# clock.net
KiCad netlist of a schematic drawn in EAGLE
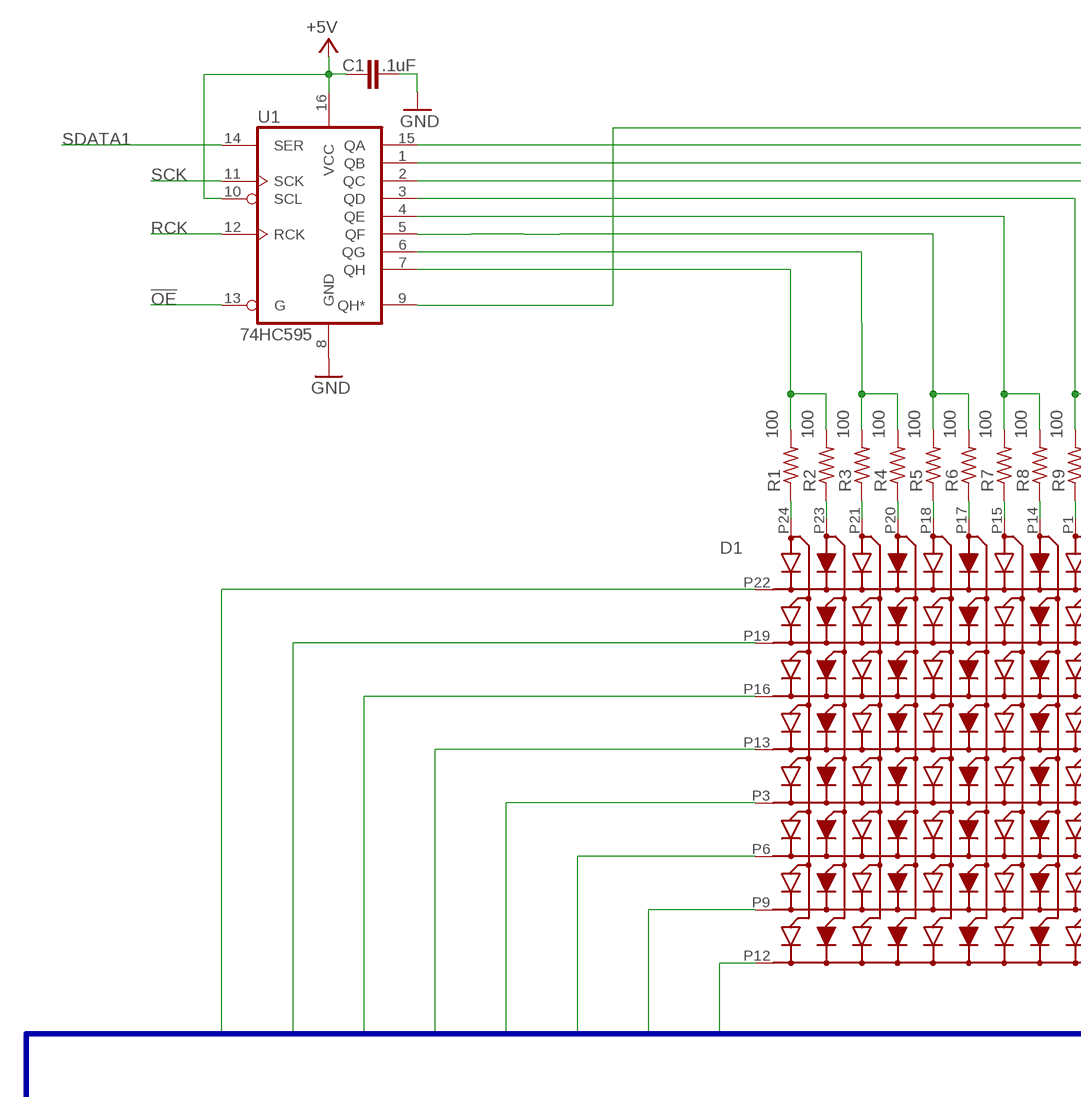
[diagram p0: schematic, sheet 1, part 1 of 3]
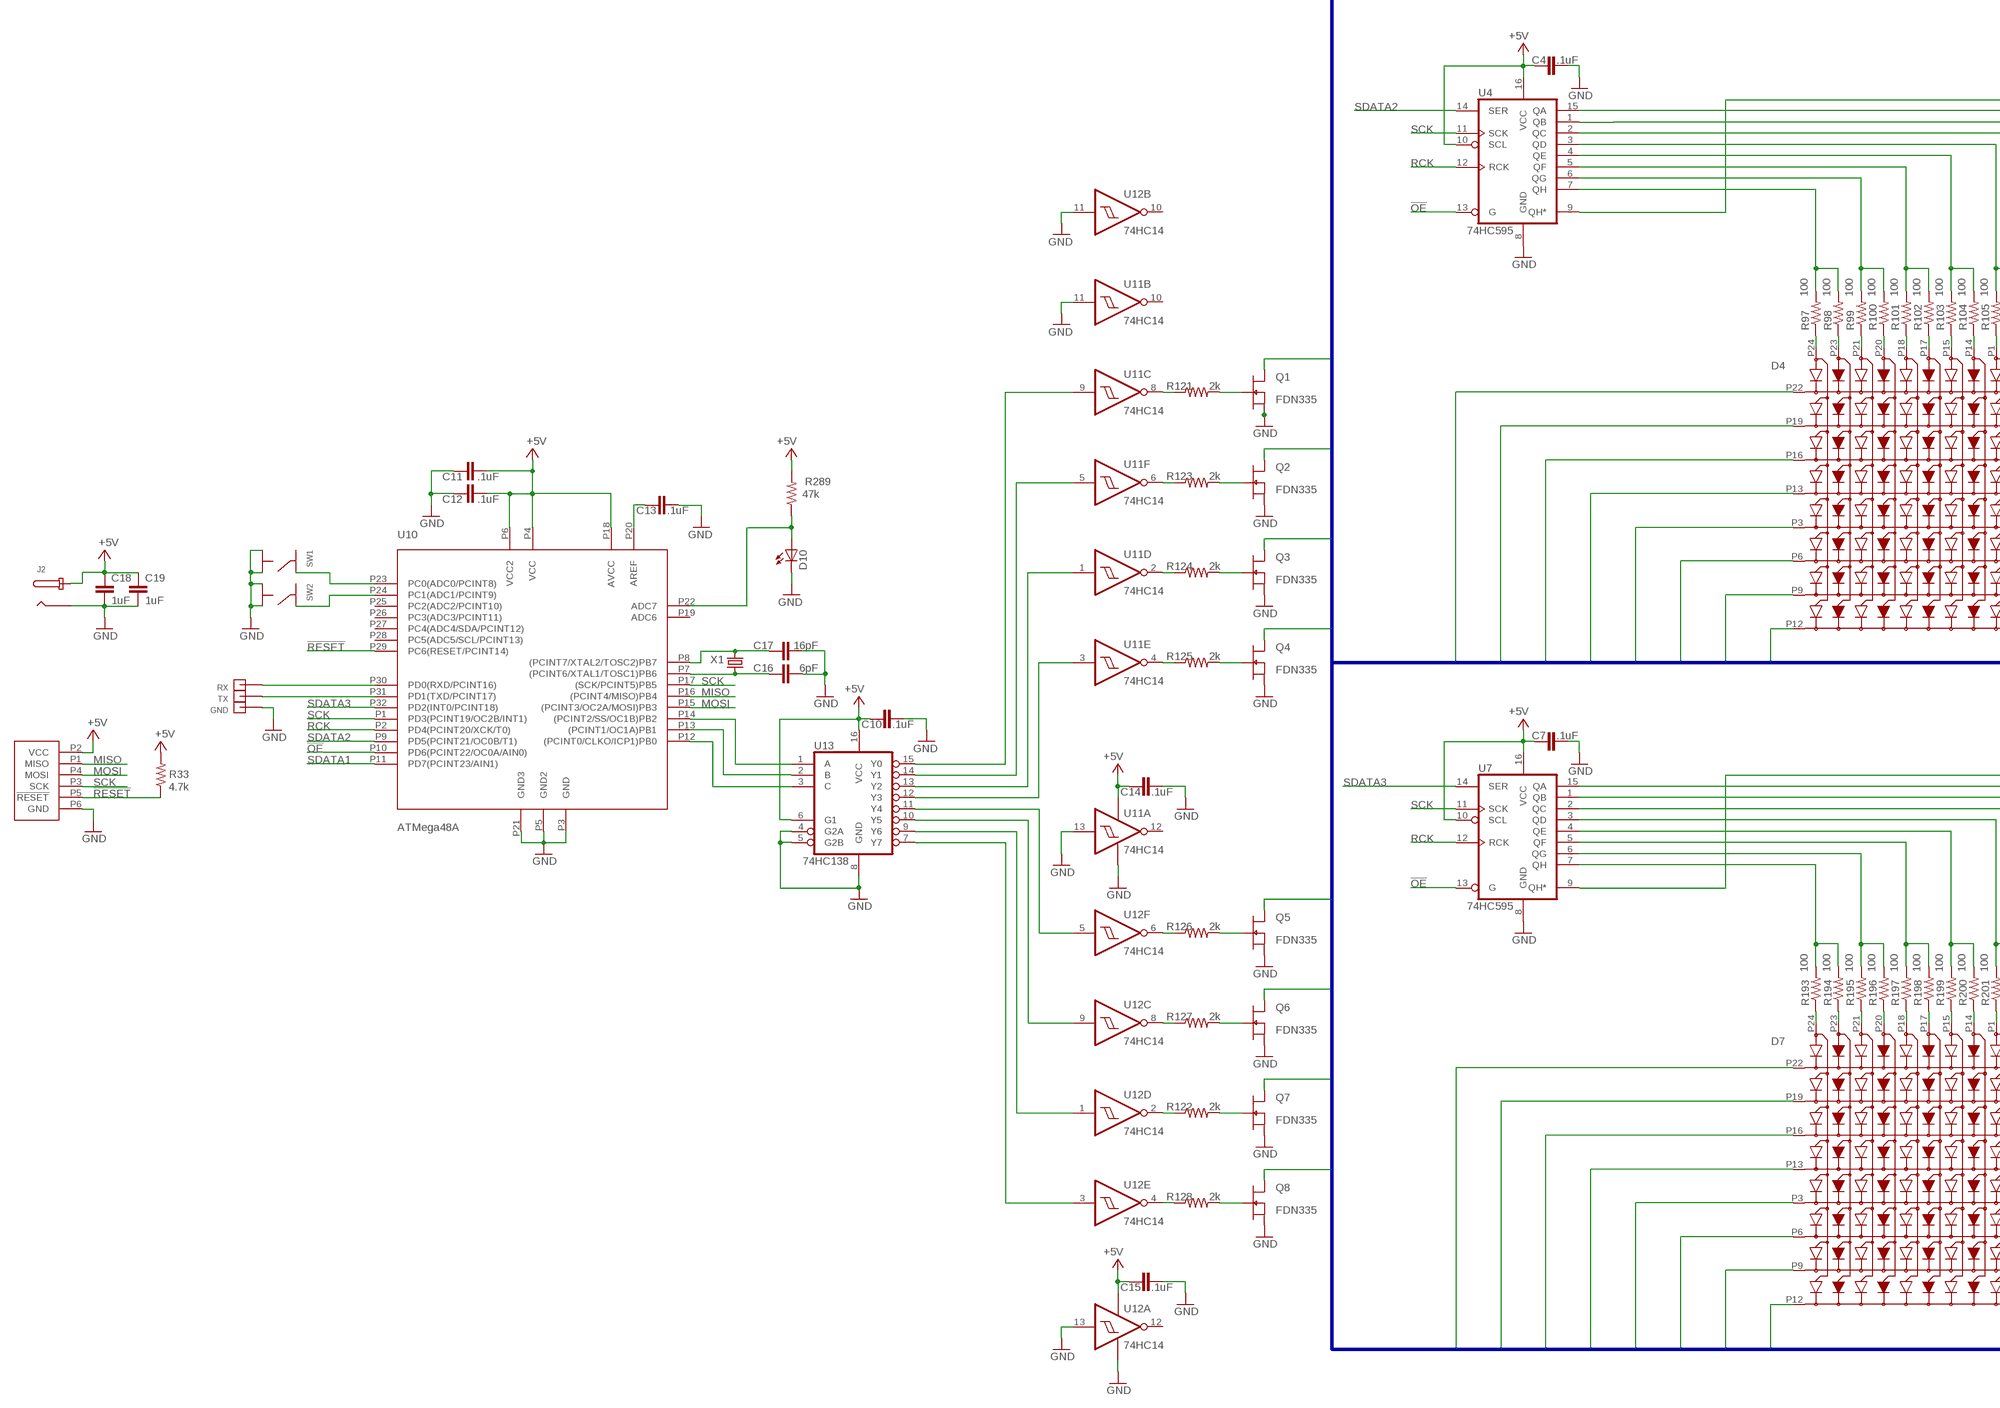
[diagram p1: schematic, sheet 1, part 2 of 3]
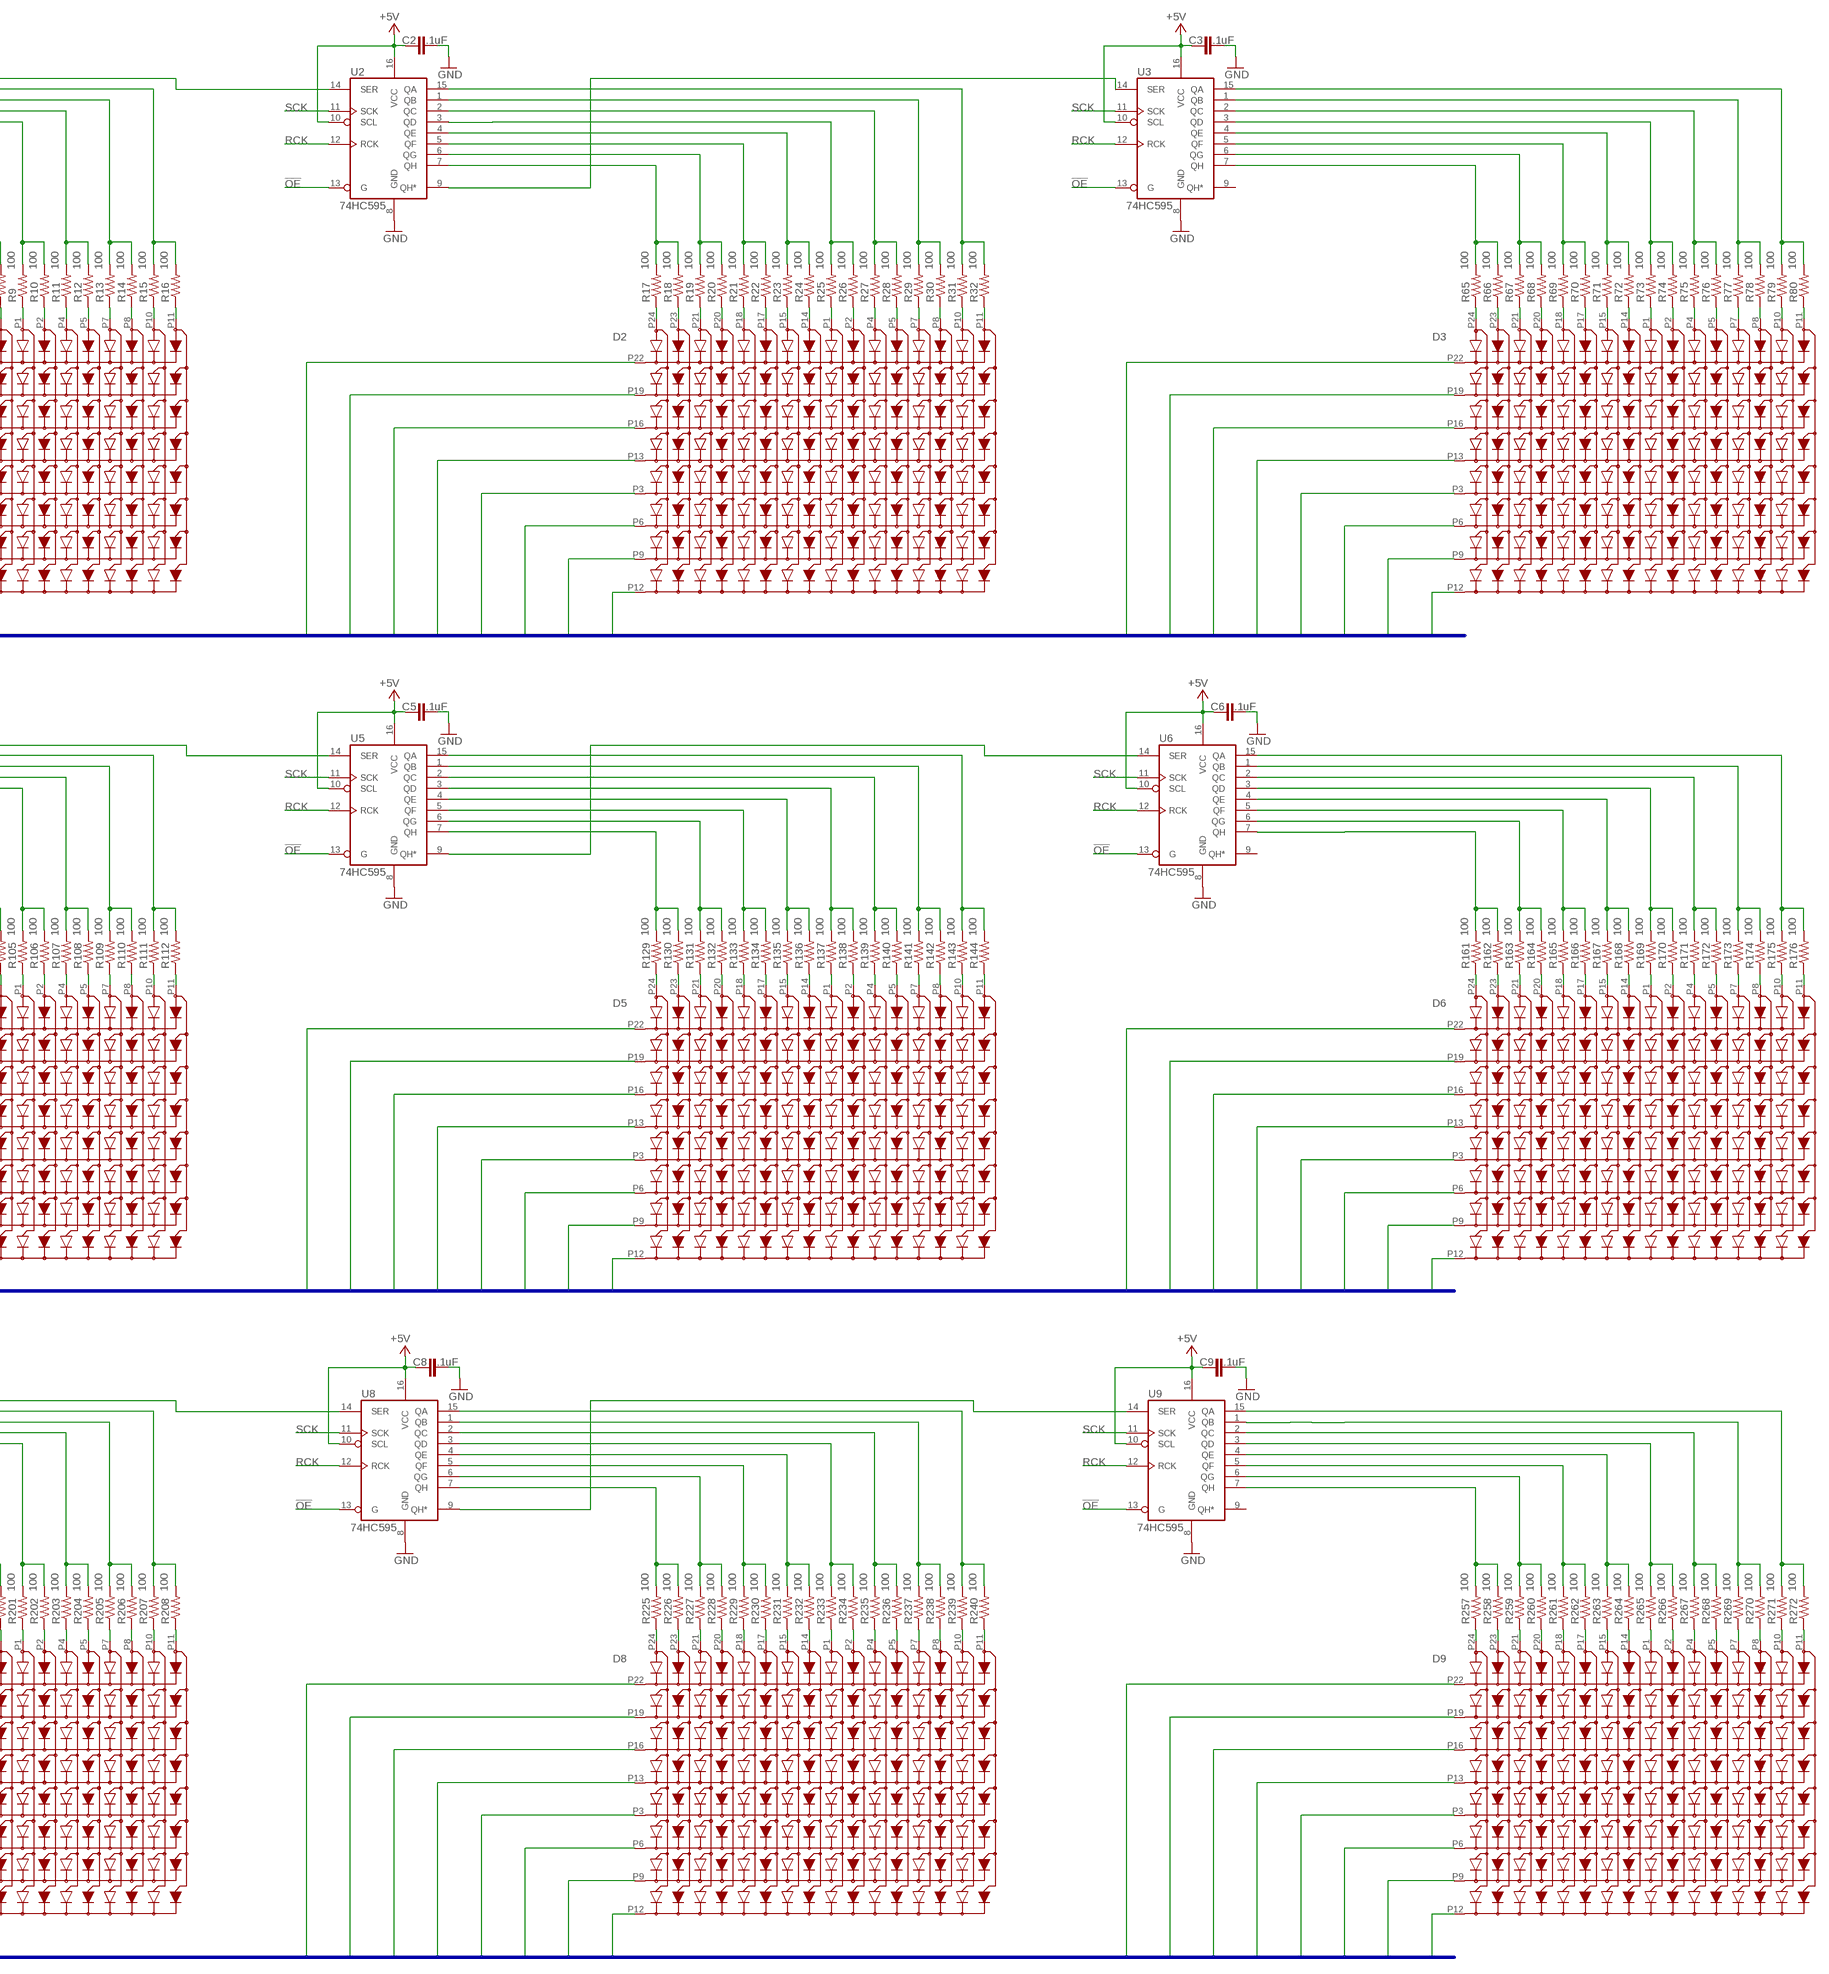
[diagram p2: schematic, sheet 1, part 3 of 3]

(export (version "E")
  (design (tool "Eeschema 10.0.6"))
  (components
    (comp (ref "C1")
      (value ".1uF")
      (footprint "eagle-import:0603_1608METRIC")
      (fields
        (field (name "DISTRIBUTORPARTNO") "478-1239-1-ND")
        (field (name "MANUFACTURER") "AVX Corporation")
        (field (name "TOLERANCE") "10%")
        (field (name "MNT-TYPE") "SM")
      )
      (libsource (lib "eagle-import") (part "CAPACITOR-.1UF"))
    )
    (comp (ref "C2")
      (value ".1uF")
      (footprint "eagle-import:0603_1608METRIC")
      (fields
        (field (name "DISTRIBUTORPARTNO") "478-1239-1-ND")
        (field (name "MANUFACTURER") "AVX Corporation")
        (field (name "TOLERANCE") "10%")
        (field (name "MNT-TYPE") "SM")
      )
      (libsource (lib "eagle-import") (part "CAPACITOR-.1UF"))
    )
    (comp (ref "C3")
      (value ".1uF")
      (footprint "eagle-import:0603_1608METRIC")
      (fields
        (field (name "DISTRIBUTORPARTNO") "478-1239-1-ND")
        (field (name "MANUFACTURER") "AVX Corporation")
        (field (name "TOLERANCE") "10%")
        (field (name "MNT-TYPE") "SM")
      )
      (libsource (lib "eagle-import") (part "CAPACITOR-.1UF"))
    )
    (comp (ref "C4")
      (value ".1uF")
      (footprint "eagle-import:0603_1608METRIC")
      (fields
        (field (name "DISTRIBUTORPARTNO") "478-1239-1-ND")
        (field (name "MANUFACTURER") "AVX Corporation")
        (field (name "TOLERANCE") "10%")
        (field (name "MNT-TYPE") "SM")
      )
      (libsource (lib "eagle-import") (part "CAPACITOR-.1UF"))
    )
    (comp (ref "C5")
      (value ".1uF")
      (footprint "eagle-import:0603_1608METRIC")
      (fields
        (field (name "DISTRIBUTORPARTNO") "478-1239-1-ND")
        (field (name "MANUFACTURER") "AVX Corporation")
        (field (name "TOLERANCE") "10%")
        (field (name "MNT-TYPE") "SM")
      )
      (libsource (lib "eagle-import") (part "CAPACITOR-.1UF"))
    )
    (comp (ref "C6")
      (value ".1uF")
      (footprint "eagle-import:0603_1608METRIC")
      (fields
        (field (name "DISTRIBUTORPARTNO") "478-1239-1-ND")
        (field (name "MANUFACTURER") "AVX Corporation")
        (field (name "TOLERANCE") "10%")
        (field (name "MNT-TYPE") "SM")
      )
      (libsource (lib "eagle-import") (part "CAPACITOR-.1UF"))
    )
    (comp (ref "C7")
      (value ".1uF")
      (footprint "eagle-import:0603_1608METRIC")
      (fields
        (field (name "DISTRIBUTORPARTNO") "478-1239-1-ND")
        (field (name "MANUFACTURER") "AVX Corporation")
        (field (name "TOLERANCE") "10%")
        (field (name "MNT-TYPE") "SM")
      )
      (libsource (lib "eagle-import") (part "CAPACITOR-.1UF"))
    )
    (comp (ref "C8")
      (value ".1uF")
      (footprint "eagle-import:0603_1608METRIC")
      (fields
        (field (name "DISTRIBUTORPARTNO") "478-1239-1-ND")
        (field (name "MANUFACTURER") "AVX Corporation")
        (field (name "TOLERANCE") "10%")
        (field (name "MNT-TYPE") "SM")
      )
      (libsource (lib "eagle-import") (part "CAPACITOR-.1UF"))
    )
    (comp (ref "C9")
      (value ".1uF")
      (footprint "eagle-import:0603_1608METRIC")
      (fields
        (field (name "DISTRIBUTORPARTNO") "478-1239-1-ND")
        (field (name "MANUFACTURER") "AVX Corporation")
        (field (name "TOLERANCE") "10%")
        (field (name "MNT-TYPE") "SM")
      )
      (libsource (lib "eagle-import") (part "CAPACITOR-.1UF"))
    )
    (comp (ref "C10")
      (value ".1uF")
      (footprint "eagle-import:0603_1608METRIC")
      (fields
        (field (name "DISTRIBUTORPARTNO") "478-1239-1-ND")
        (field (name "MANUFACTURER") "AVX Corporation")
        (field (name "TOLERANCE") "10%")
        (field (name "MNT-TYPE") "SM")
      )
      (libsource (lib "eagle-import") (part "CAPACITOR-.1UF"))
    )
    (comp (ref "C11")
      (value ".1uF")
      (footprint "eagle-import:0603_1608METRIC")
      (fields
        (field (name "DISTRIBUTORPARTNO") "478-1239-1-ND")
        (field (name "MANUFACTURER") "AVX Corporation")
        (field (name "TOLERANCE") "10%")
        (field (name "MNT-TYPE") "SM")
      )
      (libsource (lib "eagle-import") (part "CAPACITOR-.1UF"))
    )
    (comp (ref "C12")
      (value ".1uF")
      (footprint "eagle-import:0603_1608METRIC")
      (fields
        (field (name "DISTRIBUTORPARTNO") "478-1239-1-ND")
        (field (name "MANUFACTURER") "AVX Corporation")
        (field (name "TOLERANCE") "10%")
        (field (name "MNT-TYPE") "SM")
      )
      (libsource (lib "eagle-import") (part "CAPACITOR-.1UF"))
    )
    (comp (ref "C13")
      (value ".1uF")
      (footprint "eagle-import:0603_1608METRIC")
      (fields
        (field (name "DISTRIBUTORPARTNO") "478-1239-1-ND")
        (field (name "MANUFACTURER") "AVX Corporation")
        (field (name "TOLERANCE") "10%")
        (field (name "MNT-TYPE") "SM")
      )
      (libsource (lib "eagle-import") (part "CAPACITOR-.1UF"))
    )
    (comp (ref "C14")
      (value ".1uF")
      (footprint "eagle-import:0603_1608METRIC")
      (fields
        (field (name "DISTRIBUTORPARTNO") "478-1239-1-ND")
        (field (name "MANUFACTURER") "AVX Corporation")
        (field (name "TOLERANCE") "10%")
        (field (name "MNT-TYPE") "SM")
      )
      (libsource (lib "eagle-import") (part "CAPACITOR-.1UF"))
    )
    (comp (ref "C15")
      (value ".1uF")
      (footprint "eagle-import:0603_1608METRIC")
      (fields
        (field (name "DISTRIBUTORPARTNO") "478-1239-1-ND")
        (field (name "MANUFACTURER") "AVX Corporation")
        (field (name "TOLERANCE") "10%")
        (field (name "MNT-TYPE") "SM")
      )
      (libsource (lib "eagle-import") (part "CAPACITOR-.1UF"))
    )
    (comp (ref "C16")
      (value "6pF")
      (footprint "eagle-import:0603_1608METRIC")
      (fields
        (field (name "DISTRIBUTORPARTNO") "445-5036-1-ND")
        (field (name "MANUFACTURER") "TDK Corporation")
        (field (name "TOLERANCE") "5%")
      )
      (libsource (lib "eagle-import") (part "CAPACITOR-6PF"))
    )
    (comp (ref "C17")
      (value "16pF")
      (footprint "eagle-import:0603_1608METRIC")
      (fields
        (field (name "DISTRIBUTORPARTNO") "445-5051-1-ND")
        (field (name "MANUFACTURER") "TDK Corporation")
        (field (name "TOLERANCE") "5%")
      )
      (libsource (lib "eagle-import") (part "CAPACITOR-16PF"))
    )
    (comp (ref "C18")
      (value "1uF")
      (footprint "eagle-import:0603_1608METRIC")
      (fields
        (field (name "DISTRIBUTORPARTNO") "445-1328-1-ND")
        (field (name "MANUFACTURER") "TDK CORPORATION")
        (field (name "TOLERANCE") "20%")
      )
      (libsource (lib "eagle-import") (part "CAPACITOR-1UF"))
    )
    (comp (ref "C19")
      (value "1uF")
      (footprint "eagle-import:0603_1608METRIC")
      (fields
        (field (name "DISTRIBUTORPARTNO") "445-1328-1-ND")
        (field (name "MANUFACTURER") "TDK CORPORATION")
        (field (name "TOLERANCE") "20%")
      )
      (libsource (lib "eagle-import") (part "CAPACITOR-1UF"))
    )
    (comp (ref "D1")
      (value "BL-M12A883DUG-11\"")
      (footprint "eagle-import:BL-M12A883DUG-11")
      (fields
        (field (name "DISTRIBUTORPARTNO") "458")
        (field (name "MANPARTNO") "BL-M12A883DUG-11")
        (field (name "MANUFACTURER") "BETLUX")
      )
      (libsource (lib "eagle-import") (part "BL-M12A883DUG-11{dblquote}"))
    )
    (comp (ref "D2")
      (value "BL-M12A883DUG-11\"")
      (footprint "eagle-import:BL-M12A883DUG-11")
      (fields
        (field (name "DISTRIBUTORPARTNO") "458")
        (field (name "MANPARTNO") "BL-M12A883DUG-11")
        (field (name "MANUFACTURER") "BETLUX")
      )
      (libsource (lib "eagle-import") (part "BL-M12A883DUG-11{dblquote}"))
    )
    (comp (ref "D3")
      (value "BL-M12A883DUG-11\"")
      (footprint "eagle-import:BL-M12A883DUG-11")
      (fields
        (field (name "DISTRIBUTORPARTNO") "458")
        (field (name "MANPARTNO") "BL-M12A883DUG-11")
        (field (name "MANUFACTURER") "BETLUX")
      )
      (libsource (lib "eagle-import") (part "BL-M12A883DUG-11{dblquote}"))
    )
    (comp (ref "D4")
      (value "BL-M12A883DUG-11\"")
      (footprint "eagle-import:BL-M12A883DUG-11")
      (fields
        (field (name "DISTRIBUTORPARTNO") "458")
        (field (name "MANPARTNO") "BL-M12A883DUG-11")
        (field (name "MANUFACTURER") "BETLUX")
      )
      (libsource (lib "eagle-import") (part "BL-M12A883DUG-11{dblquote}"))
    )
    (comp (ref "D5")
      (value "BL-M12A883DUG-11\"")
      (footprint "eagle-import:BL-M12A883DUG-11")
      (fields
        (field (name "DISTRIBUTORPARTNO") "458")
        (field (name "MANPARTNO") "BL-M12A883DUG-11")
        (field (name "MANUFACTURER") "BETLUX")
      )
      (libsource (lib "eagle-import") (part "BL-M12A883DUG-11{dblquote}"))
    )
    (comp (ref "D6")
      (value "BL-M12A883DUG-11\"")
      (footprint "eagle-import:BL-M12A883DUG-11")
      (fields
        (field (name "DISTRIBUTORPARTNO") "458")
        (field (name "MANPARTNO") "BL-M12A883DUG-11")
        (field (name "MANUFACTURER") "BETLUX")
      )
      (libsource (lib "eagle-import") (part "BL-M12A883DUG-11{dblquote}"))
    )
    (comp (ref "D7")
      (value "BL-M12A883DUG-11\"")
      (footprint "eagle-import:BL-M12A883DUG-11")
      (fields
        (field (name "DISTRIBUTORPARTNO") "458")
        (field (name "MANPARTNO") "BL-M12A883DUG-11")
        (field (name "MANUFACTURER") "BETLUX")
      )
      (libsource (lib "eagle-import") (part "BL-M12A883DUG-11{dblquote}"))
    )
    (comp (ref "D8")
      (value "BL-M12A883DUG-11\"")
      (footprint "eagle-import:BL-M12A883DUG-11")
      (fields
        (field (name "DISTRIBUTORPARTNO") "458")
        (field (name "MANPARTNO") "BL-M12A883DUG-11")
        (field (name "MANUFACTURER") "BETLUX")
      )
      (libsource (lib "eagle-import") (part "BL-M12A883DUG-11{dblquote}"))
    )
    (comp (ref "D9")
      (value "BL-M12A883DUG-11\"")
      (footprint "eagle-import:BL-M12A883DUG-11")
      (fields
        (field (name "DISTRIBUTORPARTNO") "458")
        (field (name "MANPARTNO") "BL-M12A883DUG-11")
        (field (name "MANUFACTURER") "BETLUX")
      )
      (libsource (lib "eagle-import") (part "BL-M12A883DUG-11{dblquote}"))
    )
    (comp (ref "D10")
      (value "TEPT4400")
      (footprint "eagle-import:LED3MM")
      (fields
        (field (name "DISTRIBUTORPARTNO") "751-1057-ND")
        (field (name "MANUFACTURER") "Vishay Semiconductors")
      )
      (libsource (lib "eagle-import") (part "TEPT4400"))
    )
    (comp (ref "GND")
      (value "HEADERPIN")
      (footprint "eagle-import:HEADERPIN")
      (libsource (lib "eagle-import") (part "HEADERPIN"))
    )
    (comp (ref "J1")
      (value "PROGHEADER-PINS")
      (footprint "eagle-import:ATMEL-PROGRAMMING-HEADER")
      (fields
        (field (name "DISTRIBUTORPARTNO") "xxSAM1048-50-NDxx")
        (field (name "MANPARTNO") "TSW-150-08-T-D")
        (field (name "MANUFACTURER") "Samtec Inc.")
      )
      (libsource (lib "eagle-import") (part "PROGHEADER-PINS"))
    )
    (comp (ref "J2")
      (value "DC-BARREL-JACK")
      (footprint "eagle-import:PJ-037A")
      (fields
        (field (name "DISTRIBUTORPARTNO") "CP-037A-ND")
        (field (name "MANPARTNO") "PJ-037A")
        (field (name "MANUFACTURER") "CUI Inc")
      )
      (libsource (lib "eagle-import") (part "DC-BARREL-JACK"))
    )
    (comp (ref "Q1")
      (value "FDN335")
      (footprint "eagle-import:SOT23")
      (fields
        (field (name "DISTRIBUTORPARTNO") "FDN335NCT-ND")
        (field (name "MANPARTNO") "FDN335N")
        (field (name "MANUFACTURER") "Fairchild Semiconductor")
      )
      (libsource (lib "eagle-import") (part "FDN335"))
    )
    (comp (ref "Q2")
      (value "FDN335")
      (footprint "eagle-import:SOT23")
      (fields
        (field (name "DISTRIBUTORPARTNO") "FDN335NCT-ND")
        (field (name "MANPARTNO") "FDN335N")
        (field (name "MANUFACTURER") "Fairchild Semiconductor")
      )
      (libsource (lib "eagle-import") (part "FDN335"))
    )
    (comp (ref "Q3")
      (value "FDN335")
      (footprint "eagle-import:SOT23")
      (fields
        (field (name "DISTRIBUTORPARTNO") "FDN335NCT-ND")
        (field (name "MANPARTNO") "FDN335N")
        (field (name "MANUFACTURER") "Fairchild Semiconductor")
      )
      (libsource (lib "eagle-import") (part "FDN335"))
    )
    (comp (ref "Q4")
      (value "FDN335")
      (footprint "eagle-import:SOT23")
      (fields
        (field (name "DISTRIBUTORPARTNO") "FDN335NCT-ND")
        (field (name "MANPARTNO") "FDN335N")
        (field (name "MANUFACTURER") "Fairchild Semiconductor")
      )
      (libsource (lib "eagle-import") (part "FDN335"))
    )
    (comp (ref "Q5")
      (value "FDN335")
      (footprint "eagle-import:SOT23")
      (fields
        (field (name "DISTRIBUTORPARTNO") "FDN335NCT-ND")
        (field (name "MANPARTNO") "FDN335N")
        (field (name "MANUFACTURER") "Fairchild Semiconductor")
      )
      (libsource (lib "eagle-import") (part "FDN335"))
    )
    (comp (ref "Q6")
      (value "FDN335")
      (footprint "eagle-import:SOT23")
      (fields
        (field (name "DISTRIBUTORPARTNO") "FDN335NCT-ND")
        (field (name "MANPARTNO") "FDN335N")
        (field (name "MANUFACTURER") "Fairchild Semiconductor")
      )
      (libsource (lib "eagle-import") (part "FDN335"))
    )
    (comp (ref "Q7")
      (value "FDN335")
      (footprint "eagle-import:SOT23")
      (fields
        (field (name "DISTRIBUTORPARTNO") "FDN335NCT-ND")
        (field (name "MANPARTNO") "FDN335N")
        (field (name "MANUFACTURER") "Fairchild Semiconductor")
      )
      (libsource (lib "eagle-import") (part "FDN335"))
    )
    (comp (ref "Q8")
      (value "FDN335")
      (footprint "eagle-import:SOT23")
      (fields
        (field (name "DISTRIBUTORPARTNO") "FDN335NCT-ND")
        (field (name "MANPARTNO") "FDN335N")
        (field (name "MANUFACTURER") "Fairchild Semiconductor")
      )
      (libsource (lib "eagle-import") (part "FDN335"))
    )
    (comp (ref "R1")
      (value "100")
      (footprint "eagle-import:0603_1608METRIC")
      (fields
        (field (name "DISTRIBUTORPARTNO") "311-100GRCT-ND")
        (field (name "MANPARTNO") "RC0603JR-07100RL")
        (field (name "MANUFACTURER") "Yaego")
        (field (name "PACKAGE") "0603 (1608 Metric)")
      )
      (libsource (lib "eagle-import") (part "RESISTOR--5%-0603100"))
    )
    (comp (ref "R2")
      (value "100")
      (footprint "eagle-import:0603_1608METRIC")
      (fields
        (field (name "DISTRIBUTORPARTNO") "311-100GRCT-ND")
        (field (name "MANPARTNO") "RC0603JR-07100RL")
        (field (name "MANUFACTURER") "Yaego")
        (field (name "PACKAGE") "0603 (1608 Metric)")
      )
      (libsource (lib "eagle-import") (part "RESISTOR--5%-0603100"))
    )
    (comp (ref "R3")
      (value "100")
      (footprint "eagle-import:0603_1608METRIC")
      (fields
        (field (name "DISTRIBUTORPARTNO") "311-100GRCT-ND")
        (field (name "MANPARTNO") "RC0603JR-07100RL")
        (field (name "MANUFACTURER") "Yaego")
        (field (name "PACKAGE") "0603 (1608 Metric)")
      )
      (libsource (lib "eagle-import") (part "RESISTOR--5%-0603100"))
    )
    (comp (ref "R4")
      (value "100")
      (footprint "eagle-import:0603_1608METRIC")
      (fields
        (field (name "DISTRIBUTORPARTNO") "311-100GRCT-ND")
        (field (name "MANPARTNO") "RC0603JR-07100RL")
        (field (name "MANUFACTURER") "Yaego")
        (field (name "PACKAGE") "0603 (1608 Metric)")
      )
      (libsource (lib "eagle-import") (part "RESISTOR--5%-0603100"))
    )
    (comp (ref "R5")
      (value "100")
      (footprint "eagle-import:0603_1608METRIC")
      (fields
        (field (name "DISTRIBUTORPARTNO") "311-100GRCT-ND")
        (field (name "MANPARTNO") "RC0603JR-07100RL")
        (field (name "MANUFACTURER") "Yaego")
        (field (name "PACKAGE") "0603 (1608 Metric)")
      )
      (libsource (lib "eagle-import") (part "RESISTOR--5%-0603100"))
    )
    (comp (ref "R6")
      (value "100")
      (footprint "eagle-import:0603_1608METRIC")
      (fields
        (field (name "DISTRIBUTORPARTNO") "311-100GRCT-ND")
        (field (name "MANPARTNO") "RC0603JR-07100RL")
        (field (name "MANUFACTURER") "Yaego")
        (field (name "PACKAGE") "0603 (1608 Metric)")
      )
      (libsource (lib "eagle-import") (part "RESISTOR--5%-0603100"))
    )
    (comp (ref "R7")
      (value "100")
      (footprint "eagle-import:0603_1608METRIC")
      (fields
        (field (name "DISTRIBUTORPARTNO") "311-100GRCT-ND")
        (field (name "MANPARTNO") "RC0603JR-07100RL")
        (field (name "MANUFACTURER") "Yaego")
        (field (name "PACKAGE") "0603 (1608 Metric)")
      )
      (libsource (lib "eagle-import") (part "RESISTOR--5%-0603100"))
    )
    (comp (ref "R8")
      (value "100")
      (footprint "eagle-import:0603_1608METRIC")
      (fields
        (field (name "DISTRIBUTORPARTNO") "311-100GRCT-ND")
        (field (name "MANPARTNO") "RC0603JR-07100RL")
        (field (name "MANUFACTURER") "Yaego")
        (field (name "PACKAGE") "0603 (1608 Metric)")
      )
      (libsource (lib "eagle-import") (part "RESISTOR--5%-0603100"))
    )
    (comp (ref "R9")
      (value "100")
      (footprint "eagle-import:0603_1608METRIC")
      (fields
        (field (name "DISTRIBUTORPARTNO") "311-100GRCT-ND")
        (field (name "MANPARTNO") "RC0603JR-07100RL")
        (field (name "MANUFACTURER") "Yaego")
        (field (name "PACKAGE") "0603 (1608 Metric)")
      )
      (libsource (lib "eagle-import") (part "RESISTOR--5%-0603100"))
    )
    (comp (ref "R10")
      (value "100")
      (footprint "eagle-import:0603_1608METRIC")
      (fields
        (field (name "DISTRIBUTORPARTNO") "311-100GRCT-ND")
        (field (name "MANPARTNO") "RC0603JR-07100RL")
        (field (name "MANUFACTURER") "Yaego")
        (field (name "PACKAGE") "0603 (1608 Metric)")
      )
      (libsource (lib "eagle-import") (part "RESISTOR--5%-0603100"))
    )
    (comp (ref "R11")
      (value "100")
      (footprint "eagle-import:0603_1608METRIC")
      (fields
        (field (name "DISTRIBUTORPARTNO") "311-100GRCT-ND")
        (field (name "MANPARTNO") "RC0603JR-07100RL")
        (field (name "MANUFACTURER") "Yaego")
        (field (name "PACKAGE") "0603 (1608 Metric)")
      )
      (libsource (lib "eagle-import") (part "RESISTOR--5%-0603100"))
    )
    (comp (ref "R12")
      (value "100")
      (footprint "eagle-import:0603_1608METRIC")
      (fields
        (field (name "DISTRIBUTORPARTNO") "311-100GRCT-ND")
        (field (name "MANPARTNO") "RC0603JR-07100RL")
        (field (name "MANUFACTURER") "Yaego")
        (field (name "PACKAGE") "0603 (1608 Metric)")
      )
      (libsource (lib "eagle-import") (part "RESISTOR--5%-0603100"))
    )
    (comp (ref "R13")
      (value "100")
      (footprint "eagle-import:0603_1608METRIC")
      (fields
        (field (name "DISTRIBUTORPARTNO") "311-100GRCT-ND")
        (field (name "MANPARTNO") "RC0603JR-07100RL")
        (field (name "MANUFACTURER") "Yaego")
        (field (name "PACKAGE") "0603 (1608 Metric)")
      )
      (libsource (lib "eagle-import") (part "RESISTOR--5%-0603100"))
    )
    (comp (ref "R14")
      (value "100")
      (footprint "eagle-import:0603_1608METRIC")
      (fields
        (field (name "DISTRIBUTORPARTNO") "311-100GRCT-ND")
        (field (name "MANPARTNO") "RC0603JR-07100RL")
        (field (name "MANUFACTURER") "Yaego")
        (field (name "PACKAGE") "0603 (1608 Metric)")
      )
      (libsource (lib "eagle-import") (part "RESISTOR--5%-0603100"))
    )
    (comp (ref "R15")
      (value "100")
      (footprint "eagle-import:0603_1608METRIC")
      (fields
        (field (name "DISTRIBUTORPARTNO") "311-100GRCT-ND")
        (field (name "MANPARTNO") "RC0603JR-07100RL")
        (field (name "MANUFACTURER") "Yaego")
        (field (name "PACKAGE") "0603 (1608 Metric)")
      )
      (libsource (lib "eagle-import") (part "RESISTOR--5%-0603100"))
    )
    (comp (ref "R16")
      (value "100")
      (footprint "eagle-import:0603_1608METRIC")
      (fields
        (field (name "DISTRIBUTORPARTNO") "311-100GRCT-ND")
        (field (name "MANPARTNO") "RC0603JR-07100RL")
        (field (name "MANUFACTURER") "Yaego")
        (field (name "PACKAGE") "0603 (1608 Metric)")
      )
      (libsource (lib "eagle-import") (part "RESISTOR--5%-0603100"))
    )
    (comp (ref "R17")
      (value "100")
      (footprint "eagle-import:0603_1608METRIC")
      (fields
        (field (name "DISTRIBUTORPARTNO") "311-100GRCT-ND")
        (field (name "MANPARTNO") "RC0603JR-07100RL")
        (field (name "MANUFACTURER") "Yaego")
        (field (name "PACKAGE") "0603 (1608 Metric)")
      )
      (libsource (lib "eagle-import") (part "RESISTOR--5%-0603100"))
    )
    (comp (ref "R18")
      (value "100")
      (footprint "eagle-import:0603_1608METRIC")
      (fields
        (field (name "DISTRIBUTORPARTNO") "311-100GRCT-ND")
        (field (name "MANPARTNO") "RC0603JR-07100RL")
        (field (name "MANUFACTURER") "Yaego")
        (field (name "PACKAGE") "0603 (1608 Metric)")
      )
      (libsource (lib "eagle-import") (part "RESISTOR--5%-0603100"))
    )
    (comp (ref "R19")
      (value "100")
      (footprint "eagle-import:0603_1608METRIC")
      (fields
        (field (name "DISTRIBUTORPARTNO") "311-100GRCT-ND")
        (field (name "MANPARTNO") "RC0603JR-07100RL")
        (field (name "MANUFACTURER") "Yaego")
        (field (name "PACKAGE") "0603 (1608 Metric)")
      )
      (libsource (lib "eagle-import") (part "RESISTOR--5%-0603100"))
    )
    (comp (ref "R20")
      (value "100")
      (footprint "eagle-import:0603_1608METRIC")
      (fields
        (field (name "DISTRIBUTORPARTNO") "311-100GRCT-ND")
        (field (name "MANPARTNO") "RC0603JR-07100RL")
        (field (name "MANUFACTURER") "Yaego")
        (field (name "PACKAGE") "0603 (1608 Metric)")
      )
      (libsource (lib "eagle-import") (part "RESISTOR--5%-0603100"))
    )
    (comp (ref "R21")
      (value "100")
      (footprint "eagle-import:0603_1608METRIC")
      (fields
        (field (name "DISTRIBUTORPARTNO") "311-100GRCT-ND")
        (field (name "MANPARTNO") "RC0603JR-07100RL")
        (field (name "MANUFACTURER") "Yaego")
        (field (name "PACKAGE") "0603 (1608 Metric)")
      )
      (libsource (lib "eagle-import") (part "RESISTOR--5%-0603100"))
    )
    (comp (ref "R22")
      (value "100")
      (footprint "eagle-import:0603_1608METRIC")
      (fields
        (field (name "DISTRIBUTORPARTNO") "311-100GRCT-ND")
        (field (name "MANPARTNO") "RC0603JR-07100RL")
        (field (name "MANUFACTURER") "Yaego")
        (field (name "PACKAGE") "0603 (1608 Metric)")
      )
      (libsource (lib "eagle-import") (part "RESISTOR--5%-0603100"))
    )
    (comp (ref "R23")
      (value "100")
      (footprint "eagle-import:0603_1608METRIC")
      (fields
        (field (name "DISTRIBUTORPARTNO") "311-100GRCT-ND")
        (field (name "MANPARTNO") "RC0603JR-07100RL")
        (field (name "MANUFACTURER") "Yaego")
        (field (name "PACKAGE") "0603 (1608 Metric)")
      )
      (libsource (lib "eagle-import") (part "RESISTOR--5%-0603100"))
    )
    (comp (ref "R24")
      (value "100")
      (footprint "eagle-import:0603_1608METRIC")
      (fields
        (field (name "DISTRIBUTORPARTNO") "311-100GRCT-ND")
        (field (name "MANPARTNO") "RC0603JR-07100RL")
        (field (name "MANUFACTURER") "Yaego")
        (field (name "PACKAGE") "0603 (1608 Metric)")
      )
      (libsource (lib "eagle-import") (part "RESISTOR--5%-0603100"))
    )
    (comp (ref "R25")
      (value "100")
      (footprint "eagle-import:0603_1608METRIC")
      (fields
        (field (name "DISTRIBUTORPARTNO") "311-100GRCT-ND")
        (field (name "MANPARTNO") "RC0603JR-07100RL")
        (field (name "MANUFACTURER") "Yaego")
        (field (name "PACKAGE") "0603 (1608 Metric)")
      )
      (libsource (lib "eagle-import") (part "RESISTOR--5%-0603100"))
    )
    (comp (ref "R26")
      (value "100")
      (footprint "eagle-import:0603_1608METRIC")
      (fields
        (field (name "DISTRIBUTORPARTNO") "311-100GRCT-ND")
        (field (name "MANPARTNO") "RC0603JR-07100RL")
        (field (name "MANUFACTURER") "Yaego")
        (field (name "PACKAGE") "0603 (1608 Metric)")
      )
      (libsource (lib "eagle-import") (part "RESISTOR--5%-0603100"))
    )
    (comp (ref "R27")
      (value "100")
      (footprint "eagle-import:0603_1608METRIC")
      (fields
        (field (name "DISTRIBUTORPARTNO") "311-100GRCT-ND")
        (field (name "MANPARTNO") "RC0603JR-07100RL")
        (field (name "MANUFACTURER") "Yaego")
        (field (name "PACKAGE") "0603 (1608 Metric)")
      )
      (libsource (lib "eagle-import") (part "RESISTOR--5%-0603100"))
    )
    (comp (ref "R28")
      (value "100")
      (footprint "eagle-import:0603_1608METRIC")
      (fields
        (field (name "DISTRIBUTORPARTNO") "311-100GRCT-ND")
        (field (name "MANPARTNO") "RC0603JR-07100RL")
        (field (name "MANUFACTURER") "Yaego")
        (field (name "PACKAGE") "0603 (1608 Metric)")
      )
      (libsource (lib "eagle-import") (part "RESISTOR--5%-0603100"))
    )
    (comp (ref "R29")
      (value "100")
      (footprint "eagle-import:0603_1608METRIC")
      (fields
        (field (name "DISTRIBUTORPARTNO") "311-100GRCT-ND")
        (field (name "MANPARTNO") "RC0603JR-07100RL")
        (field (name "MANUFACTURER") "Yaego")
        (field (name "PACKAGE") "0603 (1608 Metric)")
      )
      (libsource (lib "eagle-import") (part "RESISTOR--5%-0603100"))
    )
    (comp (ref "R30")
      (value "100")
      (footprint "eagle-import:0603_1608METRIC")
      (fields
        (field (name "DISTRIBUTORPARTNO") "311-100GRCT-ND")
        (field (name "MANPARTNO") "RC0603JR-07100RL")
        (field (name "MANUFACTURER") "Yaego")
        (field (name "PACKAGE") "0603 (1608 Metric)")
      )
      (libsource (lib "eagle-import") (part "RESISTOR--5%-0603100"))
    )
    (comp (ref "R31")
      (value "100")
      (footprint "eagle-import:0603_1608METRIC")
      (fields
        (field (name "DISTRIBUTORPARTNO") "311-100GRCT-ND")
        (field (name "MANPARTNO") "RC0603JR-07100RL")
        (field (name "MANUFACTURER") "Yaego")
        (field (name "PACKAGE") "0603 (1608 Metric)")
      )
      (libsource (lib "eagle-import") (part "RESISTOR--5%-0603100"))
    )
    (comp (ref "R32")
      (value "100")
      (footprint "eagle-import:0603_1608METRIC")
      (fields
        (field (name "DISTRIBUTORPARTNO") "311-100GRCT-ND")
        (field (name "MANPARTNO") "RC0603JR-07100RL")
        (field (name "MANUFACTURER") "Yaego")
        (field (name "PACKAGE") "0603 (1608 Metric)")
      )
      (libsource (lib "eagle-import") (part "RESISTOR--5%-0603100"))
    )
    (comp (ref "R33")
      (value "4.7k")
      (footprint "eagle-import:0603_1608METRIC")
      (fields
        (field (name "DISTRIBUTORPARTNO") "311-4.7kGRCT-ND")
        (field (name "MANPARTNO") "RC0603JR-074K7L")
        (field (name "MANUFACTURER") "Yaego")
      )
      (libsource (lib "eagle-import") (part "RESISTOR--5%-06034.7K"))
    )
    (comp (ref "R65")
      (value "100")
      (footprint "eagle-import:0603_1608METRIC")
      (fields
        (field (name "DISTRIBUTORPARTNO") "311-100GRCT-ND")
        (field (name "MANPARTNO") "RC0603JR-07100RL")
        (field (name "MANUFACTURER") "Yaego")
        (field (name "PACKAGE") "0603 (1608 Metric)")
      )
      (libsource (lib "eagle-import") (part "RESISTOR--5%-0603100"))
    )
    (comp (ref "R66")
      (value "100")
      (footprint "eagle-import:0603_1608METRIC")
      (fields
        (field (name "DISTRIBUTORPARTNO") "311-100GRCT-ND")
        (field (name "MANPARTNO") "RC0603JR-07100RL")
        (field (name "MANUFACTURER") "Yaego")
        (field (name "PACKAGE") "0603 (1608 Metric)")
      )
      (libsource (lib "eagle-import") (part "RESISTOR--5%-0603100"))
    )
    (comp (ref "R67")
      (value "100")
      (footprint "eagle-import:0603_1608METRIC")
      (fields
        (field (name "DISTRIBUTORPARTNO") "311-100GRCT-ND")
        (field (name "MANPARTNO") "RC0603JR-07100RL")
        (field (name "MANUFACTURER") "Yaego")
        (field (name "PACKAGE") "0603 (1608 Metric)")
      )
      (libsource (lib "eagle-import") (part "RESISTOR--5%-0603100"))
    )
    (comp (ref "R68")
      (value "100")
      (footprint "eagle-import:0603_1608METRIC")
      (fields
        (field (name "DISTRIBUTORPARTNO") "311-100GRCT-ND")
        (field (name "MANPARTNO") "RC0603JR-07100RL")
        (field (name "MANUFACTURER") "Yaego")
        (field (name "PACKAGE") "0603 (1608 Metric)")
      )
      (libsource (lib "eagle-import") (part "RESISTOR--5%-0603100"))
    )
    (comp (ref "R69")
      (value "100")
      (footprint "eagle-import:0603_1608METRIC")
      (fields
        (field (name "DISTRIBUTORPARTNO") "311-100GRCT-ND")
        (field (name "MANPARTNO") "RC0603JR-07100RL")
        (field (name "MANUFACTURER") "Yaego")
        (field (name "PACKAGE") "0603 (1608 Metric)")
      )
      (libsource (lib "eagle-import") (part "RESISTOR--5%-0603100"))
    )
    (comp (ref "R70")
      (value "100")
      (footprint "eagle-import:0603_1608METRIC")
      (fields
        (field (name "DISTRIBUTORPARTNO") "311-100GRCT-ND")
        (field (name "MANPARTNO") "RC0603JR-07100RL")
        (field (name "MANUFACTURER") "Yaego")
        (field (name "PACKAGE") "0603 (1608 Metric)")
      )
      (libsource (lib "eagle-import") (part "RESISTOR--5%-0603100"))
    )
    (comp (ref "R71")
      (value "100")
      (footprint "eagle-import:0603_1608METRIC")
      (fields
        (field (name "DISTRIBUTORPARTNO") "311-100GRCT-ND")
        (field (name "MANPARTNO") "RC0603JR-07100RL")
        (field (name "MANUFACTURER") "Yaego")
        (field (name "PACKAGE") "0603 (1608 Metric)")
      )
      (libsource (lib "eagle-import") (part "RESISTOR--5%-0603100"))
    )
    (comp (ref "R72")
      (value "100")
      (footprint "eagle-import:0603_1608METRIC")
      (fields
        (field (name "DISTRIBUTORPARTNO") "311-100GRCT-ND")
        (field (name "MANPARTNO") "RC0603JR-07100RL")
        (field (name "MANUFACTURER") "Yaego")
        (field (name "PACKAGE") "0603 (1608 Metric)")
      )
      (libsource (lib "eagle-import") (part "RESISTOR--5%-0603100"))
    )
    (comp (ref "R73")
      (value "100")
      (footprint "eagle-import:0603_1608METRIC")
      (fields
        (field (name "DISTRIBUTORPARTNO") "311-100GRCT-ND")
        (field (name "MANPARTNO") "RC0603JR-07100RL")
        (field (name "MANUFACTURER") "Yaego")
        (field (name "PACKAGE") "0603 (1608 Metric)")
      )
      (libsource (lib "eagle-import") (part "RESISTOR--5%-0603100"))
    )
    (comp (ref "R74")
      (value "100")
      (footprint "eagle-import:0603_1608METRIC")
      (fields
        (field (name "DISTRIBUTORPARTNO") "311-100GRCT-ND")
        (field (name "MANPARTNO") "RC0603JR-07100RL")
        (field (name "MANUFACTURER") "Yaego")
        (field (name "PACKAGE") "0603 (1608 Metric)")
      )
      (libsource (lib "eagle-import") (part "RESISTOR--5%-0603100"))
    )
    (comp (ref "R75")
      (value "100")
      (footprint "eagle-import:0603_1608METRIC")
      (fields
        (field (name "DISTRIBUTORPARTNO") "311-100GRCT-ND")
        (field (name "MANPARTNO") "RC0603JR-07100RL")
        (field (name "MANUFACTURER") "Yaego")
        (field (name "PACKAGE") "0603 (1608 Metric)")
      )
      (libsource (lib "eagle-import") (part "RESISTOR--5%-0603100"))
    )
    (comp (ref "R76")
      (value "100")
      (footprint "eagle-import:0603_1608METRIC")
      (fields
        (field (name "DISTRIBUTORPARTNO") "311-100GRCT-ND")
        (field (name "MANPARTNO") "RC0603JR-07100RL")
        (field (name "MANUFACTURER") "Yaego")
        (field (name "PACKAGE") "0603 (1608 Metric)")
      )
      (libsource (lib "eagle-import") (part "RESISTOR--5%-0603100"))
    )
    (comp (ref "R77")
      (value "100")
      (footprint "eagle-import:0603_1608METRIC")
      (fields
        (field (name "DISTRIBUTORPARTNO") "311-100GRCT-ND")
        (field (name "MANPARTNO") "RC0603JR-07100RL")
        (field (name "MANUFACTURER") "Yaego")
        (field (name "PACKAGE") "0603 (1608 Metric)")
      )
      (libsource (lib "eagle-import") (part "RESISTOR--5%-0603100"))
    )
    (comp (ref "R78")
      (value "100")
      (footprint "eagle-import:0603_1608METRIC")
      (fields
        (field (name "DISTRIBUTORPARTNO") "311-100GRCT-ND")
        (field (name "MANPARTNO") "RC0603JR-07100RL")
        (field (name "MANUFACTURER") "Yaego")
        (field (name "PACKAGE") "0603 (1608 Metric)")
      )
      (libsource (lib "eagle-import") (part "RESISTOR--5%-0603100"))
    )
    (comp (ref "R79")
      (value "100")
      (footprint "eagle-import:0603_1608METRIC")
      (fields
        (field (name "DISTRIBUTORPARTNO") "311-100GRCT-ND")
        (field (name "MANPARTNO") "RC0603JR-07100RL")
        (field (name "MANUFACTURER") "Yaego")
        (field (name "PACKAGE") "0603 (1608 Metric)")
      )
      (libsource (lib "eagle-import") (part "RESISTOR--5%-0603100"))
    )
    (comp (ref "R80")
      (value "100")
      (footprint "eagle-import:0603_1608METRIC")
      (fields
        (field (name "DISTRIBUTORPARTNO") "311-100GRCT-ND")
        (field (name "MANPARTNO") "RC0603JR-07100RL")
        (field (name "MANUFACTURER") "Yaego")
        (field (name "PACKAGE") "0603 (1608 Metric)")
      )
      (libsource (lib "eagle-import") (part "RESISTOR--5%-0603100"))
    )
    (comp (ref "R97")
      (value "100")
      (footprint "eagle-import:0603_1608METRIC")
      (fields
        (field (name "DISTRIBUTORPARTNO") "311-100GRCT-ND")
        (field (name "MANPARTNO") "RC0603JR-07100RL")
        (field (name "MANUFACTURER") "Yaego")
        (field (name "PACKAGE") "0603 (1608 Metric)")
      )
      (libsource (lib "eagle-import") (part "RESISTOR--5%-0603100"))
    )
    (comp (ref "R98")
      (value "100")
      (footprint "eagle-import:0603_1608METRIC")
      (fields
        (field (name "DISTRIBUTORPARTNO") "311-100GRCT-ND")
        (field (name "MANPARTNO") "RC0603JR-07100RL")
        (field (name "MANUFACTURER") "Yaego")
        (field (name "PACKAGE") "0603 (1608 Metric)")
      )
      (libsource (lib "eagle-import") (part "RESISTOR--5%-0603100"))
    )
    (comp (ref "R99")
      (value "100")
      (footprint "eagle-import:0603_1608METRIC")
      (fields
        (field (name "DISTRIBUTORPARTNO") "311-100GRCT-ND")
        (field (name "MANPARTNO") "RC0603JR-07100RL")
        (field (name "MANUFACTURER") "Yaego")
        (field (name "PACKAGE") "0603 (1608 Metric)")
      )
      (libsource (lib "eagle-import") (part "RESISTOR--5%-0603100"))
    )
    (comp (ref "R100")
      (value "100")
      (footprint "eagle-import:0603_1608METRIC")
      (fields
        (field (name "DISTRIBUTORPARTNO") "311-100GRCT-ND")
        (field (name "MANPARTNO") "RC0603JR-07100RL")
        (field (name "MANUFACTURER") "Yaego")
        (field (name "PACKAGE") "0603 (1608 Metric)")
      )
      (libsource (lib "eagle-import") (part "RESISTOR--5%-0603100"))
    )
    (comp (ref "R101")
      (value "100")
      (footprint "eagle-import:0603_1608METRIC")
      (fields
        (field (name "DISTRIBUTORPARTNO") "311-100GRCT-ND")
        (field (name "MANPARTNO") "RC0603JR-07100RL")
        (field (name "MANUFACTURER") "Yaego")
        (field (name "PACKAGE") "0603 (1608 Metric)")
      )
      (libsource (lib "eagle-import") (part "RESISTOR--5%-0603100"))
    )
    (comp (ref "R102")
      (value "100")
      (footprint "eagle-import:0603_1608METRIC")
      (fields
        (field (name "DISTRIBUTORPARTNO") "311-100GRCT-ND")
        (field (name "MANPARTNO") "RC0603JR-07100RL")
        (field (name "MANUFACTURER") "Yaego")
        (field (name "PACKAGE") "0603 (1608 Metric)")
      )
      (libsource (lib "eagle-import") (part "RESISTOR--5%-0603100"))
    )
    (comp (ref "R103")
      (value "100")
      (footprint "eagle-import:0603_1608METRIC")
      (fields
        (field (name "DISTRIBUTORPARTNO") "311-100GRCT-ND")
        (field (name "MANPARTNO") "RC0603JR-07100RL")
        (field (name "MANUFACTURER") "Yaego")
        (field (name "PACKAGE") "0603 (1608 Metric)")
      )
      (libsource (lib "eagle-import") (part "RESISTOR--5%-0603100"))
    )
    (comp (ref "R104")
      (value "100")
      (footprint "eagle-import:0603_1608METRIC")
      (fields
        (field (name "DISTRIBUTORPARTNO") "311-100GRCT-ND")
        (field (name "MANPARTNO") "RC0603JR-07100RL")
        (field (name "MANUFACTURER") "Yaego")
        (field (name "PACKAGE") "0603 (1608 Metric)")
      )
      (libsource (lib "eagle-import") (part "RESISTOR--5%-0603100"))
    )
    (comp (ref "R105")
      (value "100")
      (footprint "eagle-import:0603_1608METRIC")
      (fields
        (field (name "DISTRIBUTORPARTNO") "311-100GRCT-ND")
        (field (name "MANPARTNO") "RC0603JR-07100RL")
        (field (name "MANUFACTURER") "Yaego")
        (field (name "PACKAGE") "0603 (1608 Metric)")
      )
      (libsource (lib "eagle-import") (part "RESISTOR--5%-0603100"))
    )
    (comp (ref "R106")
      (value "100")
      (footprint "eagle-import:0603_1608METRIC")
      (fields
        (field (name "DISTRIBUTORPARTNO") "311-100GRCT-ND")
        (field (name "MANPARTNO") "RC0603JR-07100RL")
        (field (name "MANUFACTURER") "Yaego")
        (field (name "PACKAGE") "0603 (1608 Metric)")
      )
      (libsource (lib "eagle-import") (part "RESISTOR--5%-0603100"))
    )
    (comp (ref "R107")
      (value "100")
      (footprint "eagle-import:0603_1608METRIC")
      (fields
        (field (name "DISTRIBUTORPARTNO") "311-100GRCT-ND")
        (field (name "MANPARTNO") "RC0603JR-07100RL")
        (field (name "MANUFACTURER") "Yaego")
        (field (name "PACKAGE") "0603 (1608 Metric)")
      )
      (libsource (lib "eagle-import") (part "RESISTOR--5%-0603100"))
    )
    (comp (ref "R108")
      (value "100")
      (footprint "eagle-import:0603_1608METRIC")
      (fields
        (field (name "DISTRIBUTORPARTNO") "311-100GRCT-ND")
        (field (name "MANPARTNO") "RC0603JR-07100RL")
        (field (name "MANUFACTURER") "Yaego")
        (field (name "PACKAGE") "0603 (1608 Metric)")
      )
      (libsource (lib "eagle-import") (part "RESISTOR--5%-0603100"))
    )
    (comp (ref "R109")
      (value "100")
      (footprint "eagle-import:0603_1608METRIC")
      (fields
        (field (name "DISTRIBUTORPARTNO") "311-100GRCT-ND")
        (field (name "MANPARTNO") "RC0603JR-07100RL")
        (field (name "MANUFACTURER") "Yaego")
        (field (name "PACKAGE") "0603 (1608 Metric)")
      )
      (libsource (lib "eagle-import") (part "RESISTOR--5%-0603100"))
    )
    (comp (ref "R110")
      (value "100")
      (footprint "eagle-import:0603_1608METRIC")
      (fields
        (field (name "DISTRIBUTORPARTNO") "311-100GRCT-ND")
        (field (name "MANPARTNO") "RC0603JR-07100RL")
        (field (name "MANUFACTURER") "Yaego")
        (field (name "PACKAGE") "0603 (1608 Metric)")
      )
      (libsource (lib "eagle-import") (part "RESISTOR--5%-0603100"))
    )
    (comp (ref "R111")
      (value "100")
      (footprint "eagle-import:0603_1608METRIC")
      (fields
        (field (name "DISTRIBUTORPARTNO") "311-100GRCT-ND")
        (field (name "MANPARTNO") "RC0603JR-07100RL")
        (field (name "MANUFACTURER") "Yaego")
        (field (name "PACKAGE") "0603 (1608 Metric)")
      )
      (libsource (lib "eagle-import") (part "RESISTOR--5%-0603100"))
    )
    (comp (ref "R112")
      (value "100")
      (footprint "eagle-import:0603_1608METRIC")
      (fields
        (field (name "DISTRIBUTORPARTNO") "311-100GRCT-ND")
        (field (name "MANPARTNO") "RC0603JR-07100RL")
        (field (name "MANUFACTURER") "Yaego")
        (field (name "PACKAGE") "0603 (1608 Metric)")
      )
      (libsource (lib "eagle-import") (part "RESISTOR--5%-0603100"))
    )
    (comp (ref "R121")
      (value "2k")
      (footprint "eagle-import:0603_1608METRIC")
      (fields
        (field (name "DISTRIBUTORPARTNO") "311-2.0KGRCT-ND")
        (field (name "MANPARTNO") "RC0603JR-072KL")
        (field (name "MANUFACTURER") "Yaego")
      )
      (libsource (lib "eagle-import") (part "RESISTOR--5%-06032K"))
    )
    (comp (ref "R122")
      (value "2k")
      (footprint "eagle-import:0603_1608METRIC")
      (fields
        (field (name "DISTRIBUTORPARTNO") "311-2.0KGRCT-ND")
        (field (name "MANPARTNO") "RC0603JR-072KL")
        (field (name "MANUFACTURER") "Yaego")
      )
      (libsource (lib "eagle-import") (part "RESISTOR--5%-06032K"))
    )
    (comp (ref "R123")
      (value "2k")
      (footprint "eagle-import:0603_1608METRIC")
      (fields
        (field (name "DISTRIBUTORPARTNO") "311-2.0KGRCT-ND")
        (field (name "MANPARTNO") "RC0603JR-072KL")
        (field (name "MANUFACTURER") "Yaego")
      )
      (libsource (lib "eagle-import") (part "RESISTOR--5%-06032K"))
    )
    (comp (ref "R124")
      (value "2k")
      (footprint "eagle-import:0603_1608METRIC")
      (fields
        (field (name "DISTRIBUTORPARTNO") "311-2.0KGRCT-ND")
        (field (name "MANPARTNO") "RC0603JR-072KL")
        (field (name "MANUFACTURER") "Yaego")
      )
      (libsource (lib "eagle-import") (part "RESISTOR--5%-06032K"))
    )
    (comp (ref "R125")
      (value "2k")
      (footprint "eagle-import:0603_1608METRIC")
      (fields
        (field (name "DISTRIBUTORPARTNO") "311-2.0KGRCT-ND")
        (field (name "MANPARTNO") "RC0603JR-072KL")
        (field (name "MANUFACTURER") "Yaego")
      )
      (libsource (lib "eagle-import") (part "RESISTOR--5%-06032K"))
    )
    (comp (ref "R126")
      (value "2k")
      (footprint "eagle-import:0603_1608METRIC")
      (fields
        (field (name "DISTRIBUTORPARTNO") "311-2.0KGRCT-ND")
        (field (name "MANPARTNO") "RC0603JR-072KL")
        (field (name "MANUFACTURER") "Yaego")
      )
      (libsource (lib "eagle-import") (part "RESISTOR--5%-06032K"))
    )
    (comp (ref "R127")
      (value "2k")
      (footprint "eagle-import:0603_1608METRIC")
      (fields
        (field (name "DISTRIBUTORPARTNO") "311-2.0KGRCT-ND")
        (field (name "MANPARTNO") "RC0603JR-072KL")
        (field (name "MANUFACTURER") "Yaego")
      )
      (libsource (lib "eagle-import") (part "RESISTOR--5%-06032K"))
    )
    (comp (ref "R128")
      (value "2k")
      (footprint "eagle-import:0603_1608METRIC")
      (fields
        (field (name "DISTRIBUTORPARTNO") "311-2.0KGRCT-ND")
        (field (name "MANPARTNO") "RC0603JR-072KL")
        (field (name "MANUFACTURER") "Yaego")
      )
      (libsource (lib "eagle-import") (part "RESISTOR--5%-06032K"))
    )
    (comp (ref "R129")
      (value "100")
      (footprint "eagle-import:0603_1608METRIC")
      (fields
        (field (name "DISTRIBUTORPARTNO") "311-100GRCT-ND")
        (field (name "MANPARTNO") "RC0603JR-07100RL")
        (field (name "MANUFACTURER") "Yaego")
        (field (name "PACKAGE") "0603 (1608 Metric)")
      )
      (libsource (lib "eagle-import") (part "RESISTOR--5%-0603100"))
    )
    (comp (ref "R130")
      (value "100")
      (footprint "eagle-import:0603_1608METRIC")
      (fields
        (field (name "DISTRIBUTORPARTNO") "311-100GRCT-ND")
        (field (name "MANPARTNO") "RC0603JR-07100RL")
        (field (name "MANUFACTURER") "Yaego")
        (field (name "PACKAGE") "0603 (1608 Metric)")
      )
      (libsource (lib "eagle-import") (part "RESISTOR--5%-0603100"))
    )
    (comp (ref "R131")
      (value "100")
      (footprint "eagle-import:0603_1608METRIC")
      (fields
        (field (name "DISTRIBUTORPARTNO") "311-100GRCT-ND")
        (field (name "MANPARTNO") "RC0603JR-07100RL")
        (field (name "MANUFACTURER") "Yaego")
        (field (name "PACKAGE") "0603 (1608 Metric)")
      )
      (libsource (lib "eagle-import") (part "RESISTOR--5%-0603100"))
    )
    (comp (ref "R132")
      (value "100")
      (footprint "eagle-import:0603_1608METRIC")
      (fields
        (field (name "DISTRIBUTORPARTNO") "311-100GRCT-ND")
        (field (name "MANPARTNO") "RC0603JR-07100RL")
        (field (name "MANUFACTURER") "Yaego")
        (field (name "PACKAGE") "0603 (1608 Metric)")
      )
      (libsource (lib "eagle-import") (part "RESISTOR--5%-0603100"))
    )
    (comp (ref "R133")
      (value "100")
      (footprint "eagle-import:0603_1608METRIC")
      (fields
        (field (name "DISTRIBUTORPARTNO") "311-100GRCT-ND")
        (field (name "MANPARTNO") "RC0603JR-07100RL")
        (field (name "MANUFACTURER") "Yaego")
        (field (name "PACKAGE") "0603 (1608 Metric)")
      )
      (libsource (lib "eagle-import") (part "RESISTOR--5%-0603100"))
    )
    (comp (ref "R134")
      (value "100")
      (footprint "eagle-import:0603_1608METRIC")
      (fields
        (field (name "DISTRIBUTORPARTNO") "311-100GRCT-ND")
        (field (name "MANPARTNO") "RC0603JR-07100RL")
        (field (name "MANUFACTURER") "Yaego")
        (field (name "PACKAGE") "0603 (1608 Metric)")
      )
      (libsource (lib "eagle-import") (part "RESISTOR--5%-0603100"))
    )
    (comp (ref "R135")
      (value "100")
      (footprint "eagle-import:0603_1608METRIC")
      (fields
        (field (name "DISTRIBUTORPARTNO") "311-100GRCT-ND")
        (field (name "MANPARTNO") "RC0603JR-07100RL")
        (field (name "MANUFACTURER") "Yaego")
        (field (name "PACKAGE") "0603 (1608 Metric)")
      )
      (libsource (lib "eagle-import") (part "RESISTOR--5%-0603100"))
    )
    (comp (ref "R136")
      (value "100")
      (footprint "eagle-import:0603_1608METRIC")
      (fields
        (field (name "DISTRIBUTORPARTNO") "311-100GRCT-ND")
        (field (name "MANPARTNO") "RC0603JR-07100RL")
        (field (name "MANUFACTURER") "Yaego")
        (field (name "PACKAGE") "0603 (1608 Metric)")
      )
      (libsource (lib "eagle-import") (part "RESISTOR--5%-0603100"))
    )
    (comp (ref "R137")
      (value "100")
      (footprint "eagle-import:0603_1608METRIC")
      (fields
        (field (name "DISTRIBUTORPARTNO") "311-100GRCT-ND")
        (field (name "MANPARTNO") "RC0603JR-07100RL")
        (field (name "MANUFACTURER") "Yaego")
        (field (name "PACKAGE") "0603 (1608 Metric)")
      )
      (libsource (lib "eagle-import") (part "RESISTOR--5%-0603100"))
    )
    (comp (ref "R138")
      (value "100")
      (footprint "eagle-import:0603_1608METRIC")
      (fields
        (field (name "DISTRIBUTORPARTNO") "311-100GRCT-ND")
        (field (name "MANPARTNO") "RC0603JR-07100RL")
        (field (name "MANUFACTURER") "Yaego")
        (field (name "PACKAGE") "0603 (1608 Metric)")
      )
      (libsource (lib "eagle-import") (part "RESISTOR--5%-0603100"))
    )
    (comp (ref "R139")
      (value "100")
      (footprint "eagle-import:0603_1608METRIC")
      (fields
        (field (name "DISTRIBUTORPARTNO") "311-100GRCT-ND")
        (field (name "MANPARTNO") "RC0603JR-07100RL")
        (field (name "MANUFACTURER") "Yaego")
        (field (name "PACKAGE") "0603 (1608 Metric)")
      )
      (libsource (lib "eagle-import") (part "RESISTOR--5%-0603100"))
    )
    (comp (ref "R140")
      (value "100")
      (footprint "eagle-import:0603_1608METRIC")
      (fields
        (field (name "DISTRIBUTORPARTNO") "311-100GRCT-ND")
        (field (name "MANPARTNO") "RC0603JR-07100RL")
        (field (name "MANUFACTURER") "Yaego")
        (field (name "PACKAGE") "0603 (1608 Metric)")
      )
      (libsource (lib "eagle-import") (part "RESISTOR--5%-0603100"))
    )
    (comp (ref "R141")
      (value "100")
      (footprint "eagle-import:0603_1608METRIC")
      (fields
        (field (name "DISTRIBUTORPARTNO") "311-100GRCT-ND")
        (field (name "MANPARTNO") "RC0603JR-07100RL")
        (field (name "MANUFACTURER") "Yaego")
        (field (name "PACKAGE") "0603 (1608 Metric)")
      )
      (libsource (lib "eagle-import") (part "RESISTOR--5%-0603100"))
    )
    (comp (ref "R142")
      (value "100")
      (footprint "eagle-import:0603_1608METRIC")
      (fields
        (field (name "DISTRIBUTORPARTNO") "311-100GRCT-ND")
        (field (name "MANPARTNO") "RC0603JR-07100RL")
        (field (name "MANUFACTURER") "Yaego")
        (field (name "PACKAGE") "0603 (1608 Metric)")
      )
      (libsource (lib "eagle-import") (part "RESISTOR--5%-0603100"))
    )
    (comp (ref "R143")
      (value "100")
      (footprint "eagle-import:0603_1608METRIC")
      (fields
        (field (name "DISTRIBUTORPARTNO") "311-100GRCT-ND")
        (field (name "MANPARTNO") "RC0603JR-07100RL")
        (field (name "MANUFACTURER") "Yaego")
        (field (name "PACKAGE") "0603 (1608 Metric)")
      )
      (libsource (lib "eagle-import") (part "RESISTOR--5%-0603100"))
    )
    (comp (ref "R144")
      (value "100")
      (footprint "eagle-import:0603_1608METRIC")
      (fields
        (field (name "DISTRIBUTORPARTNO") "311-100GRCT-ND")
        (field (name "MANPARTNO") "RC0603JR-07100RL")
        (field (name "MANUFACTURER") "Yaego")
        (field (name "PACKAGE") "0603 (1608 Metric)")
      )
      (libsource (lib "eagle-import") (part "RESISTOR--5%-0603100"))
    )
    (comp (ref "R161")
      (value "100")
      (footprint "eagle-import:0603_1608METRIC")
      (fields
        (field (name "DISTRIBUTORPARTNO") "311-100GRCT-ND")
        (field (name "MANPARTNO") "RC0603JR-07100RL")
        (field (name "MANUFACTURER") "Yaego")
        (field (name "PACKAGE") "0603 (1608 Metric)")
      )
      (libsource (lib "eagle-import") (part "RESISTOR--5%-0603100"))
    )
    (comp (ref "R162")
      (value "100")
      (footprint "eagle-import:0603_1608METRIC")
      (fields
        (field (name "DISTRIBUTORPARTNO") "311-100GRCT-ND")
        (field (name "MANPARTNO") "RC0603JR-07100RL")
        (field (name "MANUFACTURER") "Yaego")
        (field (name "PACKAGE") "0603 (1608 Metric)")
      )
      (libsource (lib "eagle-import") (part "RESISTOR--5%-0603100"))
    )
    (comp (ref "R163")
      (value "100")
      (footprint "eagle-import:0603_1608METRIC")
      (fields
        (field (name "DISTRIBUTORPARTNO") "311-100GRCT-ND")
        (field (name "MANPARTNO") "RC0603JR-07100RL")
        (field (name "MANUFACTURER") "Yaego")
        (field (name "PACKAGE") "0603 (1608 Metric)")
      )
      (libsource (lib "eagle-import") (part "RESISTOR--5%-0603100"))
    )
    (comp (ref "R164")
      (value "100")
      (footprint "eagle-import:0603_1608METRIC")
      (fields
        (field (name "DISTRIBUTORPARTNO") "311-100GRCT-ND")
        (field (name "MANPARTNO") "RC0603JR-07100RL")
        (field (name "MANUFACTURER") "Yaego")
        (field (name "PACKAGE") "0603 (1608 Metric)")
      )
      (libsource (lib "eagle-import") (part "RESISTOR--5%-0603100"))
    )
    (comp (ref "R165")
      (value "100")
      (footprint "eagle-import:0603_1608METRIC")
      (fields
        (field (name "DISTRIBUTORPARTNO") "311-100GRCT-ND")
        (field (name "MANPARTNO") "RC0603JR-07100RL")
        (field (name "MANUFACTURER") "Yaego")
        (field (name "PACKAGE") "0603 (1608 Metric)")
      )
      (libsource (lib "eagle-import") (part "RESISTOR--5%-0603100"))
    )
    (comp (ref "R166")
      (value "100")
      (footprint "eagle-import:0603_1608METRIC")
      (fields
        (field (name "DISTRIBUTORPARTNO") "311-100GRCT-ND")
        (field (name "MANPARTNO") "RC0603JR-07100RL")
        (field (name "MANUFACTURER") "Yaego")
        (field (name "PACKAGE") "0603 (1608 Metric)")
      )
      (libsource (lib "eagle-import") (part "RESISTOR--5%-0603100"))
    )
    (comp (ref "R167")
      (value "100")
      (footprint "eagle-import:0603_1608METRIC")
      (fields
        (field (name "DISTRIBUTORPARTNO") "311-100GRCT-ND")
        (field (name "MANPARTNO") "RC0603JR-07100RL")
        (field (name "MANUFACTURER") "Yaego")
        (field (name "PACKAGE") "0603 (1608 Metric)")
      )
      (libsource (lib "eagle-import") (part "RESISTOR--5%-0603100"))
    )
    (comp (ref "R168")
      (value "100")
      (footprint "eagle-import:0603_1608METRIC")
      (fields
        (field (name "DISTRIBUTORPARTNO") "311-100GRCT-ND")
        (field (name "MANPARTNO") "RC0603JR-07100RL")
        (field (name "MANUFACTURER") "Yaego")
        (field (name "PACKAGE") "0603 (1608 Metric)")
      )
      (libsource (lib "eagle-import") (part "RESISTOR--5%-0603100"))
    )
    (comp (ref "R169")
      (value "100")
      (footprint "eagle-import:0603_1608METRIC")
      (fields
        (field (name "DISTRIBUTORPARTNO") "311-100GRCT-ND")
        (field (name "MANPARTNO") "RC0603JR-07100RL")
        (field (name "MANUFACTURER") "Yaego")
        (field (name "PACKAGE") "0603 (1608 Metric)")
      )
      (libsource (lib "eagle-import") (part "RESISTOR--5%-0603100"))
    )
    (comp (ref "R170")
      (value "100")
      (footprint "eagle-import:0603_1608METRIC")
      (fields
        (field (name "DISTRIBUTORPARTNO") "311-100GRCT-ND")
        (field (name "MANPARTNO") "RC0603JR-07100RL")
        (field (name "MANUFACTURER") "Yaego")
        (field (name "PACKAGE") "0603 (1608 Metric)")
      )
      (libsource (lib "eagle-import") (part "RESISTOR--5%-0603100"))
    )
    (comp (ref "R171")
      (value "100")
      (footprint "eagle-import:0603_1608METRIC")
      (fields
        (field (name "DISTRIBUTORPARTNO") "311-100GRCT-ND")
        (field (name "MANPARTNO") "RC0603JR-07100RL")
        (field (name "MANUFACTURER") "Yaego")
        (field (name "PACKAGE") "0603 (1608 Metric)")
      )
      (libsource (lib "eagle-import") (part "RESISTOR--5%-0603100"))
    )
    (comp (ref "R172")
      (value "100")
      (footprint "eagle-import:0603_1608METRIC")
      (fields
        (field (name "DISTRIBUTORPARTNO") "311-100GRCT-ND")
        (field (name "MANPARTNO") "RC0603JR-07100RL")
        (field (name "MANUFACTURER") "Yaego")
        (field (name "PACKAGE") "0603 (1608 Metric)")
      )
      (libsource (lib "eagle-import") (part "RESISTOR--5%-0603100"))
    )
    (comp (ref "R173")
      (value "100")
      (footprint "eagle-import:0603_1608METRIC")
      (fields
        (field (name "DISTRIBUTORPARTNO") "311-100GRCT-ND")
        (field (name "MANPARTNO") "RC0603JR-07100RL")
        (field (name "MANUFACTURER") "Yaego")
        (field (name "PACKAGE") "0603 (1608 Metric)")
      )
      (libsource (lib "eagle-import") (part "RESISTOR--5%-0603100"))
    )
    (comp (ref "R174")
      (value "100")
      (footprint "eagle-import:0603_1608METRIC")
      (fields
        (field (name "DISTRIBUTORPARTNO") "311-100GRCT-ND")
        (field (name "MANPARTNO") "RC0603JR-07100RL")
        (field (name "MANUFACTURER") "Yaego")
        (field (name "PACKAGE") "0603 (1608 Metric)")
      )
      (libsource (lib "eagle-import") (part "RESISTOR--5%-0603100"))
    )
    (comp (ref "R175")
      (value "100")
      (footprint "eagle-import:0603_1608METRIC")
      (fields
        (field (name "DISTRIBUTORPARTNO") "311-100GRCT-ND")
        (field (name "MANPARTNO") "RC0603JR-07100RL")
        (field (name "MANUFACTURER") "Yaego")
        (field (name "PACKAGE") "0603 (1608 Metric)")
      )
      (libsource (lib "eagle-import") (part "RESISTOR--5%-0603100"))
    )
    (comp (ref "R176")
      (value "100")
      (footprint "eagle-import:0603_1608METRIC")
      (fields
        (field (name "DISTRIBUTORPARTNO") "311-100GRCT-ND")
        (field (name "MANPARTNO") "RC0603JR-07100RL")
        (field (name "MANUFACTURER") "Yaego")
        (field (name "PACKAGE") "0603 (1608 Metric)")
      )
      (libsource (lib "eagle-import") (part "RESISTOR--5%-0603100"))
    )
    (comp (ref "R193")
      (value "100")
      (footprint "eagle-import:0603_1608METRIC")
      (fields
        (field (name "DISTRIBUTORPARTNO") "311-100GRCT-ND")
        (field (name "MANPARTNO") "RC0603JR-07100RL")
        (field (name "MANUFACTURER") "Yaego")
        (field (name "PACKAGE") "0603 (1608 Metric)")
      )
      (libsource (lib "eagle-import") (part "RESISTOR--5%-0603100"))
    )
    (comp (ref "R194")
      (value "100")
      (footprint "eagle-import:0603_1608METRIC")
      (fields
        (field (name "DISTRIBUTORPARTNO") "311-100GRCT-ND")
        (field (name "MANPARTNO") "RC0603JR-07100RL")
        (field (name "MANUFACTURER") "Yaego")
        (field (name "PACKAGE") "0603 (1608 Metric)")
      )
      (libsource (lib "eagle-import") (part "RESISTOR--5%-0603100"))
    )
    (comp (ref "R195")
      (value "100")
      (footprint "eagle-import:0603_1608METRIC")
      (fields
        (field (name "DISTRIBUTORPARTNO") "311-100GRCT-ND")
        (field (name "MANPARTNO") "RC0603JR-07100RL")
        (field (name "MANUFACTURER") "Yaego")
        (field (name "PACKAGE") "0603 (1608 Metric)")
      )
      (libsource (lib "eagle-import") (part "RESISTOR--5%-0603100"))
    )
    (comp (ref "R196")
      (value "100")
      (footprint "eagle-import:0603_1608METRIC")
      (fields
        (field (name "DISTRIBUTORPARTNO") "311-100GRCT-ND")
        (field (name "MANPARTNO") "RC0603JR-07100RL")
        (field (name "MANUFACTURER") "Yaego")
        (field (name "PACKAGE") "0603 (1608 Metric)")
      )
      (libsource (lib "eagle-import") (part "RESISTOR--5%-0603100"))
    )
    (comp (ref "R197")
      (value "100")
      (footprint "eagle-import:0603_1608METRIC")
      (fields
        (field (name "DISTRIBUTORPARTNO") "311-100GRCT-ND")
        (field (name "MANPARTNO") "RC0603JR-07100RL")
        (field (name "MANUFACTURER") "Yaego")
        (field (name "PACKAGE") "0603 (1608 Metric)")
      )
      (libsource (lib "eagle-import") (part "RESISTOR--5%-0603100"))
    )
    (comp (ref "R198")
      (value "100")
      (footprint "eagle-import:0603_1608METRIC")
      (fields
        (field (name "DISTRIBUTORPARTNO") "311-100GRCT-ND")
        (field (name "MANPARTNO") "RC0603JR-07100RL")
        (field (name "MANUFACTURER") "Yaego")
        (field (name "PACKAGE") "0603 (1608 Metric)")
      )
      (libsource (lib "eagle-import") (part "RESISTOR--5%-0603100"))
    )
    (comp (ref "R199")
      (value "100")
      (footprint "eagle-import:0603_1608METRIC")
      (fields
        (field (name "DISTRIBUTORPARTNO") "311-100GRCT-ND")
        (field (name "MANPARTNO") "RC0603JR-07100RL")
        (field (name "MANUFACTURER") "Yaego")
        (field (name "PACKAGE") "0603 (1608 Metric)")
      )
      (libsource (lib "eagle-import") (part "RESISTOR--5%-0603100"))
    )
    (comp (ref "R200")
      (value "100")
      (footprint "eagle-import:0603_1608METRIC")
      (fields
        (field (name "DISTRIBUTORPARTNO") "311-100GRCT-ND")
        (field (name "MANPARTNO") "RC0603JR-07100RL")
        (field (name "MANUFACTURER") "Yaego")
        (field (name "PACKAGE") "0603 (1608 Metric)")
      )
      (libsource (lib "eagle-import") (part "RESISTOR--5%-0603100"))
    )
    (comp (ref "R201")
      (value "100")
      (footprint "eagle-import:0603_1608METRIC")
      (fields
        (field (name "DISTRIBUTORPARTNO") "311-100GRCT-ND")
        (field (name "MANPARTNO") "RC0603JR-07100RL")
        (field (name "MANUFACTURER") "Yaego")
        (field (name "PACKAGE") "0603 (1608 Metric)")
      )
      (libsource (lib "eagle-import") (part "RESISTOR--5%-0603100"))
    )
    (comp (ref "R202")
      (value "100")
      (footprint "eagle-import:0603_1608METRIC")
      (fields
        (field (name "DISTRIBUTORPARTNO") "311-100GRCT-ND")
        (field (name "MANPARTNO") "RC0603JR-07100RL")
        (field (name "MANUFACTURER") "Yaego")
        (field (name "PACKAGE") "0603 (1608 Metric)")
      )
      (libsource (lib "eagle-import") (part "RESISTOR--5%-0603100"))
    )
    (comp (ref "R203")
      (value "100")
      (footprint "eagle-import:0603_1608METRIC")
      (fields
        (field (name "DISTRIBUTORPARTNO") "311-100GRCT-ND")
        (field (name "MANPARTNO") "RC0603JR-07100RL")
        (field (name "MANUFACTURER") "Yaego")
        (field (name "PACKAGE") "0603 (1608 Metric)")
      )
      (libsource (lib "eagle-import") (part "RESISTOR--5%-0603100"))
    )
    (comp (ref "R204")
      (value "100")
      (footprint "eagle-import:0603_1608METRIC")
      (fields
        (field (name "DISTRIBUTORPARTNO") "311-100GRCT-ND")
        (field (name "MANPARTNO") "RC0603JR-07100RL")
        (field (name "MANUFACTURER") "Yaego")
        (field (name "PACKAGE") "0603 (1608 Metric)")
      )
      (libsource (lib "eagle-import") (part "RESISTOR--5%-0603100"))
    )
    (comp (ref "R205")
      (value "100")
      (footprint "eagle-import:0603_1608METRIC")
      (fields
        (field (name "DISTRIBUTORPARTNO") "311-100GRCT-ND")
        (field (name "MANPARTNO") "RC0603JR-07100RL")
        (field (name "MANUFACTURER") "Yaego")
        (field (name "PACKAGE") "0603 (1608 Metric)")
      )
      (libsource (lib "eagle-import") (part "RESISTOR--5%-0603100"))
    )
    (comp (ref "R206")
      (value "100")
      (footprint "eagle-import:0603_1608METRIC")
      (fields
        (field (name "DISTRIBUTORPARTNO") "311-100GRCT-ND")
        (field (name "MANPARTNO") "RC0603JR-07100RL")
        (field (name "MANUFACTURER") "Yaego")
        (field (name "PACKAGE") "0603 (1608 Metric)")
      )
      (libsource (lib "eagle-import") (part "RESISTOR--5%-0603100"))
    )
    (comp (ref "R207")
      (value "100")
      (footprint "eagle-import:0603_1608METRIC")
      (fields
        (field (name "DISTRIBUTORPARTNO") "311-100GRCT-ND")
        (field (name "MANPARTNO") "RC0603JR-07100RL")
        (field (name "MANUFACTURER") "Yaego")
        (field (name "PACKAGE") "0603 (1608 Metric)")
      )
      (libsource (lib "eagle-import") (part "RESISTOR--5%-0603100"))
    )
    (comp (ref "R208")
      (value "100")
      (footprint "eagle-import:0603_1608METRIC")
      (fields
        (field (name "DISTRIBUTORPARTNO") "311-100GRCT-ND")
        (field (name "MANPARTNO") "RC0603JR-07100RL")
        (field (name "MANUFACTURER") "Yaego")
        (field (name "PACKAGE") "0603 (1608 Metric)")
      )
      (libsource (lib "eagle-import") (part "RESISTOR--5%-0603100"))
    )
    (comp (ref "R225")
      (value "100")
      (footprint "eagle-import:0603_1608METRIC")
      (fields
        (field (name "DISTRIBUTORPARTNO") "311-100GRCT-ND")
        (field (name "MANPARTNO") "RC0603JR-07100RL")
        (field (name "MANUFACTURER") "Yaego")
        (field (name "PACKAGE") "0603 (1608 Metric)")
      )
      (libsource (lib "eagle-import") (part "RESISTOR--5%-0603100"))
    )
    (comp (ref "R226")
      (value "100")
      (footprint "eagle-import:0603_1608METRIC")
      (fields
        (field (name "DISTRIBUTORPARTNO") "311-100GRCT-ND")
        (field (name "MANPARTNO") "RC0603JR-07100RL")
        (field (name "MANUFACTURER") "Yaego")
        (field (name "PACKAGE") "0603 (1608 Metric)")
      )
      (libsource (lib "eagle-import") (part "RESISTOR--5%-0603100"))
    )
    (comp (ref "R227")
      (value "100")
      (footprint "eagle-import:0603_1608METRIC")
      (fields
        (field (name "DISTRIBUTORPARTNO") "311-100GRCT-ND")
        (field (name "MANPARTNO") "RC0603JR-07100RL")
        (field (name "MANUFACTURER") "Yaego")
        (field (name "PACKAGE") "0603 (1608 Metric)")
      )
      (libsource (lib "eagle-import") (part "RESISTOR--5%-0603100"))
    )
    (comp (ref "R228")
      (value "100")
      (footprint "eagle-import:0603_1608METRIC")
      (fields
        (field (name "DISTRIBUTORPARTNO") "311-100GRCT-ND")
        (field (name "MANPARTNO") "RC0603JR-07100RL")
        (field (name "MANUFACTURER") "Yaego")
        (field (name "PACKAGE") "0603 (1608 Metric)")
      )
      (libsource (lib "eagle-import") (part "RESISTOR--5%-0603100"))
    )
    (comp (ref "R229")
      (value "100")
      (footprint "eagle-import:0603_1608METRIC")
      (fields
        (field (name "DISTRIBUTORPARTNO") "311-100GRCT-ND")
        (field (name "MANPARTNO") "RC0603JR-07100RL")
        (field (name "MANUFACTURER") "Yaego")
        (field (name "PACKAGE") "0603 (1608 Metric)")
      )
      (libsource (lib "eagle-import") (part "RESISTOR--5%-0603100"))
    )
    (comp (ref "R230")
      (value "100")
      (footprint "eagle-import:0603_1608METRIC")
      (fields
        (field (name "DISTRIBUTORPARTNO") "311-100GRCT-ND")
        (field (name "MANPARTNO") "RC0603JR-07100RL")
        (field (name "MANUFACTURER") "Yaego")
        (field (name "PACKAGE") "0603 (1608 Metric)")
      )
      (libsource (lib "eagle-import") (part "RESISTOR--5%-0603100"))
    )
    (comp (ref "R231")
      (value "100")
      (footprint "eagle-import:0603_1608METRIC")
      (fields
        (field (name "DISTRIBUTORPARTNO") "311-100GRCT-ND")
        (field (name "MANPARTNO") "RC0603JR-07100RL")
        (field (name "MANUFACTURER") "Yaego")
        (field (name "PACKAGE") "0603 (1608 Metric)")
      )
      (libsource (lib "eagle-import") (part "RESISTOR--5%-0603100"))
    )
    (comp (ref "R232")
      (value "100")
      (footprint "eagle-import:0603_1608METRIC")
      (fields
        (field (name "DISTRIBUTORPARTNO") "311-100GRCT-ND")
        (field (name "MANPARTNO") "RC0603JR-07100RL")
        (field (name "MANUFACTURER") "Yaego")
        (field (name "PACKAGE") "0603 (1608 Metric)")
      )
      (libsource (lib "eagle-import") (part "RESISTOR--5%-0603100"))
    )
    (comp (ref "R233")
      (value "100")
      (footprint "eagle-import:0603_1608METRIC")
      (fields
        (field (name "DISTRIBUTORPARTNO") "311-100GRCT-ND")
        (field (name "MANPARTNO") "RC0603JR-07100RL")
        (field (name "MANUFACTURER") "Yaego")
        (field (name "PACKAGE") "0603 (1608 Metric)")
      )
      (libsource (lib "eagle-import") (part "RESISTOR--5%-0603100"))
    )
    (comp (ref "R234")
      (value "100")
      (footprint "eagle-import:0603_1608METRIC")
      (fields
        (field (name "DISTRIBUTORPARTNO") "311-100GRCT-ND")
        (field (name "MANPARTNO") "RC0603JR-07100RL")
        (field (name "MANUFACTURER") "Yaego")
        (field (name "PACKAGE") "0603 (1608 Metric)")
      )
      (libsource (lib "eagle-import") (part "RESISTOR--5%-0603100"))
    )
    (comp (ref "R235")
      (value "100")
      (footprint "eagle-import:0603_1608METRIC")
      (fields
        (field (name "DISTRIBUTORPARTNO") "311-100GRCT-ND")
        (field (name "MANPARTNO") "RC0603JR-07100RL")
        (field (name "MANUFACTURER") "Yaego")
        (field (name "PACKAGE") "0603 (1608 Metric)")
      )
      (libsource (lib "eagle-import") (part "RESISTOR--5%-0603100"))
    )
    (comp (ref "R236")
      (value "100")
      (footprint "eagle-import:0603_1608METRIC")
      (fields
        (field (name "DISTRIBUTORPARTNO") "311-100GRCT-ND")
        (field (name "MANPARTNO") "RC0603JR-07100RL")
        (field (name "MANUFACTURER") "Yaego")
        (field (name "PACKAGE") "0603 (1608 Metric)")
      )
      (libsource (lib "eagle-import") (part "RESISTOR--5%-0603100"))
    )
    (comp (ref "R237")
      (value "100")
      (footprint "eagle-import:0603_1608METRIC")
      (fields
        (field (name "DISTRIBUTORPARTNO") "311-100GRCT-ND")
        (field (name "MANPARTNO") "RC0603JR-07100RL")
        (field (name "MANUFACTURER") "Yaego")
        (field (name "PACKAGE") "0603 (1608 Metric)")
      )
      (libsource (lib "eagle-import") (part "RESISTOR--5%-0603100"))
    )
    (comp (ref "R238")
      (value "100")
      (footprint "eagle-import:0603_1608METRIC")
      (fields
        (field (name "DISTRIBUTORPARTNO") "311-100GRCT-ND")
        (field (name "MANPARTNO") "RC0603JR-07100RL")
        (field (name "MANUFACTURER") "Yaego")
        (field (name "PACKAGE") "0603 (1608 Metric)")
      )
      (libsource (lib "eagle-import") (part "RESISTOR--5%-0603100"))
    )
    (comp (ref "R239")
      (value "100")
      (footprint "eagle-import:0603_1608METRIC")
      (fields
        (field (name "DISTRIBUTORPARTNO") "311-100GRCT-ND")
        (field (name "MANPARTNO") "RC0603JR-07100RL")
        (field (name "MANUFACTURER") "Yaego")
        (field (name "PACKAGE") "0603 (1608 Metric)")
      )
      (libsource (lib "eagle-import") (part "RESISTOR--5%-0603100"))
    )
    (comp (ref "R240")
      (value "100")
      (footprint "eagle-import:0603_1608METRIC")
      (fields
        (field (name "DISTRIBUTORPARTNO") "311-100GRCT-ND")
        (field (name "MANPARTNO") "RC0603JR-07100RL")
        (field (name "MANUFACTURER") "Yaego")
        (field (name "PACKAGE") "0603 (1608 Metric)")
      )
      (libsource (lib "eagle-import") (part "RESISTOR--5%-0603100"))
    )
    (comp (ref "R257")
      (value "100")
      (footprint "eagle-import:0603_1608METRIC")
      (fields
        (field (name "DISTRIBUTORPARTNO") "311-100GRCT-ND")
        (field (name "MANPARTNO") "RC0603JR-07100RL")
        (field (name "MANUFACTURER") "Yaego")
        (field (name "PACKAGE") "0603 (1608 Metric)")
      )
      (libsource (lib "eagle-import") (part "RESISTOR--5%-0603100"))
    )
    (comp (ref "R258")
      (value "100")
      (footprint "eagle-import:0603_1608METRIC")
      (fields
        (field (name "DISTRIBUTORPARTNO") "311-100GRCT-ND")
        (field (name "MANPARTNO") "RC0603JR-07100RL")
        (field (name "MANUFACTURER") "Yaego")
        (field (name "PACKAGE") "0603 (1608 Metric)")
      )
      (libsource (lib "eagle-import") (part "RESISTOR--5%-0603100"))
    )
    (comp (ref "R259")
      (value "100")
      (footprint "eagle-import:0603_1608METRIC")
      (fields
        (field (name "DISTRIBUTORPARTNO") "311-100GRCT-ND")
        (field (name "MANPARTNO") "RC0603JR-07100RL")
        (field (name "MANUFACTURER") "Yaego")
        (field (name "PACKAGE") "0603 (1608 Metric)")
      )
      (libsource (lib "eagle-import") (part "RESISTOR--5%-0603100"))
    )
    (comp (ref "R260")
      (value "100")
      (footprint "eagle-import:0603_1608METRIC")
      (fields
        (field (name "DISTRIBUTORPARTNO") "311-100GRCT-ND")
        (field (name "MANPARTNO") "RC0603JR-07100RL")
        (field (name "MANUFACTURER") "Yaego")
        (field (name "PACKAGE") "0603 (1608 Metric)")
      )
      (libsource (lib "eagle-import") (part "RESISTOR--5%-0603100"))
    )
    (comp (ref "R261")
      (value "100")
      (footprint "eagle-import:0603_1608METRIC")
      (fields
        (field (name "DISTRIBUTORPARTNO") "311-100GRCT-ND")
        (field (name "MANPARTNO") "RC0603JR-07100RL")
        (field (name "MANUFACTURER") "Yaego")
        (field (name "PACKAGE") "0603 (1608 Metric)")
      )
      (libsource (lib "eagle-import") (part "RESISTOR--5%-0603100"))
    )
    (comp (ref "R262")
      (value "100")
      (footprint "eagle-import:0603_1608METRIC")
      (fields
        (field (name "DISTRIBUTORPARTNO") "311-100GRCT-ND")
        (field (name "MANPARTNO") "RC0603JR-07100RL")
        (field (name "MANUFACTURER") "Yaego")
        (field (name "PACKAGE") "0603 (1608 Metric)")
      )
      (libsource (lib "eagle-import") (part "RESISTOR--5%-0603100"))
    )
    (comp (ref "R263")
      (value "100")
      (footprint "eagle-import:0603_1608METRIC")
      (fields
        (field (name "DISTRIBUTORPARTNO") "311-100GRCT-ND")
        (field (name "MANPARTNO") "RC0603JR-07100RL")
        (field (name "MANUFACTURER") "Yaego")
        (field (name "PACKAGE") "0603 (1608 Metric)")
      )
      (libsource (lib "eagle-import") (part "RESISTOR--5%-0603100"))
    )
    (comp (ref "R264")
      (value "100")
      (footprint "eagle-import:0603_1608METRIC")
      (fields
        (field (name "DISTRIBUTORPARTNO") "311-100GRCT-ND")
        (field (name "MANPARTNO") "RC0603JR-07100RL")
        (field (name "MANUFACTURER") "Yaego")
        (field (name "PACKAGE") "0603 (1608 Metric)")
      )
      (libsource (lib "eagle-import") (part "RESISTOR--5%-0603100"))
    )
    (comp (ref "R265")
      (value "100")
      (footprint "eagle-import:0603_1608METRIC")
      (fields
        (field (name "DISTRIBUTORPARTNO") "311-100GRCT-ND")
        (field (name "MANPARTNO") "RC0603JR-07100RL")
        (field (name "MANUFACTURER") "Yaego")
        (field (name "PACKAGE") "0603 (1608 Metric)")
      )
      (libsource (lib "eagle-import") (part "RESISTOR--5%-0603100"))
    )
    (comp (ref "R266")
      (value "100")
      (footprint "eagle-import:0603_1608METRIC")
      (fields
        (field (name "DISTRIBUTORPARTNO") "311-100GRCT-ND")
        (field (name "MANPARTNO") "RC0603JR-07100RL")
        (field (name "MANUFACTURER") "Yaego")
        (field (name "PACKAGE") "0603 (1608 Metric)")
      )
      (libsource (lib "eagle-import") (part "RESISTOR--5%-0603100"))
    )
    (comp (ref "R267")
      (value "100")
      (footprint "eagle-import:0603_1608METRIC")
      (fields
        (field (name "DISTRIBUTORPARTNO") "311-100GRCT-ND")
        (field (name "MANPARTNO") "RC0603JR-07100RL")
        (field (name "MANUFACTURER") "Yaego")
        (field (name "PACKAGE") "0603 (1608 Metric)")
      )
      (libsource (lib "eagle-import") (part "RESISTOR--5%-0603100"))
    )
    (comp (ref "R268")
      (value "100")
      (footprint "eagle-import:0603_1608METRIC")
      (fields
        (field (name "DISTRIBUTORPARTNO") "311-100GRCT-ND")
        (field (name "MANPARTNO") "RC0603JR-07100RL")
        (field (name "MANUFACTURER") "Yaego")
        (field (name "PACKAGE") "0603 (1608 Metric)")
      )
      (libsource (lib "eagle-import") (part "RESISTOR--5%-0603100"))
    )
    (comp (ref "R269")
      (value "100")
      (footprint "eagle-import:0603_1608METRIC")
      (fields
        (field (name "DISTRIBUTORPARTNO") "311-100GRCT-ND")
        (field (name "MANPARTNO") "RC0603JR-07100RL")
        (field (name "MANUFACTURER") "Yaego")
        (field (name "PACKAGE") "0603 (1608 Metric)")
      )
      (libsource (lib "eagle-import") (part "RESISTOR--5%-0603100"))
    )
    (comp (ref "R270")
      (value "100")
      (footprint "eagle-import:0603_1608METRIC")
      (fields
        (field (name "DISTRIBUTORPARTNO") "311-100GRCT-ND")
        (field (name "MANPARTNO") "RC0603JR-07100RL")
        (field (name "MANUFACTURER") "Yaego")
        (field (name "PACKAGE") "0603 (1608 Metric)")
      )
      (libsource (lib "eagle-import") (part "RESISTOR--5%-0603100"))
    )
    (comp (ref "R271")
      (value "100")
      (footprint "eagle-import:0603_1608METRIC")
      (fields
        (field (name "DISTRIBUTORPARTNO") "311-100GRCT-ND")
        (field (name "MANPARTNO") "RC0603JR-07100RL")
        (field (name "MANUFACTURER") "Yaego")
        (field (name "PACKAGE") "0603 (1608 Metric)")
      )
      (libsource (lib "eagle-import") (part "RESISTOR--5%-0603100"))
    )
    (comp (ref "R272")
      (value "100")
      (footprint "eagle-import:0603_1608METRIC")
      (fields
        (field (name "DISTRIBUTORPARTNO") "311-100GRCT-ND")
        (field (name "MANPARTNO") "RC0603JR-07100RL")
        (field (name "MANUFACTURER") "Yaego")
        (field (name "PACKAGE") "0603 (1608 Metric)")
      )
      (libsource (lib "eagle-import") (part "RESISTOR--5%-0603100"))
    )
    (comp (ref "R289")
      (value "47k")
      (footprint "eagle-import:0603_1608METRIC")
      (fields
        (field (name "DISTRIBUTORPARTNO") "311-47KGRCT-ND")
        (field (name "MANPARTNO") "RC0603JR-0747KL")
        (field (name "MANUFACTURER") "Yaego")
      )
      (libsource (lib "eagle-import") (part "RESISTOR--5%-060347K"))
    )
    (comp (ref "RX")
      (value "HEADERPIN")
      (footprint "eagle-import:HEADERPIN")
      (libsource (lib "eagle-import") (part "HEADERPIN"))
    )
    (comp (ref "SW1")
      (value "4mm")
      (footprint "eagle-import:FSM16JHSWITCH")
      (fields
        (field (name "DISTRIBUTORPARTNO") "450-1650-ND")
        (field (name "MANPARTNO") "FSM4JH")
        (field (name "MANUFACTURER") "TE Connectivity")
      )
      (libsource (lib "eagle-import") (part "SWITCH-TACT-TH"))
    )
    (comp (ref "SW2")
      (value "4mm")
      (footprint "eagle-import:FSM16JHSWITCH")
      (fields
        (field (name "DISTRIBUTORPARTNO") "450-1650-ND")
        (field (name "MANPARTNO") "FSM4JH")
        (field (name "MANUFACTURER") "TE Connectivity")
      )
      (libsource (lib "eagle-import") (part "SWITCH-TACT-TH"))
    )
    (comp (ref "TX")
      (value "HEADERPIN")
      (footprint "eagle-import:HEADERPIN")
      (libsource (lib "eagle-import") (part "HEADERPIN"))
    )
    (comp (ref "U1")
      (value "74HC595")
      (footprint "eagle-import:SO16")
      (fields
        (field (name "DISTRIBUTORPARTNO") "296-14857-1-ND")
        (field (name "MANPARTNO") "SN74HC595DR")
        (field (name "MANUFACTURER") "Texas Instruments")
      )
      (libsource (lib "eagle-import") (part "74595-SOICHC"))
    )
    (comp (ref "U2")
      (value "74HC595")
      (footprint "eagle-import:SO16")
      (fields
        (field (name "DISTRIBUTORPARTNO") "296-14857-1-ND")
        (field (name "MANPARTNO") "SN74HC595DR")
        (field (name "MANUFACTURER") "Texas Instruments")
      )
      (libsource (lib "eagle-import") (part "74595-SOICHC"))
    )
    (comp (ref "U3")
      (value "74HC595")
      (footprint "eagle-import:SO16")
      (fields
        (field (name "DISTRIBUTORPARTNO") "296-14857-1-ND")
        (field (name "MANPARTNO") "SN74HC595DR")
        (field (name "MANUFACTURER") "Texas Instruments")
      )
      (libsource (lib "eagle-import") (part "74595-SOICHC"))
    )
    (comp (ref "U4")
      (value "74HC595")
      (footprint "eagle-import:SO16")
      (fields
        (field (name "DISTRIBUTORPARTNO") "296-14857-1-ND")
        (field (name "MANPARTNO") "SN74HC595DR")
        (field (name "MANUFACTURER") "Texas Instruments")
      )
      (libsource (lib "eagle-import") (part "74595-SOICHC"))
    )
    (comp (ref "U5")
      (value "74HC595")
      (footprint "eagle-import:SO16")
      (fields
        (field (name "DISTRIBUTORPARTNO") "296-14857-1-ND")
        (field (name "MANPARTNO") "SN74HC595DR")
        (field (name "MANUFACTURER") "Texas Instruments")
      )
      (libsource (lib "eagle-import") (part "74595-SOICHC"))
    )
    (comp (ref "U6")
      (value "74HC595")
      (footprint "eagle-import:SO16")
      (fields
        (field (name "DISTRIBUTORPARTNO") "296-14857-1-ND")
        (field (name "MANPARTNO") "SN74HC595DR")
        (field (name "MANUFACTURER") "Texas Instruments")
      )
      (libsource (lib "eagle-import") (part "74595-SOICHC"))
    )
    (comp (ref "U7")
      (value "74HC595")
      (footprint "eagle-import:SO16")
      (fields
        (field (name "DISTRIBUTORPARTNO") "296-14857-1-ND")
        (field (name "MANPARTNO") "SN74HC595DR")
        (field (name "MANUFACTURER") "Texas Instruments")
      )
      (libsource (lib "eagle-import") (part "74595-SOICHC"))
    )
    (comp (ref "U8")
      (value "74HC595")
      (footprint "eagle-import:SO16")
      (fields
        (field (name "DISTRIBUTORPARTNO") "296-14857-1-ND")
        (field (name "MANPARTNO") "SN74HC595DR")
        (field (name "MANUFACTURER") "Texas Instruments")
      )
      (libsource (lib "eagle-import") (part "74595-SOICHC"))
    )
    (comp (ref "U9")
      (value "74HC595")
      (footprint "eagle-import:SO16")
      (fields
        (field (name "DISTRIBUTORPARTNO") "296-14857-1-ND")
        (field (name "MANPARTNO") "SN74HC595DR")
        (field (name "MANUFACTURER") "Texas Instruments")
      )
      (libsource (lib "eagle-import") (part "74595-SOICHC"))
    )
    (comp (ref "U10")
      (value "ATMega48A")
      (footprint "eagle-import:TQFP-32")
      (fields
        (field (name "DISTRIBUTORPARTNO") "ATMEGA48V-10AU-ND")
        (field (name "MANPARTNO") "ATMEGA48V-10AU")
        (field (name "MANUFACTURER") "Atmel")
      )
      (libsource (lib "eagle-import") (part "ATMEGA48A"))
    )
    (comp (ref "U11")
      (value "74HC14")
      (footprint "eagle-import:SO14")
      (fields
        (field (name "DISTRIBUTORPARTNO") "296-9179-1-ND")
        (field (name "MANPARTNO") "CD74HC14M96")
        (field (name "MANUFACTURER") "Texas Instruments")
      )
      (libsource (lib "eagle-import") (part "7414-SOICHC"))
    )
    (comp (ref "U12")
      (value "74HC14")
      (footprint "eagle-import:SO14")
      (fields
        (field (name "DISTRIBUTORPARTNO") "296-9179-1-ND")
        (field (name "MANPARTNO") "CD74HC14M96")
        (field (name "MANUFACTURER") "Texas Instruments")
      )
      (libsource (lib "eagle-import") (part "7414-SOICHC"))
    )
    (comp (ref "U13")
      (value "74HC138")
      (footprint "eagle-import:SO16")
      (fields
        (field (name "DISTRIBUTORPARTNO") "MC74HC138ADGOS-ND")
        (field (name "MANPARTNO") "MC74HC138ADG")
        (field (name "MANUFACTURER") "ON Semiconductor")
      )
      (libsource (lib "eagle-import") (part "74138-SOICHC"))
    )
    (comp (ref "X1")
      (value "XTAL")
      (footprint "eagle-import:AB38T")
      (libsource (lib "eagle-import") (part "XTAL"))
    )
  )
  (nets
    (net (code "1") (name "+5V") (class "Default")
      (node (ref "C1") (pin "P1") (pinfunction "1_P1") (pintype "passive"))
      (node (ref "C10") (pin "P1") (pinfunction "1_P1") (pintype "passive"))
      (node (ref "C11") (pin "P1") (pinfunction "1_P1") (pintype "passive"))
      (node (ref "C12") (pin "P1") (pinfunction "1_P1") (pintype "passive"))
      (node (ref "C14") (pin "P1") (pinfunction "1_P1") (pintype "passive"))
      (node (ref "C15") (pin "P1") (pinfunction "1_P1") (pintype "passive"))
      (node (ref "C18") (pin "P1") (pinfunction "1_P1") (pintype "passive"))
      (node (ref "C19") (pin "P1") (pinfunction "1_P1") (pintype "passive"))
      (node (ref "C2") (pin "P1") (pinfunction "1_P1") (pintype "passive"))
      (node (ref "C3") (pin "P1") (pinfunction "1_P1") (pintype "passive"))
      (node (ref "C4") (pin "P1") (pinfunction "1_P1") (pintype "passive"))
      (node (ref "C5") (pin "P1") (pinfunction "1_P1") (pintype "passive"))
      (node (ref "C6") (pin "P1") (pinfunction "1_P1") (pintype "passive"))
      (node (ref "C7") (pin "P1") (pinfunction "1_P1") (pintype "passive"))
      (node (ref "C8") (pin "P1") (pinfunction "1_P1") (pintype "passive"))
      (node (ref "C9") (pin "P1") (pinfunction "1_P1") (pintype "passive"))
      (node (ref "J1") (pin "P2") (pinfunction "VCC_P2") (pintype "bidirectional"))
      (node (ref "J2") (pin "PIN") (pinfunction "PIN_PIN") (pintype "bidirectional"))
      (node (ref "R289") (pin "P2") (pinfunction "2_P2") (pintype "passive"))
      (node (ref "R33") (pin "P2") (pinfunction "2_P2") (pintype "passive"))
      (node (ref "U1") (pin "10") (pinfunction "SCL_10") (pintype "input"))
      (node (ref "U1") (pin "16") (pinfunction "VCC_16") (pintype "bidirectional"))
      (node (ref "U10") (pin "P18") (pinfunction "AVCC_P18") (pintype "bidirectional"))
      (node (ref "U10") (pin "P4") (pinfunction "VCC_P4") (pintype "bidirectional"))
      (node (ref "U10") (pin "P6") (pinfunction "VCC2_P6") (pintype "bidirectional"))
      (node (ref "U11") (pin "14") (pinfunction "VCC_14") (pintype "bidirectional"))
      (node (ref "U12") (pin "14") (pinfunction "VCC_14") (pintype "bidirectional"))
      (node (ref "U13") (pin "16") (pinfunction "VCC_16") (pintype "bidirectional"))
      (node (ref "U13") (pin "6") (pinfunction "G1_6") (pintype "input"))
      (node (ref "U2") (pin "10") (pinfunction "SCL_10") (pintype "input"))
      (node (ref "U2") (pin "16") (pinfunction "VCC_16") (pintype "bidirectional"))
      (node (ref "U3") (pin "10") (pinfunction "SCL_10") (pintype "input"))
      (node (ref "U3") (pin "16") (pinfunction "VCC_16") (pintype "bidirectional"))
      (node (ref "U4") (pin "10") (pinfunction "SCL_10") (pintype "input"))
      (node (ref "U4") (pin "16") (pinfunction "VCC_16") (pintype "bidirectional"))
      (node (ref "U5") (pin "10") (pinfunction "SCL_10") (pintype "input"))
      (node (ref "U5") (pin "16") (pinfunction "VCC_16") (pintype "bidirectional"))
      (node (ref "U6") (pin "10") (pinfunction "SCL_10") (pintype "input"))
      (node (ref "U6") (pin "16") (pinfunction "VCC_16") (pintype "bidirectional"))
      (node (ref "U7") (pin "10") (pinfunction "SCL_10") (pintype "input"))
      (node (ref "U7") (pin "16") (pinfunction "VCC_16") (pintype "bidirectional"))
      (node (ref "U8") (pin "10") (pinfunction "SCL_10") (pintype "input"))
      (node (ref "U8") (pin "16") (pinfunction "VCC_16") (pintype "bidirectional"))
      (node (ref "U9") (pin "10") (pinfunction "SCL_10") (pintype "input"))
      (node (ref "U9") (pin "16") (pinfunction "VCC_16") (pintype "bidirectional"))
    )
    (net (code "2") (name "/MISO") (class "Default")
      (node (ref "J1") (pin "P1") (pinfunction "MISO_P1") (pintype "bidirectional"))
      (node (ref "U10") (pin "P16") (pinfunction "(PCINT4/MISO)PB4_P16") (pintype "bidirectional"))
    )
    (net (code "3") (name "/MOSI") (class "Default")
      (node (ref "J1") (pin "P4") (pinfunction "MOSI_P4") (pintype "bidirectional"))
      (node (ref "U10") (pin "P15") (pinfunction "(PCINT3/OC2A/MOSI)PB3_P15") (pintype "bidirectional"))
    )
    (net (code "4") (name "/RCK") (class "Default")
      (node (ref "U1") (pin "12") (pinfunction "RCK_12") (pintype "input"))
      (node (ref "U10") (pin "P2") (pinfunction "PD4(PCINT20/XCK/T0)_P2") (pintype "bidirectional"))
      (node (ref "U2") (pin "12") (pinfunction "RCK_12") (pintype "input"))
      (node (ref "U3") (pin "12") (pinfunction "RCK_12") (pintype "input"))
      (node (ref "U4") (pin "12") (pinfunction "RCK_12") (pintype "input"))
      (node (ref "U5") (pin "12") (pinfunction "RCK_12") (pintype "input"))
      (node (ref "U6") (pin "12") (pinfunction "RCK_12") (pintype "input"))
      (node (ref "U7") (pin "12") (pinfunction "RCK_12") (pintype "input"))
      (node (ref "U8") (pin "12") (pinfunction "RCK_12") (pintype "input"))
      (node (ref "U9") (pin "12") (pinfunction "RCK_12") (pintype "input"))
    )
    (net (code "5") (name "/ROW0") (class "Default")
      (node (ref "D1") (pin "P22") (pinfunction "R1_P22") (pintype "bidirectional"))
      (node (ref "D2") (pin "P22") (pinfunction "R1_P22") (pintype "bidirectional"))
      (node (ref "D3") (pin "P22") (pinfunction "R1_P22") (pintype "bidirectional"))
      (node (ref "D4") (pin "P22") (pinfunction "R1_P22") (pintype "bidirectional"))
      (node (ref "D5") (pin "P22") (pinfunction "R1_P22") (pintype "bidirectional"))
      (node (ref "D6") (pin "P22") (pinfunction "R1_P22") (pintype "bidirectional"))
      (node (ref "D7") (pin "P22") (pinfunction "R1_P22") (pintype "bidirectional"))
      (node (ref "D8") (pin "P22") (pinfunction "R1_P22") (pintype "bidirectional"))
      (node (ref "D9") (pin "P22") (pinfunction "R1_P22") (pintype "bidirectional"))
      (node (ref "Q1") (pin "3") (pinfunction "D_3") (pintype "bidirectional"))
    )
    (net (code "6") (name "/ROW1") (class "Default")
      (node (ref "D1") (pin "P19") (pinfunction "R2_P19") (pintype "bidirectional"))
      (node (ref "D2") (pin "P19") (pinfunction "R2_P19") (pintype "bidirectional"))
      (node (ref "D3") (pin "P19") (pinfunction "R2_P19") (pintype "bidirectional"))
      (node (ref "D4") (pin "P19") (pinfunction "R2_P19") (pintype "bidirectional"))
      (node (ref "D5") (pin "P19") (pinfunction "R2_P19") (pintype "bidirectional"))
      (node (ref "D6") (pin "P19") (pinfunction "R2_P19") (pintype "bidirectional"))
      (node (ref "D7") (pin "P19") (pinfunction "R2_P19") (pintype "bidirectional"))
      (node (ref "D8") (pin "P19") (pinfunction "R2_P19") (pintype "bidirectional"))
      (node (ref "D9") (pin "P19") (pinfunction "R2_P19") (pintype "bidirectional"))
      (node (ref "Q2") (pin "3") (pinfunction "D_3") (pintype "bidirectional"))
    )
    (net (code "7") (name "/ROW2") (class "Default")
      (node (ref "D1") (pin "P16") (pinfunction "R3_P16") (pintype "bidirectional"))
      (node (ref "D2") (pin "P16") (pinfunction "R3_P16") (pintype "bidirectional"))
      (node (ref "D3") (pin "P16") (pinfunction "R3_P16") (pintype "bidirectional"))
      (node (ref "D4") (pin "P16") (pinfunction "R3_P16") (pintype "bidirectional"))
      (node (ref "D5") (pin "P16") (pinfunction "R3_P16") (pintype "bidirectional"))
      (node (ref "D6") (pin "P16") (pinfunction "R3_P16") (pintype "bidirectional"))
      (node (ref "D7") (pin "P16") (pinfunction "R3_P16") (pintype "bidirectional"))
      (node (ref "D8") (pin "P16") (pinfunction "R3_P16") (pintype "bidirectional"))
      (node (ref "D9") (pin "P16") (pinfunction "R3_P16") (pintype "bidirectional"))
      (node (ref "Q3") (pin "3") (pinfunction "D_3") (pintype "bidirectional"))
    )
    (net (code "8") (name "/ROW3") (class "Default")
      (node (ref "D1") (pin "P13") (pinfunction "R4_P13") (pintype "bidirectional"))
      (node (ref "D2") (pin "P13") (pinfunction "R4_P13") (pintype "bidirectional"))
      (node (ref "D3") (pin "P13") (pinfunction "R4_P13") (pintype "bidirectional"))
      (node (ref "D4") (pin "P13") (pinfunction "R4_P13") (pintype "bidirectional"))
      (node (ref "D5") (pin "P13") (pinfunction "R4_P13") (pintype "bidirectional"))
      (node (ref "D6") (pin "P13") (pinfunction "R4_P13") (pintype "bidirectional"))
      (node (ref "D7") (pin "P13") (pinfunction "R4_P13") (pintype "bidirectional"))
      (node (ref "D8") (pin "P13") (pinfunction "R4_P13") (pintype "bidirectional"))
      (node (ref "D9") (pin "P13") (pinfunction "R4_P13") (pintype "bidirectional"))
      (node (ref "Q4") (pin "3") (pinfunction "D_3") (pintype "bidirectional"))
    )
    (net (code "9") (name "/ROW4") (class "Default")
      (node (ref "D1") (pin "P3") (pinfunction "R5_P3") (pintype "bidirectional"))
      (node (ref "D2") (pin "P3") (pinfunction "R5_P3") (pintype "bidirectional"))
      (node (ref "D3") (pin "P3") (pinfunction "R5_P3") (pintype "bidirectional"))
      (node (ref "D4") (pin "P3") (pinfunction "R5_P3") (pintype "bidirectional"))
      (node (ref "D5") (pin "P3") (pinfunction "R5_P3") (pintype "bidirectional"))
      (node (ref "D6") (pin "P3") (pinfunction "R5_P3") (pintype "bidirectional"))
      (node (ref "D7") (pin "P3") (pinfunction "R5_P3") (pintype "bidirectional"))
      (node (ref "D8") (pin "P3") (pinfunction "R5_P3") (pintype "bidirectional"))
      (node (ref "D9") (pin "P3") (pinfunction "R5_P3") (pintype "bidirectional"))
      (node (ref "Q5") (pin "3") (pinfunction "D_3") (pintype "bidirectional"))
    )
    (net (code "10") (name "/ROW5") (class "Default")
      (node (ref "D1") (pin "P6") (pinfunction "R6_P6") (pintype "bidirectional"))
      (node (ref "D2") (pin "P6") (pinfunction "R6_P6") (pintype "bidirectional"))
      (node (ref "D3") (pin "P6") (pinfunction "R6_P6") (pintype "bidirectional"))
      (node (ref "D4") (pin "P6") (pinfunction "R6_P6") (pintype "bidirectional"))
      (node (ref "D5") (pin "P6") (pinfunction "R6_P6") (pintype "bidirectional"))
      (node (ref "D6") (pin "P6") (pinfunction "R6_P6") (pintype "bidirectional"))
      (node (ref "D7") (pin "P6") (pinfunction "R6_P6") (pintype "bidirectional"))
      (node (ref "D8") (pin "P6") (pinfunction "R6_P6") (pintype "bidirectional"))
      (node (ref "D9") (pin "P6") (pinfunction "R6_P6") (pintype "bidirectional"))
      (node (ref "Q6") (pin "3") (pinfunction "D_3") (pintype "bidirectional"))
    )
    (net (code "11") (name "/ROW6") (class "Default")
      (node (ref "D1") (pin "P9") (pinfunction "R7_P9") (pintype "bidirectional"))
      (node (ref "D2") (pin "P9") (pinfunction "R7_P9") (pintype "bidirectional"))
      (node (ref "D3") (pin "P9") (pinfunction "R7_P9") (pintype "bidirectional"))
      (node (ref "D4") (pin "P9") (pinfunction "R7_P9") (pintype "bidirectional"))
      (node (ref "D5") (pin "P9") (pinfunction "R7_P9") (pintype "bidirectional"))
      (node (ref "D6") (pin "P9") (pinfunction "R7_P9") (pintype "bidirectional"))
      (node (ref "D7") (pin "P9") (pinfunction "R7_P9") (pintype "bidirectional"))
      (node (ref "D8") (pin "P9") (pinfunction "R7_P9") (pintype "bidirectional"))
      (node (ref "D9") (pin "P9") (pinfunction "R7_P9") (pintype "bidirectional"))
      (node (ref "Q7") (pin "3") (pinfunction "D_3") (pintype "bidirectional"))
    )
    (net (code "12") (name "/ROW7") (class "Default")
      (node (ref "D1") (pin "P12") (pinfunction "R8_P12") (pintype "bidirectional"))
      (node (ref "D2") (pin "P12") (pinfunction "R8_P12") (pintype "bidirectional"))
      (node (ref "D3") (pin "P12") (pinfunction "R8_P12") (pintype "bidirectional"))
      (node (ref "D4") (pin "P12") (pinfunction "R8_P12") (pintype "bidirectional"))
      (node (ref "D5") (pin "P12") (pinfunction "R8_P12") (pintype "bidirectional"))
      (node (ref "D6") (pin "P12") (pinfunction "R8_P12") (pintype "bidirectional"))
      (node (ref "D7") (pin "P12") (pinfunction "R8_P12") (pintype "bidirectional"))
      (node (ref "D8") (pin "P12") (pinfunction "R8_P12") (pintype "bidirectional"))
      (node (ref "D9") (pin "P12") (pinfunction "R8_P12") (pintype "bidirectional"))
      (node (ref "Q8") (pin "3") (pinfunction "D_3") (pintype "bidirectional"))
    )
    (net (code "13") (name "/SCK") (class "Default")
      (node (ref "J1") (pin "P3") (pinfunction "SCK_P3") (pintype "bidirectional"))
      (node (ref "U1") (pin "11") (pinfunction "SCK_11") (pintype "input"))
      (node (ref "U10") (pin "P1") (pinfunction "PD3(PCINT19/OC2B/INT1)_P1") (pintype "bidirectional"))
      (node (ref "U10") (pin "P17") (pinfunction "(SCK/PCINT5)PB5_P17") (pintype "bidirectional"))
      (node (ref "U2") (pin "11") (pinfunction "SCK_11") (pintype "input"))
      (node (ref "U3") (pin "11") (pinfunction "SCK_11") (pintype "input"))
      (node (ref "U4") (pin "11") (pinfunction "SCK_11") (pintype "input"))
      (node (ref "U5") (pin "11") (pinfunction "SCK_11") (pintype "input"))
      (node (ref "U6") (pin "11") (pinfunction "SCK_11") (pintype "input"))
      (node (ref "U7") (pin "11") (pinfunction "SCK_11") (pintype "input"))
      (node (ref "U8") (pin "11") (pinfunction "SCK_11") (pintype "input"))
      (node (ref "U9") (pin "11") (pinfunction "SCK_11") (pintype "input"))
    )
    (net (code "14") (name "/SDATA1") (class "Default")
      (node (ref "U1") (pin "14") (pinfunction "SER_14") (pintype "input"))
      (node (ref "U10") (pin "P11") (pinfunction "PD7(PCINT23/AIN1)_P11") (pintype "bidirectional"))
    )
    (net (code "15") (name "/SDATA2") (class "Default")
      (node (ref "U10") (pin "P9") (pinfunction "PD5(PCINT21/OC0B/T1)_P9") (pintype "bidirectional"))
      (node (ref "U4") (pin "14") (pinfunction "SER_14") (pintype "input"))
    )
    (net (code "16") (name "/SDATA3") (class "Default")
      (node (ref "U10") (pin "P32") (pinfunction "PD2(INT0/PCINT18)_P32") (pintype "bidirectional"))
      (node (ref "U7") (pin "14") (pinfunction "SER_14") (pintype "input"))
    )
    (net (code "17") (name "/~{OE}") (class "Default")
      (node (ref "U1") (pin "13") (pinfunction "G_13") (pintype "input"))
      (node (ref "U10") (pin "P10") (pinfunction "PD6(PCINT22/OC0A/AIN0)_P10") (pintype "bidirectional"))
      (node (ref "U2") (pin "13") (pinfunction "G_13") (pintype "input"))
      (node (ref "U3") (pin "13") (pinfunction "G_13") (pintype "input"))
      (node (ref "U4") (pin "13") (pinfunction "G_13") (pintype "input"))
      (node (ref "U5") (pin "13") (pinfunction "G_13") (pintype "input"))
      (node (ref "U6") (pin "13") (pinfunction "G_13") (pintype "input"))
      (node (ref "U7") (pin "13") (pinfunction "G_13") (pintype "input"))
      (node (ref "U8") (pin "13") (pinfunction "G_13") (pintype "input"))
      (node (ref "U9") (pin "13") (pinfunction "G_13") (pintype "input"))
    )
    (net (code "18") (name "/~{RESET}") (class "Default")
      (node (ref "J1") (pin "P5") (pinfunction "~{RESET}_P5") (pintype "bidirectional"))
      (node (ref "R33") (pin "P1") (pinfunction "1_P1") (pintype "passive"))
      (node (ref "U10") (pin "P29") (pinfunction "PC6(RESET/PCINT14)_P29") (pintype "bidirectional"))
    )
    (net (code "19") (name "GND") (class "Default")
      (node (ref "C1") (pin "P2") (pinfunction "2_P2") (pintype "passive"))
      (node (ref "C10") (pin "P2") (pinfunction "2_P2") (pintype "passive"))
      (node (ref "C11") (pin "P2") (pinfunction "2_P2") (pintype "passive"))
      (node (ref "C12") (pin "P2") (pinfunction "2_P2") (pintype "passive"))
      (node (ref "C13") (pin "P2") (pinfunction "2_P2") (pintype "passive"))
      (node (ref "C14") (pin "P2") (pinfunction "2_P2") (pintype "passive"))
      (node (ref "C15") (pin "P2") (pinfunction "2_P2") (pintype "passive"))
      (node (ref "C16") (pin "P2") (pinfunction "2_P2") (pintype "passive"))
      (node (ref "C17") (pin "P2") (pinfunction "2_P2") (pintype "passive"))
      (node (ref "C18") (pin "P2") (pinfunction "2_P2") (pintype "passive"))
      (node (ref "C19") (pin "P2") (pinfunction "2_P2") (pintype "passive"))
      (node (ref "C2") (pin "P2") (pinfunction "2_P2") (pintype "passive"))
      (node (ref "C3") (pin "P2") (pinfunction "2_P2") (pintype "passive"))
      (node (ref "C4") (pin "P2") (pinfunction "2_P2") (pintype "passive"))
      (node (ref "C5") (pin "P2") (pinfunction "2_P2") (pintype "passive"))
      (node (ref "C6") (pin "P2") (pinfunction "2_P2") (pintype "passive"))
      (node (ref "C7") (pin "P2") (pinfunction "2_P2") (pintype "passive"))
      (node (ref "C8") (pin "P2") (pinfunction "2_P2") (pintype "passive"))
      (node (ref "C9") (pin "P2") (pinfunction "2_P2") (pintype "passive"))
      (node (ref "D10") (pin "K") (pinfunction "C_K") (pintype "passive"))
      (node (ref "GND") (pin "P$1") (pinfunction "P$1_P$1") (pintype "bidirectional"))
      (node (ref "J1") (pin "P6") (pinfunction "GND_P6") (pintype "bidirectional"))
      (node (ref "J2") (pin "BARREL") (pinfunction "BARREL_BARREL") (pintype "bidirectional"))
      (node (ref "Q1") (pin "2") (pinfunction "S_2") (pintype "bidirectional"))
      (node (ref "Q2") (pin "2") (pinfunction "S_2") (pintype "bidirectional"))
      (node (ref "Q3") (pin "2") (pinfunction "S_2") (pintype "bidirectional"))
      (node (ref "Q4") (pin "2") (pinfunction "S_2") (pintype "bidirectional"))
      (node (ref "Q5") (pin "2") (pinfunction "S_2") (pintype "bidirectional"))
      (node (ref "Q6") (pin "2") (pinfunction "S_2") (pintype "bidirectional"))
      (node (ref "Q7") (pin "2") (pinfunction "S_2") (pintype "bidirectional"))
      (node (ref "Q8") (pin "2") (pinfunction "S_2") (pintype "bidirectional"))
      (node (ref "SW1") (pin "P3") (pinfunction "P3_P3") (pintype "bidirectional"))
      (node (ref "SW1") (pin "P4") (pinfunction "P4_P4") (pintype "bidirectional"))
      (node (ref "SW2") (pin "P3") (pinfunction "P3_P3") (pintype "bidirectional"))
      (node (ref "SW2") (pin "P4") (pinfunction "P4_P4") (pintype "bidirectional"))
      (node (ref "U1") (pin "8") (pinfunction "GND_8") (pintype "bidirectional"))
      (node (ref "U10") (pin "P21") (pinfunction "GND3_P21") (pintype "bidirectional"))
      (node (ref "U10") (pin "P3") (pinfunction "GND_P3") (pintype "bidirectional"))
      (node (ref "U10") (pin "P5") (pinfunction "GND2_P5") (pintype "bidirectional"))
      (node (ref "U11") (pin "11") (pinfunction "I_11") (pintype "input"))
      (node (ref "U11") (pin "13") (pinfunction "I_13") (pintype "input"))
      (node (ref "U11") (pin "7") (pinfunction "GND_7") (pintype "bidirectional"))
      (node (ref "U12") (pin "11") (pinfunction "I_11") (pintype "input"))
      (node (ref "U12") (pin "13") (pinfunction "I_13") (pintype "input"))
      (node (ref "U12") (pin "7") (pinfunction "GND_7") (pintype "bidirectional"))
      (node (ref "U13") (pin "4") (pinfunction "G2A_4") (pintype "input"))
      (node (ref "U13") (pin "5") (pinfunction "G2B_5") (pintype "input"))
      (node (ref "U13") (pin "8") (pinfunction "GND_8") (pintype "bidirectional"))
      (node (ref "U2") (pin "8") (pinfunction "GND_8") (pintype "bidirectional"))
      (node (ref "U3") (pin "8") (pinfunction "GND_8") (pintype "bidirectional"))
      (node (ref "U4") (pin "8") (pinfunction "GND_8") (pintype "bidirectional"))
      (node (ref "U5") (pin "8") (pinfunction "GND_8") (pintype "bidirectional"))
      (node (ref "U6") (pin "8") (pinfunction "GND_8") (pintype "bidirectional"))
      (node (ref "U7") (pin "8") (pinfunction "GND_8") (pintype "bidirectional"))
      (node (ref "U8") (pin "8") (pinfunction "GND_8") (pintype "bidirectional"))
      (node (ref "U9") (pin "8") (pinfunction "GND_8") (pintype "bidirectional"))
    )
    (net (code "20") (name "Net-(C13-1)") (class "Default")
      (node (ref "C13") (pin "P1") (pinfunction "1_P1") (pintype "passive"))
      (node (ref "U10") (pin "P20") (pinfunction "AREF_P20") (pintype "bidirectional"))
    )
    (net (code "21") (name "Net-(C16-1)") (class "Default")
      (node (ref "C16") (pin "P1") (pinfunction "1_P1") (pintype "passive"))
      (node (ref "U10") (pin "P7") (pinfunction "(PCINT6/XTAL1/TOSC1)PB6_P7") (pintype "bidirectional"))
      (node (ref "X1") (pin "P$1") (pinfunction "1_P$1") (pintype "passive"))
    )
    (net (code "22") (name "Net-(C17-1)") (class "Default")
      (node (ref "C17") (pin "P1") (pinfunction "1_P1") (pintype "passive"))
      (node (ref "U10") (pin "P8") (pinfunction "(PCINT7/XTAL2/TOSC2)PB7_P8") (pintype "bidirectional"))
      (node (ref "X1") (pin "P$2") (pinfunction "2_P$2") (pintype "passive"))
    )
    (net (code "23") (name "Net-(D1-C1G)") (class "Default")
      (node (ref "D1") (pin "P24") (pinfunction "C1G_P24") (pintype "bidirectional"))
      (node (ref "R1") (pin "P1") (pinfunction "1_P1") (pintype "passive"))
    )
    (net (code "24") (name "Net-(D1-C1R)") (class "Default")
      (node (ref "D1") (pin "P23") (pinfunction "C1R_P23") (pintype "bidirectional"))
      (node (ref "R2") (pin "P1") (pinfunction "1_P1") (pintype "passive"))
    )
    (net (code "25") (name "Net-(D1-C2G)") (class "Default")
      (node (ref "D1") (pin "P21") (pinfunction "C2G_P21") (pintype "bidirectional"))
      (node (ref "R3") (pin "P1") (pinfunction "1_P1") (pintype "passive"))
    )
    (net (code "26") (name "Net-(D1-C2R)") (class "Default")
      (node (ref "D1") (pin "P20") (pinfunction "C2R_P20") (pintype "bidirectional"))
      (node (ref "R4") (pin "P1") (pinfunction "1_P1") (pintype "passive"))
    )
    (net (code "27") (name "Net-(D1-C3G)") (class "Default")
      (node (ref "D1") (pin "P18") (pinfunction "C3G_P18") (pintype "bidirectional"))
      (node (ref "R5") (pin "P1") (pinfunction "1_P1") (pintype "passive"))
    )
    (net (code "28") (name "Net-(D1-C3R)") (class "Default")
      (node (ref "D1") (pin "P17") (pinfunction "C3R_P17") (pintype "bidirectional"))
      (node (ref "R6") (pin "P1") (pinfunction "1_P1") (pintype "passive"))
    )
    (net (code "29") (name "Net-(D1-C4G)") (class "Default")
      (node (ref "D1") (pin "P15") (pinfunction "C4G_P15") (pintype "bidirectional"))
      (node (ref "R7") (pin "P1") (pinfunction "1_P1") (pintype "passive"))
    )
    (net (code "30") (name "Net-(D1-C4R)") (class "Default")
      (node (ref "D1") (pin "P14") (pinfunction "C4R_P14") (pintype "bidirectional"))
      (node (ref "R8") (pin "P1") (pinfunction "1_P1") (pintype "passive"))
    )
    (net (code "31") (name "Net-(D1-C5G)") (class "Default")
      (node (ref "D1") (pin "P1") (pinfunction "C5G_P1") (pintype "bidirectional"))
      (node (ref "R9") (pin "P1") (pinfunction "1_P1") (pintype "passive"))
    )
    (net (code "32") (name "Net-(D1-C5R)") (class "Default")
      (node (ref "D1") (pin "P2") (pinfunction "C5R_P2") (pintype "bidirectional"))
      (node (ref "R10") (pin "P1") (pinfunction "1_P1") (pintype "passive"))
    )
    (net (code "33") (name "Net-(D1-C6G)") (class "Default")
      (node (ref "D1") (pin "P4") (pinfunction "C6G_P4") (pintype "bidirectional"))
      (node (ref "R11") (pin "P1") (pinfunction "1_P1") (pintype "passive"))
    )
    (net (code "34") (name "Net-(D1-C6R)") (class "Default")
      (node (ref "D1") (pin "P5") (pinfunction "C6R_P5") (pintype "bidirectional"))
      (node (ref "R12") (pin "P1") (pinfunction "1_P1") (pintype "passive"))
    )
    (net (code "35") (name "Net-(D1-C7G)") (class "Default")
      (node (ref "D1") (pin "P7") (pinfunction "C7G_P7") (pintype "bidirectional"))
      (node (ref "R13") (pin "P1") (pinfunction "1_P1") (pintype "passive"))
    )
    (net (code "36") (name "Net-(D1-C7R)") (class "Default")
      (node (ref "D1") (pin "P8") (pinfunction "C7R_P8") (pintype "bidirectional"))
      (node (ref "R14") (pin "P1") (pinfunction "1_P1") (pintype "passive"))
    )
    (net (code "37") (name "Net-(D1-C8G)") (class "Default")
      (node (ref "D1") (pin "P10") (pinfunction "C8G_P10") (pintype "bidirectional"))
      (node (ref "R15") (pin "P1") (pinfunction "1_P1") (pintype "passive"))
    )
    (net (code "38") (name "Net-(D1-C8R)") (class "Default")
      (node (ref "D1") (pin "P11") (pinfunction "C8R_P11") (pintype "bidirectional"))
      (node (ref "R16") (pin "P1") (pinfunction "1_P1") (pintype "passive"))
    )
    (net (code "39") (name "Net-(D2-C1G)") (class "Default")
      (node (ref "D2") (pin "P24") (pinfunction "C1G_P24") (pintype "bidirectional"))
      (node (ref "R17") (pin "P1") (pinfunction "1_P1") (pintype "passive"))
    )
    (net (code "40") (name "Net-(D2-C1R)") (class "Default")
      (node (ref "D2") (pin "P23") (pinfunction "C1R_P23") (pintype "bidirectional"))
      (node (ref "R18") (pin "P1") (pinfunction "1_P1") (pintype "passive"))
    )
    (net (code "41") (name "Net-(D2-C2G)") (class "Default")
      (node (ref "D2") (pin "P21") (pinfunction "C2G_P21") (pintype "bidirectional"))
      (node (ref "R19") (pin "P1") (pinfunction "1_P1") (pintype "passive"))
    )
    (net (code "42") (name "Net-(D2-C2R)") (class "Default")
      (node (ref "D2") (pin "P20") (pinfunction "C2R_P20") (pintype "bidirectional"))
      (node (ref "R20") (pin "P1") (pinfunction "1_P1") (pintype "passive"))
    )
    (net (code "43") (name "Net-(D2-C3G)") (class "Default")
      (node (ref "D2") (pin "P18") (pinfunction "C3G_P18") (pintype "bidirectional"))
      (node (ref "R21") (pin "P1") (pinfunction "1_P1") (pintype "passive"))
    )
    (net (code "44") (name "Net-(D2-C3R)") (class "Default")
      (node (ref "D2") (pin "P17") (pinfunction "C3R_P17") (pintype "bidirectional"))
      (node (ref "R22") (pin "P1") (pinfunction "1_P1") (pintype "passive"))
    )
    (net (code "45") (name "Net-(D2-C4G)") (class "Default")
      (node (ref "D2") (pin "P15") (pinfunction "C4G_P15") (pintype "bidirectional"))
      (node (ref "R23") (pin "P1") (pinfunction "1_P1") (pintype "passive"))
    )
    (net (code "46") (name "Net-(D2-C4R)") (class "Default")
      (node (ref "D2") (pin "P14") (pinfunction "C4R_P14") (pintype "bidirectional"))
      (node (ref "R24") (pin "P1") (pinfunction "1_P1") (pintype "passive"))
    )
    (net (code "47") (name "Net-(D2-C5G)") (class "Default")
      (node (ref "D2") (pin "P1") (pinfunction "C5G_P1") (pintype "bidirectional"))
      (node (ref "R25") (pin "P1") (pinfunction "1_P1") (pintype "passive"))
    )
    (net (code "48") (name "Net-(D2-C5R)") (class "Default")
      (node (ref "D2") (pin "P2") (pinfunction "C5R_P2") (pintype "bidirectional"))
      (node (ref "R26") (pin "P1") (pinfunction "1_P1") (pintype "passive"))
    )
    (net (code "49") (name "Net-(D2-C6G)") (class "Default")
      (node (ref "D2") (pin "P4") (pinfunction "C6G_P4") (pintype "bidirectional"))
      (node (ref "R27") (pin "P1") (pinfunction "1_P1") (pintype "passive"))
    )
    (net (code "50") (name "Net-(D2-C6R)") (class "Default")
      (node (ref "D2") (pin "P5") (pinfunction "C6R_P5") (pintype "bidirectional"))
      (node (ref "R28") (pin "P1") (pinfunction "1_P1") (pintype "passive"))
    )
    (net (code "51") (name "Net-(D2-C7G)") (class "Default")
      (node (ref "D2") (pin "P7") (pinfunction "C7G_P7") (pintype "bidirectional"))
      (node (ref "R29") (pin "P1") (pinfunction "1_P1") (pintype "passive"))
    )
    (net (code "52") (name "Net-(D2-C7R)") (class "Default")
      (node (ref "D2") (pin "P8") (pinfunction "C7R_P8") (pintype "bidirectional"))
      (node (ref "R30") (pin "P1") (pinfunction "1_P1") (pintype "passive"))
    )
    (net (code "53") (name "Net-(D2-C8G)") (class "Default")
      (node (ref "D2") (pin "P10") (pinfunction "C8G_P10") (pintype "bidirectional"))
      (node (ref "R31") (pin "P1") (pinfunction "1_P1") (pintype "passive"))
    )
    (net (code "54") (name "Net-(D2-C8R)") (class "Default")
      (node (ref "D2") (pin "P11") (pinfunction "C8R_P11") (pintype "bidirectional"))
      (node (ref "R32") (pin "P1") (pinfunction "1_P1") (pintype "passive"))
    )
    (net (code "55") (name "Net-(D3-C1G)") (class "Default")
      (node (ref "D3") (pin "P24") (pinfunction "C1G_P24") (pintype "bidirectional"))
      (node (ref "R65") (pin "P1") (pinfunction "1_P1") (pintype "passive"))
    )
    (net (code "56") (name "Net-(D3-C1R)") (class "Default")
      (node (ref "D3") (pin "P23") (pinfunction "C1R_P23") (pintype "bidirectional"))
      (node (ref "R66") (pin "P1") (pinfunction "1_P1") (pintype "passive"))
    )
    (net (code "57") (name "Net-(D3-C2G)") (class "Default")
      (node (ref "D3") (pin "P21") (pinfunction "C2G_P21") (pintype "bidirectional"))
      (node (ref "R67") (pin "P1") (pinfunction "1_P1") (pintype "passive"))
    )
    (net (code "58") (name "Net-(D3-C2R)") (class "Default")
      (node (ref "D3") (pin "P20") (pinfunction "C2R_P20") (pintype "bidirectional"))
      (node (ref "R68") (pin "P1") (pinfunction "1_P1") (pintype "passive"))
    )
    (net (code "59") (name "Net-(D3-C3G)") (class "Default")
      (node (ref "D3") (pin "P18") (pinfunction "C3G_P18") (pintype "bidirectional"))
      (node (ref "R69") (pin "P1") (pinfunction "1_P1") (pintype "passive"))
    )
    (net (code "60") (name "Net-(D3-C3R)") (class "Default")
      (node (ref "D3") (pin "P17") (pinfunction "C3R_P17") (pintype "bidirectional"))
      (node (ref "R70") (pin "P1") (pinfunction "1_P1") (pintype "passive"))
    )
    (net (code "61") (name "Net-(D3-C4G)") (class "Default")
      (node (ref "D3") (pin "P15") (pinfunction "C4G_P15") (pintype "bidirectional"))
      (node (ref "R71") (pin "P1") (pinfunction "1_P1") (pintype "passive"))
    )
    (net (code "62") (name "Net-(D3-C4R)") (class "Default")
      (node (ref "D3") (pin "P14") (pinfunction "C4R_P14") (pintype "bidirectional"))
      (node (ref "R72") (pin "P1") (pinfunction "1_P1") (pintype "passive"))
    )
    (net (code "63") (name "Net-(D3-C5G)") (class "Default")
      (node (ref "D3") (pin "P1") (pinfunction "C5G_P1") (pintype "bidirectional"))
      (node (ref "R73") (pin "P1") (pinfunction "1_P1") (pintype "passive"))
    )
    (net (code "64") (name "Net-(D3-C5R)") (class "Default")
      (node (ref "D3") (pin "P2") (pinfunction "C5R_P2") (pintype "bidirectional"))
      (node (ref "R74") (pin "P1") (pinfunction "1_P1") (pintype "passive"))
    )
    (net (code "65") (name "Net-(D3-C6G)") (class "Default")
      (node (ref "D3") (pin "P4") (pinfunction "C6G_P4") (pintype "bidirectional"))
      (node (ref "R75") (pin "P1") (pinfunction "1_P1") (pintype "passive"))
    )
    (net (code "66") (name "Net-(D3-C6R)") (class "Default")
      (node (ref "D3") (pin "P5") (pinfunction "C6R_P5") (pintype "bidirectional"))
      (node (ref "R76") (pin "P1") (pinfunction "1_P1") (pintype "passive"))
    )
    (net (code "67") (name "Net-(D3-C7G)") (class "Default")
      (node (ref "D3") (pin "P7") (pinfunction "C7G_P7") (pintype "bidirectional"))
      (node (ref "R77") (pin "P1") (pinfunction "1_P1") (pintype "passive"))
    )
    (net (code "68") (name "Net-(D3-C7R)") (class "Default")
      (node (ref "D3") (pin "P8") (pinfunction "C7R_P8") (pintype "bidirectional"))
      (node (ref "R78") (pin "P1") (pinfunction "1_P1") (pintype "passive"))
    )
    (net (code "69") (name "Net-(D3-C8G)") (class "Default")
      (node (ref "D3") (pin "P10") (pinfunction "C8G_P10") (pintype "bidirectional"))
      (node (ref "R79") (pin "P1") (pinfunction "1_P1") (pintype "passive"))
    )
    (net (code "70") (name "Net-(D3-C8R)") (class "Default")
      (node (ref "D3") (pin "P11") (pinfunction "C8R_P11") (pintype "bidirectional"))
      (node (ref "R80") (pin "P1") (pinfunction "1_P1") (pintype "passive"))
    )
    (net (code "71") (name "Net-(D4-C1G)") (class "Default")
      (node (ref "D4") (pin "P24") (pinfunction "C1G_P24") (pintype "bidirectional"))
      (node (ref "R97") (pin "P1") (pinfunction "1_P1") (pintype "passive"))
    )
    (net (code "72") (name "Net-(D4-C1R)") (class "Default")
      (node (ref "D4") (pin "P23") (pinfunction "C1R_P23") (pintype "bidirectional"))
      (node (ref "R98") (pin "P1") (pinfunction "1_P1") (pintype "passive"))
    )
    (net (code "73") (name "Net-(D4-C2G)") (class "Default")
      (node (ref "D4") (pin "P21") (pinfunction "C2G_P21") (pintype "bidirectional"))
      (node (ref "R99") (pin "P1") (pinfunction "1_P1") (pintype "passive"))
    )
    (net (code "74") (name "Net-(D4-C2R)") (class "Default")
      (node (ref "D4") (pin "P20") (pinfunction "C2R_P20") (pintype "bidirectional"))
      (node (ref "R100") (pin "P1") (pinfunction "1_P1") (pintype "passive"))
    )
    (net (code "75") (name "Net-(D4-C3G)") (class "Default")
      (node (ref "D4") (pin "P18") (pinfunction "C3G_P18") (pintype "bidirectional"))
      (node (ref "R101") (pin "P1") (pinfunction "1_P1") (pintype "passive"))
    )
    (net (code "76") (name "Net-(D4-C3R)") (class "Default")
      (node (ref "D4") (pin "P17") (pinfunction "C3R_P17") (pintype "bidirectional"))
      (node (ref "R102") (pin "P1") (pinfunction "1_P1") (pintype "passive"))
    )
    (net (code "77") (name "Net-(D4-C4G)") (class "Default")
      (node (ref "D4") (pin "P15") (pinfunction "C4G_P15") (pintype "bidirectional"))
      (node (ref "R103") (pin "P1") (pinfunction "1_P1") (pintype "passive"))
    )
    (net (code "78") (name "Net-(D4-C4R)") (class "Default")
      (node (ref "D4") (pin "P14") (pinfunction "C4R_P14") (pintype "bidirectional"))
      (node (ref "R104") (pin "P1") (pinfunction "1_P1") (pintype "passive"))
    )
    (net (code "79") (name "Net-(D4-C5G)") (class "Default")
      (node (ref "D4") (pin "P1") (pinfunction "C5G_P1") (pintype "bidirectional"))
      (node (ref "R105") (pin "P1") (pinfunction "1_P1") (pintype "passive"))
    )
    (net (code "80") (name "Net-(D4-C5R)") (class "Default")
      (node (ref "D4") (pin "P2") (pinfunction "C5R_P2") (pintype "bidirectional"))
      (node (ref "R106") (pin "P1") (pinfunction "1_P1") (pintype "passive"))
    )
    (net (code "81") (name "Net-(D4-C6G)") (class "Default")
      (node (ref "D4") (pin "P4") (pinfunction "C6G_P4") (pintype "bidirectional"))
      (node (ref "R107") (pin "P1") (pinfunction "1_P1") (pintype "passive"))
    )
    (net (code "82") (name "Net-(D4-C6R)") (class "Default")
      (node (ref "D4") (pin "P5") (pinfunction "C6R_P5") (pintype "bidirectional"))
      (node (ref "R108") (pin "P1") (pinfunction "1_P1") (pintype "passive"))
    )
    (net (code "83") (name "Net-(D4-C7G)") (class "Default")
      (node (ref "D4") (pin "P7") (pinfunction "C7G_P7") (pintype "bidirectional"))
      (node (ref "R109") (pin "P1") (pinfunction "1_P1") (pintype "passive"))
    )
    (net (code "84") (name "Net-(D4-C7R)") (class "Default")
      (node (ref "D4") (pin "P8") (pinfunction "C7R_P8") (pintype "bidirectional"))
      (node (ref "R110") (pin "P1") (pinfunction "1_P1") (pintype "passive"))
    )
    (net (code "85") (name "Net-(D4-C8G)") (class "Default")
      (node (ref "D4") (pin "P10") (pinfunction "C8G_P10") (pintype "bidirectional"))
      (node (ref "R111") (pin "P1") (pinfunction "1_P1") (pintype "passive"))
    )
    (net (code "86") (name "Net-(D4-C8R)") (class "Default")
      (node (ref "D4") (pin "P11") (pinfunction "C8R_P11") (pintype "bidirectional"))
      (node (ref "R112") (pin "P1") (pinfunction "1_P1") (pintype "passive"))
    )
    (net (code "87") (name "Net-(D5-C1G)") (class "Default")
      (node (ref "D5") (pin "P24") (pinfunction "C1G_P24") (pintype "bidirectional"))
      (node (ref "R129") (pin "P1") (pinfunction "1_P1") (pintype "passive"))
    )
    (net (code "88") (name "Net-(D5-C1R)") (class "Default")
      (node (ref "D5") (pin "P23") (pinfunction "C1R_P23") (pintype "bidirectional"))
      (node (ref "R130") (pin "P1") (pinfunction "1_P1") (pintype "passive"))
    )
    (net (code "89") (name "Net-(D5-C2G)") (class "Default")
      (node (ref "D5") (pin "P21") (pinfunction "C2G_P21") (pintype "bidirectional"))
      (node (ref "R131") (pin "P1") (pinfunction "1_P1") (pintype "passive"))
    )
    (net (code "90") (name "Net-(D5-C2R)") (class "Default")
      (node (ref "D5") (pin "P20") (pinfunction "C2R_P20") (pintype "bidirectional"))
      (node (ref "R132") (pin "P1") (pinfunction "1_P1") (pintype "passive"))
    )
    (net (code "91") (name "Net-(D5-C3G)") (class "Default")
      (node (ref "D5") (pin "P18") (pinfunction "C3G_P18") (pintype "bidirectional"))
      (node (ref "R133") (pin "P1") (pinfunction "1_P1") (pintype "passive"))
    )
    (net (code "92") (name "Net-(D5-C3R)") (class "Default")
      (node (ref "D5") (pin "P17") (pinfunction "C3R_P17") (pintype "bidirectional"))
      (node (ref "R134") (pin "P1") (pinfunction "1_P1") (pintype "passive"))
    )
    (net (code "93") (name "Net-(D5-C4G)") (class "Default")
      (node (ref "D5") (pin "P15") (pinfunction "C4G_P15") (pintype "bidirectional"))
      (node (ref "R135") (pin "P1") (pinfunction "1_P1") (pintype "passive"))
    )
    (net (code "94") (name "Net-(D5-C4R)") (class "Default")
      (node (ref "D5") (pin "P14") (pinfunction "C4R_P14") (pintype "bidirectional"))
      (node (ref "R136") (pin "P1") (pinfunction "1_P1") (pintype "passive"))
    )
    (net (code "95") (name "Net-(D5-C5G)") (class "Default")
      (node (ref "D5") (pin "P1") (pinfunction "C5G_P1") (pintype "bidirectional"))
      (node (ref "R137") (pin "P1") (pinfunction "1_P1") (pintype "passive"))
    )
    (net (code "96") (name "Net-(D5-C5R)") (class "Default")
      (node (ref "D5") (pin "P2") (pinfunction "C5R_P2") (pintype "bidirectional"))
      (node (ref "R138") (pin "P1") (pinfunction "1_P1") (pintype "passive"))
    )
    (net (code "97") (name "Net-(D5-C6G)") (class "Default")
      (node (ref "D5") (pin "P4") (pinfunction "C6G_P4") (pintype "bidirectional"))
      (node (ref "R139") (pin "P1") (pinfunction "1_P1") (pintype "passive"))
    )
    (net (code "98") (name "Net-(D5-C6R)") (class "Default")
      (node (ref "D5") (pin "P5") (pinfunction "C6R_P5") (pintype "bidirectional"))
      (node (ref "R140") (pin "P1") (pinfunction "1_P1") (pintype "passive"))
    )
    (net (code "99") (name "Net-(D5-C7G)") (class "Default")
      (node (ref "D5") (pin "P7") (pinfunction "C7G_P7") (pintype "bidirectional"))
      (node (ref "R141") (pin "P1") (pinfunction "1_P1") (pintype "passive"))
    )
    (net (code "100") (name "Net-(D5-C7R)") (class "Default")
      (node (ref "D5") (pin "P8") (pinfunction "C7R_P8") (pintype "bidirectional"))
      (node (ref "R142") (pin "P1") (pinfunction "1_P1") (pintype "passive"))
    )
    (net (code "101") (name "Net-(D5-C8G)") (class "Default")
      (node (ref "D5") (pin "P10") (pinfunction "C8G_P10") (pintype "bidirectional"))
      (node (ref "R143") (pin "P1") (pinfunction "1_P1") (pintype "passive"))
    )
    (net (code "102") (name "Net-(D5-C8R)") (class "Default")
      (node (ref "D5") (pin "P11") (pinfunction "C8R_P11") (pintype "bidirectional"))
      (node (ref "R144") (pin "P1") (pinfunction "1_P1") (pintype "passive"))
    )
    (net (code "103") (name "Net-(D6-C1G)") (class "Default")
      (node (ref "D6") (pin "P24") (pinfunction "C1G_P24") (pintype "bidirectional"))
      (node (ref "R161") (pin "P1") (pinfunction "1_P1") (pintype "passive"))
    )
    (net (code "104") (name "Net-(D6-C1R)") (class "Default")
      (node (ref "D6") (pin "P23") (pinfunction "C1R_P23") (pintype "bidirectional"))
      (node (ref "R162") (pin "P1") (pinfunction "1_P1") (pintype "passive"))
    )
    (net (code "105") (name "Net-(D6-C2G)") (class "Default")
      (node (ref "D6") (pin "P21") (pinfunction "C2G_P21") (pintype "bidirectional"))
      (node (ref "R163") (pin "P1") (pinfunction "1_P1") (pintype "passive"))
    )
    (net (code "106") (name "Net-(D6-C2R)") (class "Default")
      (node (ref "D6") (pin "P20") (pinfunction "C2R_P20") (pintype "bidirectional"))
      (node (ref "R164") (pin "P1") (pinfunction "1_P1") (pintype "passive"))
    )
    (net (code "107") (name "Net-(D6-C3G)") (class "Default")
      (node (ref "D6") (pin "P18") (pinfunction "C3G_P18") (pintype "bidirectional"))
      (node (ref "R165") (pin "P1") (pinfunction "1_P1") (pintype "passive"))
    )
    (net (code "108") (name "Net-(D6-C3R)") (class "Default")
      (node (ref "D6") (pin "P17") (pinfunction "C3R_P17") (pintype "bidirectional"))
      (node (ref "R166") (pin "P1") (pinfunction "1_P1") (pintype "passive"))
    )
    (net (code "109") (name "Net-(D6-C4G)") (class "Default")
      (node (ref "D6") (pin "P15") (pinfunction "C4G_P15") (pintype "bidirectional"))
      (node (ref "R167") (pin "P1") (pinfunction "1_P1") (pintype "passive"))
    )
    (net (code "110") (name "Net-(D6-C4R)") (class "Default")
      (node (ref "D6") (pin "P14") (pinfunction "C4R_P14") (pintype "bidirectional"))
      (node (ref "R168") (pin "P1") (pinfunction "1_P1") (pintype "passive"))
    )
    (net (code "111") (name "Net-(D6-C5G)") (class "Default")
      (node (ref "D6") (pin "P1") (pinfunction "C5G_P1") (pintype "bidirectional"))
      (node (ref "R169") (pin "P1") (pinfunction "1_P1") (pintype "passive"))
    )
    (net (code "112") (name "Net-(D6-C5R)") (class "Default")
      (node (ref "D6") (pin "P2") (pinfunction "C5R_P2") (pintype "bidirectional"))
      (node (ref "R170") (pin "P1") (pinfunction "1_P1") (pintype "passive"))
    )
    (net (code "113") (name "Net-(D6-C6G)") (class "Default")
      (node (ref "D6") (pin "P4") (pinfunction "C6G_P4") (pintype "bidirectional"))
      (node (ref "R171") (pin "P1") (pinfunction "1_P1") (pintype "passive"))
    )
    (net (code "114") (name "Net-(D6-C6R)") (class "Default")
      (node (ref "D6") (pin "P5") (pinfunction "C6R_P5") (pintype "bidirectional"))
      (node (ref "R172") (pin "P1") (pinfunction "1_P1") (pintype "passive"))
    )
    (net (code "115") (name "Net-(D6-C7G)") (class "Default")
      (node (ref "D6") (pin "P7") (pinfunction "C7G_P7") (pintype "bidirectional"))
      (node (ref "R173") (pin "P1") (pinfunction "1_P1") (pintype "passive"))
    )
    (net (code "116") (name "Net-(D6-C7R)") (class "Default")
      (node (ref "D6") (pin "P8") (pinfunction "C7R_P8") (pintype "bidirectional"))
      (node (ref "R174") (pin "P1") (pinfunction "1_P1") (pintype "passive"))
    )
    (net (code "117") (name "Net-(D6-C8G)") (class "Default")
      (node (ref "D6") (pin "P10") (pinfunction "C8G_P10") (pintype "bidirectional"))
      (node (ref "R175") (pin "P1") (pinfunction "1_P1") (pintype "passive"))
    )
    (net (code "118") (name "Net-(D6-C8R)") (class "Default")
      (node (ref "D6") (pin "P11") (pinfunction "C8R_P11") (pintype "bidirectional"))
      (node (ref "R176") (pin "P1") (pinfunction "1_P1") (pintype "passive"))
    )
    (net (code "119") (name "Net-(D7-C1G)") (class "Default")
      (node (ref "D7") (pin "P24") (pinfunction "C1G_P24") (pintype "bidirectional"))
      (node (ref "R193") (pin "P1") (pinfunction "1_P1") (pintype "passive"))
    )
    (net (code "120") (name "Net-(D7-C1R)") (class "Default")
      (node (ref "D7") (pin "P23") (pinfunction "C1R_P23") (pintype "bidirectional"))
      (node (ref "R194") (pin "P1") (pinfunction "1_P1") (pintype "passive"))
    )
    (net (code "121") (name "Net-(D7-C2G)") (class "Default")
      (node (ref "D7") (pin "P21") (pinfunction "C2G_P21") (pintype "bidirectional"))
      (node (ref "R195") (pin "P1") (pinfunction "1_P1") (pintype "passive"))
    )
    (net (code "122") (name "Net-(D7-C2R)") (class "Default")
      (node (ref "D7") (pin "P20") (pinfunction "C2R_P20") (pintype "bidirectional"))
      (node (ref "R196") (pin "P1") (pinfunction "1_P1") (pintype "passive"))
    )
    (net (code "123") (name "Net-(D7-C3G)") (class "Default")
      (node (ref "D7") (pin "P18") (pinfunction "C3G_P18") (pintype "bidirectional"))
      (node (ref "R197") (pin "P1") (pinfunction "1_P1") (pintype "passive"))
    )
    (net (code "124") (name "Net-(D7-C3R)") (class "Default")
      (node (ref "D7") (pin "P17") (pinfunction "C3R_P17") (pintype "bidirectional"))
      (node (ref "R198") (pin "P1") (pinfunction "1_P1") (pintype "passive"))
    )
    (net (code "125") (name "Net-(D7-C4G)") (class "Default")
      (node (ref "D7") (pin "P15") (pinfunction "C4G_P15") (pintype "bidirectional"))
      (node (ref "R199") (pin "P1") (pinfunction "1_P1") (pintype "passive"))
    )
    (net (code "126") (name "Net-(D7-C4R)") (class "Default")
      (node (ref "D7") (pin "P14") (pinfunction "C4R_P14") (pintype "bidirectional"))
      (node (ref "R200") (pin "P1") (pinfunction "1_P1") (pintype "passive"))
    )
    (net (code "127") (name "Net-(D7-C5G)") (class "Default")
      (node (ref "D7") (pin "P1") (pinfunction "C5G_P1") (pintype "bidirectional"))
      (node (ref "R201") (pin "P1") (pinfunction "1_P1") (pintype "passive"))
    )
    (net (code "128") (name "Net-(D7-C5R)") (class "Default")
      (node (ref "D7") (pin "P2") (pinfunction "C5R_P2") (pintype "bidirectional"))
      (node (ref "R202") (pin "P1") (pinfunction "1_P1") (pintype "passive"))
    )
    (net (code "129") (name "Net-(D7-C6G)") (class "Default")
      (node (ref "D7") (pin "P4") (pinfunction "C6G_P4") (pintype "bidirectional"))
      (node (ref "R203") (pin "P1") (pinfunction "1_P1") (pintype "passive"))
    )
    (net (code "130") (name "Net-(D7-C6R)") (class "Default")
      (node (ref "D7") (pin "P5") (pinfunction "C6R_P5") (pintype "bidirectional"))
      (node (ref "R204") (pin "P1") (pinfunction "1_P1") (pintype "passive"))
    )
    (net (code "131") (name "Net-(D7-C7G)") (class "Default")
      (node (ref "D7") (pin "P7") (pinfunction "C7G_P7") (pintype "bidirectional"))
      (node (ref "R205") (pin "P1") (pinfunction "1_P1") (pintype "passive"))
    )
    (net (code "132") (name "Net-(D7-C7R)") (class "Default")
      (node (ref "D7") (pin "P8") (pinfunction "C7R_P8") (pintype "bidirectional"))
      (node (ref "R206") (pin "P1") (pinfunction "1_P1") (pintype "passive"))
    )
    (net (code "133") (name "Net-(D7-C8G)") (class "Default")
      (node (ref "D7") (pin "P10") (pinfunction "C8G_P10") (pintype "bidirectional"))
      (node (ref "R207") (pin "P1") (pinfunction "1_P1") (pintype "passive"))
    )
    (net (code "134") (name "Net-(D7-C8R)") (class "Default")
      (node (ref "D7") (pin "P11") (pinfunction "C8R_P11") (pintype "bidirectional"))
      (node (ref "R208") (pin "P1") (pinfunction "1_P1") (pintype "passive"))
    )
    (net (code "135") (name "Net-(D8-C1G)") (class "Default")
      (node (ref "D8") (pin "P24") (pinfunction "C1G_P24") (pintype "bidirectional"))
      (node (ref "R225") (pin "P1") (pinfunction "1_P1") (pintype "passive"))
    )
    (net (code "136") (name "Net-(D8-C1R)") (class "Default")
      (node (ref "D8") (pin "P23") (pinfunction "C1R_P23") (pintype "bidirectional"))
      (node (ref "R226") (pin "P1") (pinfunction "1_P1") (pintype "passive"))
    )
    (net (code "137") (name "Net-(D8-C2G)") (class "Default")
      (node (ref "D8") (pin "P21") (pinfunction "C2G_P21") (pintype "bidirectional"))
      (node (ref "R227") (pin "P1") (pinfunction "1_P1") (pintype "passive"))
    )
    (net (code "138") (name "Net-(D8-C2R)") (class "Default")
      (node (ref "D8") (pin "P20") (pinfunction "C2R_P20") (pintype "bidirectional"))
      (node (ref "R228") (pin "P1") (pinfunction "1_P1") (pintype "passive"))
    )
    (net (code "139") (name "Net-(D8-C3G)") (class "Default")
      (node (ref "D8") (pin "P18") (pinfunction "C3G_P18") (pintype "bidirectional"))
      (node (ref "R229") (pin "P1") (pinfunction "1_P1") (pintype "passive"))
    )
    (net (code "140") (name "Net-(D8-C3R)") (class "Default")
      (node (ref "D8") (pin "P17") (pinfunction "C3R_P17") (pintype "bidirectional"))
      (node (ref "R230") (pin "P1") (pinfunction "1_P1") (pintype "passive"))
    )
    (net (code "141") (name "Net-(D8-C4G)") (class "Default")
      (node (ref "D8") (pin "P15") (pinfunction "C4G_P15") (pintype "bidirectional"))
      (node (ref "R231") (pin "P1") (pinfunction "1_P1") (pintype "passive"))
    )
    (net (code "142") (name "Net-(D8-C4R)") (class "Default")
      (node (ref "D8") (pin "P14") (pinfunction "C4R_P14") (pintype "bidirectional"))
      (node (ref "R232") (pin "P1") (pinfunction "1_P1") (pintype "passive"))
    )
    (net (code "143") (name "Net-(D8-C5G)") (class "Default")
      (node (ref "D8") (pin "P1") (pinfunction "C5G_P1") (pintype "bidirectional"))
      (node (ref "R233") (pin "P1") (pinfunction "1_P1") (pintype "passive"))
    )
    (net (code "144") (name "Net-(D8-C5R)") (class "Default")
      (node (ref "D8") (pin "P2") (pinfunction "C5R_P2") (pintype "bidirectional"))
      (node (ref "R234") (pin "P1") (pinfunction "1_P1") (pintype "passive"))
    )
    (net (code "145") (name "Net-(D8-C6G)") (class "Default")
      (node (ref "D8") (pin "P4") (pinfunction "C6G_P4") (pintype "bidirectional"))
      (node (ref "R235") (pin "P1") (pinfunction "1_P1") (pintype "passive"))
    )
    (net (code "146") (name "Net-(D8-C6R)") (class "Default")
      (node (ref "D8") (pin "P5") (pinfunction "C6R_P5") (pintype "bidirectional"))
      (node (ref "R236") (pin "P1") (pinfunction "1_P1") (pintype "passive"))
    )
    (net (code "147") (name "Net-(D8-C7G)") (class "Default")
      (node (ref "D8") (pin "P7") (pinfunction "C7G_P7") (pintype "bidirectional"))
      (node (ref "R237") (pin "P1") (pinfunction "1_P1") (pintype "passive"))
    )
    (net (code "148") (name "Net-(D8-C7R)") (class "Default")
      (node (ref "D8") (pin "P8") (pinfunction "C7R_P8") (pintype "bidirectional"))
      (node (ref "R238") (pin "P1") (pinfunction "1_P1") (pintype "passive"))
    )
    (net (code "149") (name "Net-(D8-C8G)") (class "Default")
      (node (ref "D8") (pin "P10") (pinfunction "C8G_P10") (pintype "bidirectional"))
      (node (ref "R239") (pin "P1") (pinfunction "1_P1") (pintype "passive"))
    )
    (net (code "150") (name "Net-(D8-C8R)") (class "Default")
      (node (ref "D8") (pin "P11") (pinfunction "C8R_P11") (pintype "bidirectional"))
      (node (ref "R240") (pin "P1") (pinfunction "1_P1") (pintype "passive"))
    )
    (net (code "151") (name "Net-(D9-C1G)") (class "Default")
      (node (ref "D9") (pin "P24") (pinfunction "C1G_P24") (pintype "bidirectional"))
      (node (ref "R257") (pin "P1") (pinfunction "1_P1") (pintype "passive"))
    )
    (net (code "152") (name "Net-(D9-C1R)") (class "Default")
      (node (ref "D9") (pin "P23") (pinfunction "C1R_P23") (pintype "bidirectional"))
      (node (ref "R258") (pin "P1") (pinfunction "1_P1") (pintype "passive"))
    )
    (net (code "153") (name "Net-(D9-C2G)") (class "Default")
      (node (ref "D9") (pin "P21") (pinfunction "C2G_P21") (pintype "bidirectional"))
      (node (ref "R259") (pin "P1") (pinfunction "1_P1") (pintype "passive"))
    )
    (net (code "154") (name "Net-(D9-C2R)") (class "Default")
      (node (ref "D9") (pin "P20") (pinfunction "C2R_P20") (pintype "bidirectional"))
      (node (ref "R260") (pin "P1") (pinfunction "1_P1") (pintype "passive"))
    )
    (net (code "155") (name "Net-(D9-C3G)") (class "Default")
      (node (ref "D9") (pin "P18") (pinfunction "C3G_P18") (pintype "bidirectional"))
      (node (ref "R261") (pin "P1") (pinfunction "1_P1") (pintype "passive"))
    )
    (net (code "156") (name "Net-(D9-C3R)") (class "Default")
      (node (ref "D9") (pin "P17") (pinfunction "C3R_P17") (pintype "bidirectional"))
      (node (ref "R262") (pin "P1") (pinfunction "1_P1") (pintype "passive"))
    )
    (net (code "157") (name "Net-(D9-C4G)") (class "Default")
      (node (ref "D9") (pin "P15") (pinfunction "C4G_P15") (pintype "bidirectional"))
      (node (ref "R263") (pin "P1") (pinfunction "1_P1") (pintype "passive"))
    )
    (net (code "158") (name "Net-(D9-C4R)") (class "Default")
      (node (ref "D9") (pin "P14") (pinfunction "C4R_P14") (pintype "bidirectional"))
      (node (ref "R264") (pin "P1") (pinfunction "1_P1") (pintype "passive"))
    )
    (net (code "159") (name "Net-(D9-C5G)") (class "Default")
      (node (ref "D9") (pin "P1") (pinfunction "C5G_P1") (pintype "bidirectional"))
      (node (ref "R265") (pin "P1") (pinfunction "1_P1") (pintype "passive"))
    )
    (net (code "160") (name "Net-(D9-C5R)") (class "Default")
      (node (ref "D9") (pin "P2") (pinfunction "C5R_P2") (pintype "bidirectional"))
      (node (ref "R266") (pin "P1") (pinfunction "1_P1") (pintype "passive"))
    )
    (net (code "161") (name "Net-(D9-C6G)") (class "Default")
      (node (ref "D9") (pin "P4") (pinfunction "C6G_P4") (pintype "bidirectional"))
      (node (ref "R267") (pin "P1") (pinfunction "1_P1") (pintype "passive"))
    )
    (net (code "162") (name "Net-(D9-C6R)") (class "Default")
      (node (ref "D9") (pin "P5") (pinfunction "C6R_P5") (pintype "bidirectional"))
      (node (ref "R268") (pin "P1") (pinfunction "1_P1") (pintype "passive"))
    )
    (net (code "163") (name "Net-(D9-C7G)") (class "Default")
      (node (ref "D9") (pin "P7") (pinfunction "C7G_P7") (pintype "bidirectional"))
      (node (ref "R269") (pin "P1") (pinfunction "1_P1") (pintype "passive"))
    )
    (net (code "164") (name "Net-(D9-C7R)") (class "Default")
      (node (ref "D9") (pin "P8") (pinfunction "C7R_P8") (pintype "bidirectional"))
      (node (ref "R270") (pin "P1") (pinfunction "1_P1") (pintype "passive"))
    )
    (net (code "165") (name "Net-(D9-C8G)") (class "Default")
      (node (ref "D9") (pin "P10") (pinfunction "C8G_P10") (pintype "bidirectional"))
      (node (ref "R271") (pin "P1") (pinfunction "1_P1") (pintype "passive"))
    )
    (net (code "166") (name "Net-(D9-C8R)") (class "Default")
      (node (ref "D9") (pin "P11") (pinfunction "C8R_P11") (pintype "bidirectional"))
      (node (ref "R272") (pin "P1") (pinfunction "1_P1") (pintype "passive"))
    )
    (net (code "167") (name "Net-(Q1-G)") (class "Default")
      (node (ref "Q1") (pin "1") (pinfunction "G_1") (pintype "bidirectional"))
      (node (ref "R121") (pin "P2") (pinfunction "2_P2") (pintype "passive"))
    )
    (net (code "168") (name "Net-(Q2-G)") (class "Default")
      (node (ref "Q2") (pin "1") (pinfunction "G_1") (pintype "bidirectional"))
      (node (ref "R123") (pin "P2") (pinfunction "2_P2") (pintype "passive"))
    )
    (net (code "169") (name "Net-(Q3-G)") (class "Default")
      (node (ref "Q3") (pin "1") (pinfunction "G_1") (pintype "bidirectional"))
      (node (ref "R124") (pin "P2") (pinfunction "2_P2") (pintype "passive"))
    )
    (net (code "170") (name "Net-(Q4-G)") (class "Default")
      (node (ref "Q4") (pin "1") (pinfunction "G_1") (pintype "bidirectional"))
      (node (ref "R125") (pin "P2") (pinfunction "2_P2") (pintype "passive"))
    )
    (net (code "171") (name "Net-(Q5-G)") (class "Default")
      (node (ref "Q5") (pin "1") (pinfunction "G_1") (pintype "bidirectional"))
      (node (ref "R126") (pin "P2") (pinfunction "2_P2") (pintype "passive"))
    )
    (net (code "172") (name "Net-(Q6-G)") (class "Default")
      (node (ref "Q6") (pin "1") (pinfunction "G_1") (pintype "bidirectional"))
      (node (ref "R127") (pin "P2") (pinfunction "2_P2") (pintype "passive"))
    )
    (net (code "173") (name "Net-(Q7-G)") (class "Default")
      (node (ref "Q7") (pin "1") (pinfunction "G_1") (pintype "bidirectional"))
      (node (ref "R122") (pin "P2") (pinfunction "2_P2") (pintype "passive"))
    )
    (net (code "174") (name "Net-(Q8-G)") (class "Default")
      (node (ref "Q8") (pin "1") (pinfunction "G_1") (pintype "bidirectional"))
      (node (ref "R128") (pin "P2") (pinfunction "2_P2") (pintype "passive"))
    )
    (net (code "175") (name "Net-(R1-2)") (class "Default")
      (node (ref "R1") (pin "P2") (pinfunction "2_P2") (pintype "passive"))
      (node (ref "R2") (pin "P2") (pinfunction "2_P2") (pintype "passive"))
      (node (ref "U1") (pin "7") (pinfunction "QH_7") (pintype "tri_state"))
    )
    (net (code "176") (name "Net-(R3-2)") (class "Default")
      (node (ref "R3") (pin "P2") (pinfunction "2_P2") (pintype "passive"))
      (node (ref "R4") (pin "P2") (pinfunction "2_P2") (pintype "passive"))
      (node (ref "U1") (pin "6") (pinfunction "QG_6") (pintype "tri_state"))
    )
    (net (code "177") (name "Net-(R5-2)") (class "Default")
      (node (ref "R5") (pin "P2") (pinfunction "2_P2") (pintype "passive"))
      (node (ref "R6") (pin "P2") (pinfunction "2_P2") (pintype "passive"))
      (node (ref "U1") (pin "5") (pinfunction "QF_5") (pintype "tri_state"))
    )
    (net (code "178") (name "Net-(R7-2)") (class "Default")
      (node (ref "R7") (pin "P2") (pinfunction "2_P2") (pintype "passive"))
      (node (ref "R8") (pin "P2") (pinfunction "2_P2") (pintype "passive"))
      (node (ref "U1") (pin "4") (pinfunction "QE_4") (pintype "tri_state"))
    )
    (net (code "179") (name "Net-(R10-2)") (class "Default")
      (node (ref "R10") (pin "P2") (pinfunction "2_P2") (pintype "passive"))
      (node (ref "R9") (pin "P2") (pinfunction "2_P2") (pintype "passive"))
      (node (ref "U1") (pin "3") (pinfunction "QD_3") (pintype "tri_state"))
    )
    (net (code "180") (name "Net-(R11-2)") (class "Default")
      (node (ref "R11") (pin "P2") (pinfunction "2_P2") (pintype "passive"))
      (node (ref "R12") (pin "P2") (pinfunction "2_P2") (pintype "passive"))
      (node (ref "U1") (pin "2") (pinfunction "QC_2") (pintype "tri_state"))
    )
    (net (code "181") (name "Net-(R13-2)") (class "Default")
      (node (ref "R13") (pin "P2") (pinfunction "2_P2") (pintype "passive"))
      (node (ref "R14") (pin "P2") (pinfunction "2_P2") (pintype "passive"))
      (node (ref "U1") (pin "1") (pinfunction "QB_1") (pintype "tri_state"))
    )
    (net (code "182") (name "Net-(R15-2)") (class "Default")
      (node (ref "R15") (pin "P2") (pinfunction "2_P2") (pintype "passive"))
      (node (ref "R16") (pin "P2") (pinfunction "2_P2") (pintype "passive"))
      (node (ref "U1") (pin "15") (pinfunction "QA_15") (pintype "tri_state"))
    )
    (net (code "183") (name "Net-(R17-2)") (class "Default")
      (node (ref "R17") (pin "P2") (pinfunction "2_P2") (pintype "passive"))
      (node (ref "R18") (pin "P2") (pinfunction "2_P2") (pintype "passive"))
      (node (ref "U2") (pin "7") (pinfunction "QH_7") (pintype "tri_state"))
    )
    (net (code "184") (name "Net-(R19-2)") (class "Default")
      (node (ref "R19") (pin "P2") (pinfunction "2_P2") (pintype "passive"))
      (node (ref "R20") (pin "P2") (pinfunction "2_P2") (pintype "passive"))
      (node (ref "U2") (pin "6") (pinfunction "QG_6") (pintype "tri_state"))
    )
    (net (code "185") (name "Net-(R21-2)") (class "Default")
      (node (ref "R21") (pin "P2") (pinfunction "2_P2") (pintype "passive"))
      (node (ref "R22") (pin "P2") (pinfunction "2_P2") (pintype "passive"))
      (node (ref "U2") (pin "5") (pinfunction "QF_5") (pintype "tri_state"))
    )
    (net (code "186") (name "Net-(R23-2)") (class "Default")
      (node (ref "R23") (pin "P2") (pinfunction "2_P2") (pintype "passive"))
      (node (ref "R24") (pin "P2") (pinfunction "2_P2") (pintype "passive"))
      (node (ref "U2") (pin "4") (pinfunction "QE_4") (pintype "tri_state"))
    )
    (net (code "187") (name "Net-(R25-2)") (class "Default")
      (node (ref "R25") (pin "P2") (pinfunction "2_P2") (pintype "passive"))
      (node (ref "R26") (pin "P2") (pinfunction "2_P2") (pintype "passive"))
      (node (ref "U2") (pin "3") (pinfunction "QD_3") (pintype "tri_state"))
    )
    (net (code "188") (name "Net-(R27-2)") (class "Default")
      (node (ref "R27") (pin "P2") (pinfunction "2_P2") (pintype "passive"))
      (node (ref "R28") (pin "P2") (pinfunction "2_P2") (pintype "passive"))
      (node (ref "U2") (pin "2") (pinfunction "QC_2") (pintype "tri_state"))
    )
    (net (code "189") (name "Net-(R29-2)") (class "Default")
      (node (ref "R29") (pin "P2") (pinfunction "2_P2") (pintype "passive"))
      (node (ref "R30") (pin "P2") (pinfunction "2_P2") (pintype "passive"))
      (node (ref "U2") (pin "1") (pinfunction "QB_1") (pintype "tri_state"))
    )
    (net (code "190") (name "Net-(R31-2)") (class "Default")
      (node (ref "R31") (pin "P2") (pinfunction "2_P2") (pintype "passive"))
      (node (ref "R32") (pin "P2") (pinfunction "2_P2") (pintype "passive"))
      (node (ref "U2") (pin "15") (pinfunction "QA_15") (pintype "tri_state"))
    )
    (net (code "191") (name "Net-(R65-2)") (class "Default")
      (node (ref "R65") (pin "P2") (pinfunction "2_P2") (pintype "passive"))
      (node (ref "R66") (pin "P2") (pinfunction "2_P2") (pintype "passive"))
      (node (ref "U3") (pin "7") (pinfunction "QH_7") (pintype "tri_state"))
    )
    (net (code "192") (name "Net-(R67-2)") (class "Default")
      (node (ref "R67") (pin "P2") (pinfunction "2_P2") (pintype "passive"))
      (node (ref "R68") (pin "P2") (pinfunction "2_P2") (pintype "passive"))
      (node (ref "U3") (pin "6") (pinfunction "QG_6") (pintype "tri_state"))
    )
    (net (code "193") (name "Net-(R69-2)") (class "Default")
      (node (ref "R69") (pin "P2") (pinfunction "2_P2") (pintype "passive"))
      (node (ref "R70") (pin "P2") (pinfunction "2_P2") (pintype "passive"))
      (node (ref "U3") (pin "5") (pinfunction "QF_5") (pintype "tri_state"))
    )
    (net (code "194") (name "Net-(R71-2)") (class "Default")
      (node (ref "R71") (pin "P2") (pinfunction "2_P2") (pintype "passive"))
      (node (ref "R72") (pin "P2") (pinfunction "2_P2") (pintype "passive"))
      (node (ref "U3") (pin "4") (pinfunction "QE_4") (pintype "tri_state"))
    )
    (net (code "195") (name "Net-(R73-2)") (class "Default")
      (node (ref "R73") (pin "P2") (pinfunction "2_P2") (pintype "passive"))
      (node (ref "R74") (pin "P2") (pinfunction "2_P2") (pintype "passive"))
      (node (ref "U3") (pin "3") (pinfunction "QD_3") (pintype "tri_state"))
    )
    (net (code "196") (name "Net-(R75-2)") (class "Default")
      (node (ref "R75") (pin "P2") (pinfunction "2_P2") (pintype "passive"))
      (node (ref "R76") (pin "P2") (pinfunction "2_P2") (pintype "passive"))
      (node (ref "U3") (pin "2") (pinfunction "QC_2") (pintype "tri_state"))
    )
    (net (code "197") (name "Net-(R77-2)") (class "Default")
      (node (ref "R77") (pin "P2") (pinfunction "2_P2") (pintype "passive"))
      (node (ref "R78") (pin "P2") (pinfunction "2_P2") (pintype "passive"))
      (node (ref "U3") (pin "1") (pinfunction "QB_1") (pintype "tri_state"))
    )
    (net (code "198") (name "Net-(R79-2)") (class "Default")
      (node (ref "R79") (pin "P2") (pinfunction "2_P2") (pintype "passive"))
      (node (ref "R80") (pin "P2") (pinfunction "2_P2") (pintype "passive"))
      (node (ref "U3") (pin "15") (pinfunction "QA_15") (pintype "tri_state"))
    )
    (net (code "199") (name "Net-(R97-2)") (class "Default")
      (node (ref "R97") (pin "P2") (pinfunction "2_P2") (pintype "passive"))
      (node (ref "R98") (pin "P2") (pinfunction "2_P2") (pintype "passive"))
      (node (ref "U4") (pin "7") (pinfunction "QH_7") (pintype "tri_state"))
    )
    (net (code "200") (name "Net-(R100-2)") (class "Default")
      (node (ref "R100") (pin "P2") (pinfunction "2_P2") (pintype "passive"))
      (node (ref "R99") (pin "P2") (pinfunction "2_P2") (pintype "passive"))
      (node (ref "U4") (pin "6") (pinfunction "QG_6") (pintype "tri_state"))
    )
    (net (code "201") (name "Net-(R101-2)") (class "Default")
      (node (ref "R101") (pin "P2") (pinfunction "2_P2") (pintype "passive"))
      (node (ref "R102") (pin "P2") (pinfunction "2_P2") (pintype "passive"))
      (node (ref "U4") (pin "5") (pinfunction "QF_5") (pintype "tri_state"))
    )
    (net (code "202") (name "Net-(R103-2)") (class "Default")
      (node (ref "R103") (pin "P2") (pinfunction "2_P2") (pintype "passive"))
      (node (ref "R104") (pin "P2") (pinfunction "2_P2") (pintype "passive"))
      (node (ref "U4") (pin "4") (pinfunction "QE_4") (pintype "tri_state"))
    )
    (net (code "203") (name "Net-(R105-2)") (class "Default")
      (node (ref "R105") (pin "P2") (pinfunction "2_P2") (pintype "passive"))
      (node (ref "R106") (pin "P2") (pinfunction "2_P2") (pintype "passive"))
      (node (ref "U4") (pin "3") (pinfunction "QD_3") (pintype "tri_state"))
    )
    (net (code "204") (name "Net-(R107-2)") (class "Default")
      (node (ref "R107") (pin "P2") (pinfunction "2_P2") (pintype "passive"))
      (node (ref "R108") (pin "P2") (pinfunction "2_P2") (pintype "passive"))
      (node (ref "U4") (pin "2") (pinfunction "QC_2") (pintype "tri_state"))
    )
    (net (code "205") (name "Net-(R109-2)") (class "Default")
      (node (ref "R109") (pin "P2") (pinfunction "2_P2") (pintype "passive"))
      (node (ref "R110") (pin "P2") (pinfunction "2_P2") (pintype "passive"))
      (node (ref "U4") (pin "1") (pinfunction "QB_1") (pintype "tri_state"))
    )
    (net (code "206") (name "Net-(R111-2)") (class "Default")
      (node (ref "R111") (pin "P2") (pinfunction "2_P2") (pintype "passive"))
      (node (ref "R112") (pin "P2") (pinfunction "2_P2") (pintype "passive"))
      (node (ref "U4") (pin "15") (pinfunction "QA_15") (pintype "tri_state"))
    )
    (net (code "207") (name "Net-(R121-1)") (class "Default")
      (node (ref "R121") (pin "P1") (pinfunction "1_P1") (pintype "passive"))
      (node (ref "U11") (pin "8") (pinfunction "O_8") (pintype "output"))
    )
    (net (code "208") (name "Net-(R122-1)") (class "Default")
      (node (ref "R122") (pin "P1") (pinfunction "1_P1") (pintype "passive"))
      (node (ref "U12") (pin "2") (pinfunction "O_2") (pintype "output"))
    )
    (net (code "209") (name "Net-(R123-1)") (class "Default")
      (node (ref "R123") (pin "P1") (pinfunction "1_P1") (pintype "passive"))
      (node (ref "U11") (pin "6") (pinfunction "O_6") (pintype "output"))
    )
    (net (code "210") (name "Net-(R124-1)") (class "Default")
      (node (ref "R124") (pin "P1") (pinfunction "1_P1") (pintype "passive"))
      (node (ref "U11") (pin "2") (pinfunction "O_2") (pintype "output"))
    )
    (net (code "211") (name "Net-(R125-1)") (class "Default")
      (node (ref "R125") (pin "P1") (pinfunction "1_P1") (pintype "passive"))
      (node (ref "U11") (pin "4") (pinfunction "O_4") (pintype "output"))
    )
    (net (code "212") (name "Net-(R126-1)") (class "Default")
      (node (ref "R126") (pin "P1") (pinfunction "1_P1") (pintype "passive"))
      (node (ref "U12") (pin "6") (pinfunction "O_6") (pintype "output"))
    )
    (net (code "213") (name "Net-(R127-1)") (class "Default")
      (node (ref "R127") (pin "P1") (pinfunction "1_P1") (pintype "passive"))
      (node (ref "U12") (pin "8") (pinfunction "O_8") (pintype "output"))
    )
    (net (code "214") (name "Net-(R128-1)") (class "Default")
      (node (ref "R128") (pin "P1") (pinfunction "1_P1") (pintype "passive"))
      (node (ref "U12") (pin "4") (pinfunction "O_4") (pintype "output"))
    )
    (net (code "215") (name "Net-(R129-2)") (class "Default")
      (node (ref "R129") (pin "P2") (pinfunction "2_P2") (pintype "passive"))
      (node (ref "R130") (pin "P2") (pinfunction "2_P2") (pintype "passive"))
      (node (ref "U5") (pin "7") (pinfunction "QH_7") (pintype "tri_state"))
    )
    (net (code "216") (name "Net-(R131-2)") (class "Default")
      (node (ref "R131") (pin "P2") (pinfunction "2_P2") (pintype "passive"))
      (node (ref "R132") (pin "P2") (pinfunction "2_P2") (pintype "passive"))
      (node (ref "U5") (pin "6") (pinfunction "QG_6") (pintype "tri_state"))
    )
    (net (code "217") (name "Net-(R133-2)") (class "Default")
      (node (ref "R133") (pin "P2") (pinfunction "2_P2") (pintype "passive"))
      (node (ref "R134") (pin "P2") (pinfunction "2_P2") (pintype "passive"))
      (node (ref "U5") (pin "5") (pinfunction "QF_5") (pintype "tri_state"))
    )
    (net (code "218") (name "Net-(R135-2)") (class "Default")
      (node (ref "R135") (pin "P2") (pinfunction "2_P2") (pintype "passive"))
      (node (ref "R136") (pin "P2") (pinfunction "2_P2") (pintype "passive"))
      (node (ref "U5") (pin "4") (pinfunction "QE_4") (pintype "tri_state"))
    )
    (net (code "219") (name "Net-(R137-2)") (class "Default")
      (node (ref "R137") (pin "P2") (pinfunction "2_P2") (pintype "passive"))
      (node (ref "R138") (pin "P2") (pinfunction "2_P2") (pintype "passive"))
      (node (ref "U5") (pin "3") (pinfunction "QD_3") (pintype "tri_state"))
    )
    (net (code "220") (name "Net-(R139-2)") (class "Default")
      (node (ref "R139") (pin "P2") (pinfunction "2_P2") (pintype "passive"))
      (node (ref "R140") (pin "P2") (pinfunction "2_P2") (pintype "passive"))
      (node (ref "U5") (pin "2") (pinfunction "QC_2") (pintype "tri_state"))
    )
    (net (code "221") (name "Net-(R141-2)") (class "Default")
      (node (ref "R141") (pin "P2") (pinfunction "2_P2") (pintype "passive"))
      (node (ref "R142") (pin "P2") (pinfunction "2_P2") (pintype "passive"))
      (node (ref "U5") (pin "1") (pinfunction "QB_1") (pintype "tri_state"))
    )
    (net (code "222") (name "Net-(R143-2)") (class "Default")
      (node (ref "R143") (pin "P2") (pinfunction "2_P2") (pintype "passive"))
      (node (ref "R144") (pin "P2") (pinfunction "2_P2") (pintype "passive"))
      (node (ref "U5") (pin "15") (pinfunction "QA_15") (pintype "tri_state"))
    )
    (net (code "223") (name "Net-(R161-2)") (class "Default")
      (node (ref "R161") (pin "P2") (pinfunction "2_P2") (pintype "passive"))
      (node (ref "R162") (pin "P2") (pinfunction "2_P2") (pintype "passive"))
      (node (ref "U6") (pin "7") (pinfunction "QH_7") (pintype "tri_state"))
    )
    (net (code "224") (name "Net-(R163-2)") (class "Default")
      (node (ref "R163") (pin "P2") (pinfunction "2_P2") (pintype "passive"))
      (node (ref "R164") (pin "P2") (pinfunction "2_P2") (pintype "passive"))
      (node (ref "U6") (pin "6") (pinfunction "QG_6") (pintype "tri_state"))
    )
    (net (code "225") (name "Net-(R165-2)") (class "Default")
      (node (ref "R165") (pin "P2") (pinfunction "2_P2") (pintype "passive"))
      (node (ref "R166") (pin "P2") (pinfunction "2_P2") (pintype "passive"))
      (node (ref "U6") (pin "5") (pinfunction "QF_5") (pintype "tri_state"))
    )
    (net (code "226") (name "Net-(R167-2)") (class "Default")
      (node (ref "R167") (pin "P2") (pinfunction "2_P2") (pintype "passive"))
      (node (ref "R168") (pin "P2") (pinfunction "2_P2") (pintype "passive"))
      (node (ref "U6") (pin "4") (pinfunction "QE_4") (pintype "tri_state"))
    )
    (net (code "227") (name "Net-(R169-2)") (class "Default")
      (node (ref "R169") (pin "P2") (pinfunction "2_P2") (pintype "passive"))
      (node (ref "R170") (pin "P2") (pinfunction "2_P2") (pintype "passive"))
      (node (ref "U6") (pin "3") (pinfunction "QD_3") (pintype "tri_state"))
    )
    (net (code "228") (name "Net-(R171-2)") (class "Default")
      (node (ref "R171") (pin "P2") (pinfunction "2_P2") (pintype "passive"))
      (node (ref "R172") (pin "P2") (pinfunction "2_P2") (pintype "passive"))
      (node (ref "U6") (pin "2") (pinfunction "QC_2") (pintype "tri_state"))
    )
    (net (code "229") (name "Net-(R173-2)") (class "Default")
      (node (ref "R173") (pin "P2") (pinfunction "2_P2") (pintype "passive"))
      (node (ref "R174") (pin "P2") (pinfunction "2_P2") (pintype "passive"))
      (node (ref "U6") (pin "1") (pinfunction "QB_1") (pintype "tri_state"))
    )
    (net (code "230") (name "Net-(R175-2)") (class "Default")
      (node (ref "R175") (pin "P2") (pinfunction "2_P2") (pintype "passive"))
      (node (ref "R176") (pin "P2") (pinfunction "2_P2") (pintype "passive"))
      (node (ref "U6") (pin "15") (pinfunction "QA_15") (pintype "tri_state"))
    )
    (net (code "231") (name "Net-(R193-2)") (class "Default")
      (node (ref "R193") (pin "P2") (pinfunction "2_P2") (pintype "passive"))
      (node (ref "R194") (pin "P2") (pinfunction "2_P2") (pintype "passive"))
      (node (ref "U7") (pin "7") (pinfunction "QH_7") (pintype "tri_state"))
    )
    (net (code "232") (name "Net-(R195-2)") (class "Default")
      (node (ref "R195") (pin "P2") (pinfunction "2_P2") (pintype "passive"))
      (node (ref "R196") (pin "P2") (pinfunction "2_P2") (pintype "passive"))
      (node (ref "U7") (pin "6") (pinfunction "QG_6") (pintype "tri_state"))
    )
    (net (code "233") (name "Net-(R197-2)") (class "Default")
      (node (ref "R197") (pin "P2") (pinfunction "2_P2") (pintype "passive"))
      (node (ref "R198") (pin "P2") (pinfunction "2_P2") (pintype "passive"))
      (node (ref "U7") (pin "5") (pinfunction "QF_5") (pintype "tri_state"))
    )
    (net (code "234") (name "Net-(R199-2)") (class "Default")
      (node (ref "R199") (pin "P2") (pinfunction "2_P2") (pintype "passive"))
      (node (ref "R200") (pin "P2") (pinfunction "2_P2") (pintype "passive"))
      (node (ref "U7") (pin "4") (pinfunction "QE_4") (pintype "tri_state"))
    )
    (net (code "235") (name "Net-(R201-2)") (class "Default")
      (node (ref "R201") (pin "P2") (pinfunction "2_P2") (pintype "passive"))
      (node (ref "R202") (pin "P2") (pinfunction "2_P2") (pintype "passive"))
      (node (ref "U7") (pin "3") (pinfunction "QD_3") (pintype "tri_state"))
    )
    (net (code "236") (name "Net-(R203-2)") (class "Default")
      (node (ref "R203") (pin "P2") (pinfunction "2_P2") (pintype "passive"))
      (node (ref "R204") (pin "P2") (pinfunction "2_P2") (pintype "passive"))
      (node (ref "U7") (pin "2") (pinfunction "QC_2") (pintype "tri_state"))
    )
    (net (code "237") (name "Net-(R205-2)") (class "Default")
      (node (ref "R205") (pin "P2") (pinfunction "2_P2") (pintype "passive"))
      (node (ref "R206") (pin "P2") (pinfunction "2_P2") (pintype "passive"))
      (node (ref "U7") (pin "1") (pinfunction "QB_1") (pintype "tri_state"))
    )
    (net (code "238") (name "Net-(R207-2)") (class "Default")
      (node (ref "R207") (pin "P2") (pinfunction "2_P2") (pintype "passive"))
      (node (ref "R208") (pin "P2") (pinfunction "2_P2") (pintype "passive"))
      (node (ref "U7") (pin "15") (pinfunction "QA_15") (pintype "tri_state"))
    )
    (net (code "239") (name "Net-(R225-2)") (class "Default")
      (node (ref "R225") (pin "P2") (pinfunction "2_P2") (pintype "passive"))
      (node (ref "R226") (pin "P2") (pinfunction "2_P2") (pintype "passive"))
      (node (ref "U8") (pin "7") (pinfunction "QH_7") (pintype "tri_state"))
    )
    (net (code "240") (name "Net-(R227-2)") (class "Default")
      (node (ref "R227") (pin "P2") (pinfunction "2_P2") (pintype "passive"))
      (node (ref "R228") (pin "P2") (pinfunction "2_P2") (pintype "passive"))
      (node (ref "U8") (pin "6") (pinfunction "QG_6") (pintype "tri_state"))
    )
    (net (code "241") (name "Net-(R229-2)") (class "Default")
      (node (ref "R229") (pin "P2") (pinfunction "2_P2") (pintype "passive"))
      (node (ref "R230") (pin "P2") (pinfunction "2_P2") (pintype "passive"))
      (node (ref "U8") (pin "5") (pinfunction "QF_5") (pintype "tri_state"))
    )
    (net (code "242") (name "Net-(R231-2)") (class "Default")
      (node (ref "R231") (pin "P2") (pinfunction "2_P2") (pintype "passive"))
      (node (ref "R232") (pin "P2") (pinfunction "2_P2") (pintype "passive"))
      (node (ref "U8") (pin "4") (pinfunction "QE_4") (pintype "tri_state"))
    )
    (net (code "243") (name "Net-(R233-2)") (class "Default")
      (node (ref "R233") (pin "P2") (pinfunction "2_P2") (pintype "passive"))
      (node (ref "R234") (pin "P2") (pinfunction "2_P2") (pintype "passive"))
      (node (ref "U8") (pin "3") (pinfunction "QD_3") (pintype "tri_state"))
    )
    (net (code "244") (name "Net-(R235-2)") (class "Default")
      (node (ref "R235") (pin "P2") (pinfunction "2_P2") (pintype "passive"))
      (node (ref "R236") (pin "P2") (pinfunction "2_P2") (pintype "passive"))
      (node (ref "U8") (pin "2") (pinfunction "QC_2") (pintype "tri_state"))
    )
    (net (code "245") (name "Net-(R237-2)") (class "Default")
      (node (ref "R237") (pin "P2") (pinfunction "2_P2") (pintype "passive"))
      (node (ref "R238") (pin "P2") (pinfunction "2_P2") (pintype "passive"))
      (node (ref "U8") (pin "1") (pinfunction "QB_1") (pintype "tri_state"))
    )
    (net (code "246") (name "Net-(R239-2)") (class "Default")
      (node (ref "R239") (pin "P2") (pinfunction "2_P2") (pintype "passive"))
      (node (ref "R240") (pin "P2") (pinfunction "2_P2") (pintype "passive"))
      (node (ref "U8") (pin "15") (pinfunction "QA_15") (pintype "tri_state"))
    )
    (net (code "247") (name "Net-(R257-2)") (class "Default")
      (node (ref "R257") (pin "P2") (pinfunction "2_P2") (pintype "passive"))
      (node (ref "R258") (pin "P2") (pinfunction "2_P2") (pintype "passive"))
      (node (ref "U9") (pin "7") (pinfunction "QH_7") (pintype "tri_state"))
    )
    (net (code "248") (name "Net-(R259-2)") (class "Default")
      (node (ref "R259") (pin "P2") (pinfunction "2_P2") (pintype "passive"))
      (node (ref "R260") (pin "P2") (pinfunction "2_P2") (pintype "passive"))
      (node (ref "U9") (pin "6") (pinfunction "QG_6") (pintype "tri_state"))
    )
    (net (code "249") (name "Net-(R261-2)") (class "Default")
      (node (ref "R261") (pin "P2") (pinfunction "2_P2") (pintype "passive"))
      (node (ref "R262") (pin "P2") (pinfunction "2_P2") (pintype "passive"))
      (node (ref "U9") (pin "5") (pinfunction "QF_5") (pintype "tri_state"))
    )
    (net (code "250") (name "Net-(R263-2)") (class "Default")
      (node (ref "R263") (pin "P2") (pinfunction "2_P2") (pintype "passive"))
      (node (ref "R264") (pin "P2") (pinfunction "2_P2") (pintype "passive"))
      (node (ref "U9") (pin "4") (pinfunction "QE_4") (pintype "tri_state"))
    )
    (net (code "251") (name "Net-(R265-2)") (class "Default")
      (node (ref "R265") (pin "P2") (pinfunction "2_P2") (pintype "passive"))
      (node (ref "R266") (pin "P2") (pinfunction "2_P2") (pintype "passive"))
      (node (ref "U9") (pin "3") (pinfunction "QD_3") (pintype "tri_state"))
    )
    (net (code "252") (name "Net-(R267-2)") (class "Default")
      (node (ref "R267") (pin "P2") (pinfunction "2_P2") (pintype "passive"))
      (node (ref "R268") (pin "P2") (pinfunction "2_P2") (pintype "passive"))
      (node (ref "U9") (pin "2") (pinfunction "QC_2") (pintype "tri_state"))
    )
    (net (code "253") (name "Net-(R269-2)") (class "Default")
      (node (ref "R269") (pin "P2") (pinfunction "2_P2") (pintype "passive"))
      (node (ref "R270") (pin "P2") (pinfunction "2_P2") (pintype "passive"))
      (node (ref "U9") (pin "1") (pinfunction "QB_1") (pintype "tri_state"))
    )
    (net (code "254") (name "Net-(R271-2)") (class "Default")
      (node (ref "R271") (pin "P2") (pinfunction "2_P2") (pintype "passive"))
      (node (ref "R272") (pin "P2") (pinfunction "2_P2") (pintype "passive"))
      (node (ref "U9") (pin "15") (pinfunction "QA_15") (pintype "tri_state"))
    )
    (net (code "255") (name "Net-(R289-1)") (class "Default")
      (node (ref "D10") (pin "A") (pinfunction "A_A") (pintype "passive"))
      (node (ref "R289") (pin "P1") (pinfunction "1_P1") (pintype "passive"))
      (node (ref "U10") (pin "P22") (pinfunction "ADC7_P22") (pintype "bidirectional"))
    )
    (net (code "256") (name "Net-(U1-QH*)") (class "Default")
      (node (ref "U1") (pin "9") (pinfunction "QH*_9") (pintype "tri_state"))
      (node (ref "U2") (pin "14") (pinfunction "SER_14") (pintype "input"))
    )
    (net (code "257") (name "Net-(U2-QH*)") (class "Default")
      (node (ref "U2") (pin "9") (pinfunction "QH*_9") (pintype "tri_state"))
      (node (ref "U3") (pin "14") (pinfunction "SER_14") (pintype "input"))
    )
    (net (code "258") (name "Net-(U4-QH*)") (class "Default")
      (node (ref "U4") (pin "9") (pinfunction "QH*_9") (pintype "tri_state"))
      (node (ref "U5") (pin "14") (pinfunction "SER_14") (pintype "input"))
    )
    (net (code "259") (name "Net-(U5-QH*)") (class "Default")
      (node (ref "U5") (pin "9") (pinfunction "QH*_9") (pintype "tri_state"))
      (node (ref "U6") (pin "14") (pinfunction "SER_14") (pintype "input"))
    )
    (net (code "260") (name "Net-(U7-QH*)") (class "Default")
      (node (ref "U7") (pin "9") (pinfunction "QH*_9") (pintype "tri_state"))
      (node (ref "U8") (pin "14") (pinfunction "SER_14") (pintype "input"))
    )
    (net (code "261") (name "Net-(U8-QH*)") (class "Default")
      (node (ref "U8") (pin "9") (pinfunction "QH*_9") (pintype "tri_state"))
      (node (ref "U9") (pin "14") (pinfunction "SER_14") (pintype "input"))
    )
    (net (code "262") (name "Net-(U10-(PCINT0{slash}CLKO{slash}ICP1)PB0)") (class "Default")
      (node (ref "U10") (pin "P12") (pinfunction "(PCINT0/CLKO/ICP1)PB0_P12") (pintype "bidirectional"))
      (node (ref "U13") (pin "3") (pinfunction "C_3") (pintype "input"))
    )
    (net (code "263") (name "Net-(U10-(PCINT1{slash}OC1A)PB1)") (class "Default")
      (node (ref "U10") (pin "P13") (pinfunction "(PCINT1/OC1A)PB1_P13") (pintype "bidirectional"))
      (node (ref "U13") (pin "2") (pinfunction "B_2") (pintype "input"))
    )
    (net (code "264") (name "Net-(U10-(PCINT2{slash}SS{slash}OC1B)PB2)") (class "Default")
      (node (ref "U10") (pin "P14") (pinfunction "(PCINT2/SS/OC1B)PB2_P14") (pintype "bidirectional"))
      (node (ref "U13") (pin "1") (pinfunction "A_1") (pintype "input"))
    )
    (net (code "265") (name "Net-(U10-PC0(ADC0{slash}PCINT8))") (class "Default")
      (node (ref "SW1") (pin "P2") (pinfunction "P2_P2") (pintype "bidirectional"))
      (node (ref "U10") (pin "P23") (pinfunction "PC0(ADC0/PCINT8)_P23") (pintype "bidirectional"))
    )
    (net (code "266") (name "Net-(U10-PC1(ADC1{slash}PCINT9))") (class "Default")
      (node (ref "SW2") (pin "P2") (pinfunction "P2_P2") (pintype "bidirectional"))
      (node (ref "U10") (pin "P24") (pinfunction "PC1(ADC1/PCINT9)_P24") (pintype "bidirectional"))
    )
    (net (code "267") (name "Net-(U10-PD0(RXD{slash}PCINT16))") (class "Default")
      (node (ref "RX") (pin "P$1") (pinfunction "P$1_P$1") (pintype "bidirectional"))
      (node (ref "U10") (pin "P30") (pinfunction "PD0(RXD/PCINT16)_P30") (pintype "bidirectional"))
    )
    (net (code "268") (name "Net-(U10-PD1(TXD{slash}PCINT17))") (class "Default")
      (node (ref "TX") (pin "P$1") (pinfunction "P$1_P$1") (pintype "bidirectional"))
      (node (ref "U10") (pin "P31") (pinfunction "PD1(TXD/PCINT17)_P31") (pintype "bidirectional"))
    )
    (net (code "269") (name "Net-(U11C-I)") (class "Default")
      (node (ref "U11") (pin "9") (pinfunction "I_9") (pintype "input"))
      (node (ref "U13") (pin "15") (pinfunction "Y0_15") (pintype "output"))
    )
    (net (code "270") (name "Net-(U11D-I)") (class "Default")
      (node (ref "U11") (pin "1") (pinfunction "I_1") (pintype "input"))
      (node (ref "U13") (pin "13") (pinfunction "Y2_13") (pintype "output"))
    )
    (net (code "271") (name "Net-(U11E-I)") (class "Default")
      (node (ref "U11") (pin "3") (pinfunction "I_3") (pintype "input"))
      (node (ref "U13") (pin "12") (pinfunction "Y3_12") (pintype "output"))
    )
    (net (code "272") (name "Net-(U11F-I)") (class "Default")
      (node (ref "U11") (pin "5") (pinfunction "I_5") (pintype "input"))
      (node (ref "U13") (pin "14") (pinfunction "Y1_14") (pintype "output"))
    )
    (net (code "273") (name "Net-(U12C-I)") (class "Default")
      (node (ref "U12") (pin "9") (pinfunction "I_9") (pintype "input"))
      (node (ref "U13") (pin "10") (pinfunction "Y5_10") (pintype "output"))
    )
    (net (code "274") (name "Net-(U12D-I)") (class "Default")
      (node (ref "U12") (pin "1") (pinfunction "I_1") (pintype "input"))
      (node (ref "U13") (pin "9") (pinfunction "Y6_9") (pintype "output"))
    )
    (net (code "275") (name "Net-(U12E-I)") (class "Default")
      (node (ref "U12") (pin "3") (pinfunction "I_3") (pintype "input"))
      (node (ref "U13") (pin "7") (pinfunction "Y7_7") (pintype "output"))
    )
    (net (code "276") (name "Net-(U12F-I)") (class "Default")
      (node (ref "U12") (pin "5") (pinfunction "I_5") (pintype "input"))
      (node (ref "U13") (pin "11") (pinfunction "Y4_11") (pintype "output"))
    )
    (net (code "277") (name "unconnected-(SW1-PadP1)") (class "Default")
      (node (ref "SW1") (pin "P1") (pinfunction "P1_P1") (pintype "bidirectional"))
    )
    (net (code "278") (name "unconnected-(SW2-PadP1)") (class "Default")
      (node (ref "SW2") (pin "P1") (pinfunction "P1_P1") (pintype "bidirectional"))
    )
    (net (code "279") (name "unconnected-(U3-QH*-Pad9)") (class "Default")
      (node (ref "U3") (pin "9") (pinfunction "QH*_9") (pintype "tri_state"))
    )
    (net (code "280") (name "unconnected-(U6-QH*-Pad9)") (class "Default")
      (node (ref "U6") (pin "9") (pinfunction "QH*_9") (pintype "tri_state"))
    )
    (net (code "281") (name "unconnected-(U9-QH*-Pad9)") (class "Default")
      (node (ref "U9") (pin "9") (pinfunction "QH*_9") (pintype "tri_state"))
    )
    (net (code "282") (name "unconnected-(U10-ADC6-PadP19)") (class "Default")
      (node (ref "U10") (pin "P19") (pinfunction "ADC6_P19") (pintype "bidirectional"))
    )
    (net (code "283") (name "unconnected-(U10-PC2(ADC2{slash}PCINT10)-PadP25)") (class "Default")
      (node (ref "U10") (pin "P25") (pinfunction "PC2(ADC2/PCINT10)_P25") (pintype "bidirectional"))
    )
    (net (code "284") (name "unconnected-(U10-PC3(ADC3{slash}PCINT11)-PadP26)") (class "Default")
      (node (ref "U10") (pin "P26") (pinfunction "PC3(ADC3/PCINT11)_P26") (pintype "bidirectional"))
    )
    (net (code "285") (name "unconnected-(U10-PC4(ADC4{slash}SDA{slash}PCINT12)-PadP27)") (class "Default")
      (node (ref "U10") (pin "P27") (pinfunction "PC4(ADC4/SDA/PCINT12)_P27") (pintype "bidirectional"))
    )
    (net (code "286") (name "unconnected-(U10-PC5(ADC5{slash}SCL{slash}PCINT13)-PadP28)") (class "Default")
      (node (ref "U10") (pin "P28") (pinfunction "PC5(ADC5/SCL/PCINT13)_P28") (pintype "bidirectional"))
    )
    (net (code "287") (name "unconnected-(U11A-O-Pad12)") (class "Default")
      (node (ref "U11") (pin "12") (pinfunction "O_12") (pintype "output"))
    )
    (net (code "288") (name "unconnected-(U11B-O-Pad10)") (class "Default")
      (node (ref "U11") (pin "10") (pinfunction "O_10") (pintype "output"))
    )
    (net (code "289") (name "unconnected-(U12A-O-Pad12)") (class "Default")
      (node (ref "U12") (pin "12") (pinfunction "O_12") (pintype "output"))
    )
    (net (code "290") (name "unconnected-(U12B-O-Pad10)") (class "Default")
      (node (ref "U12") (pin "10") (pinfunction "O_10") (pintype "output"))
    )
  )
)
